# AtariST_microATX.net
KiCad netlist of a schematic drawn in EAGLE
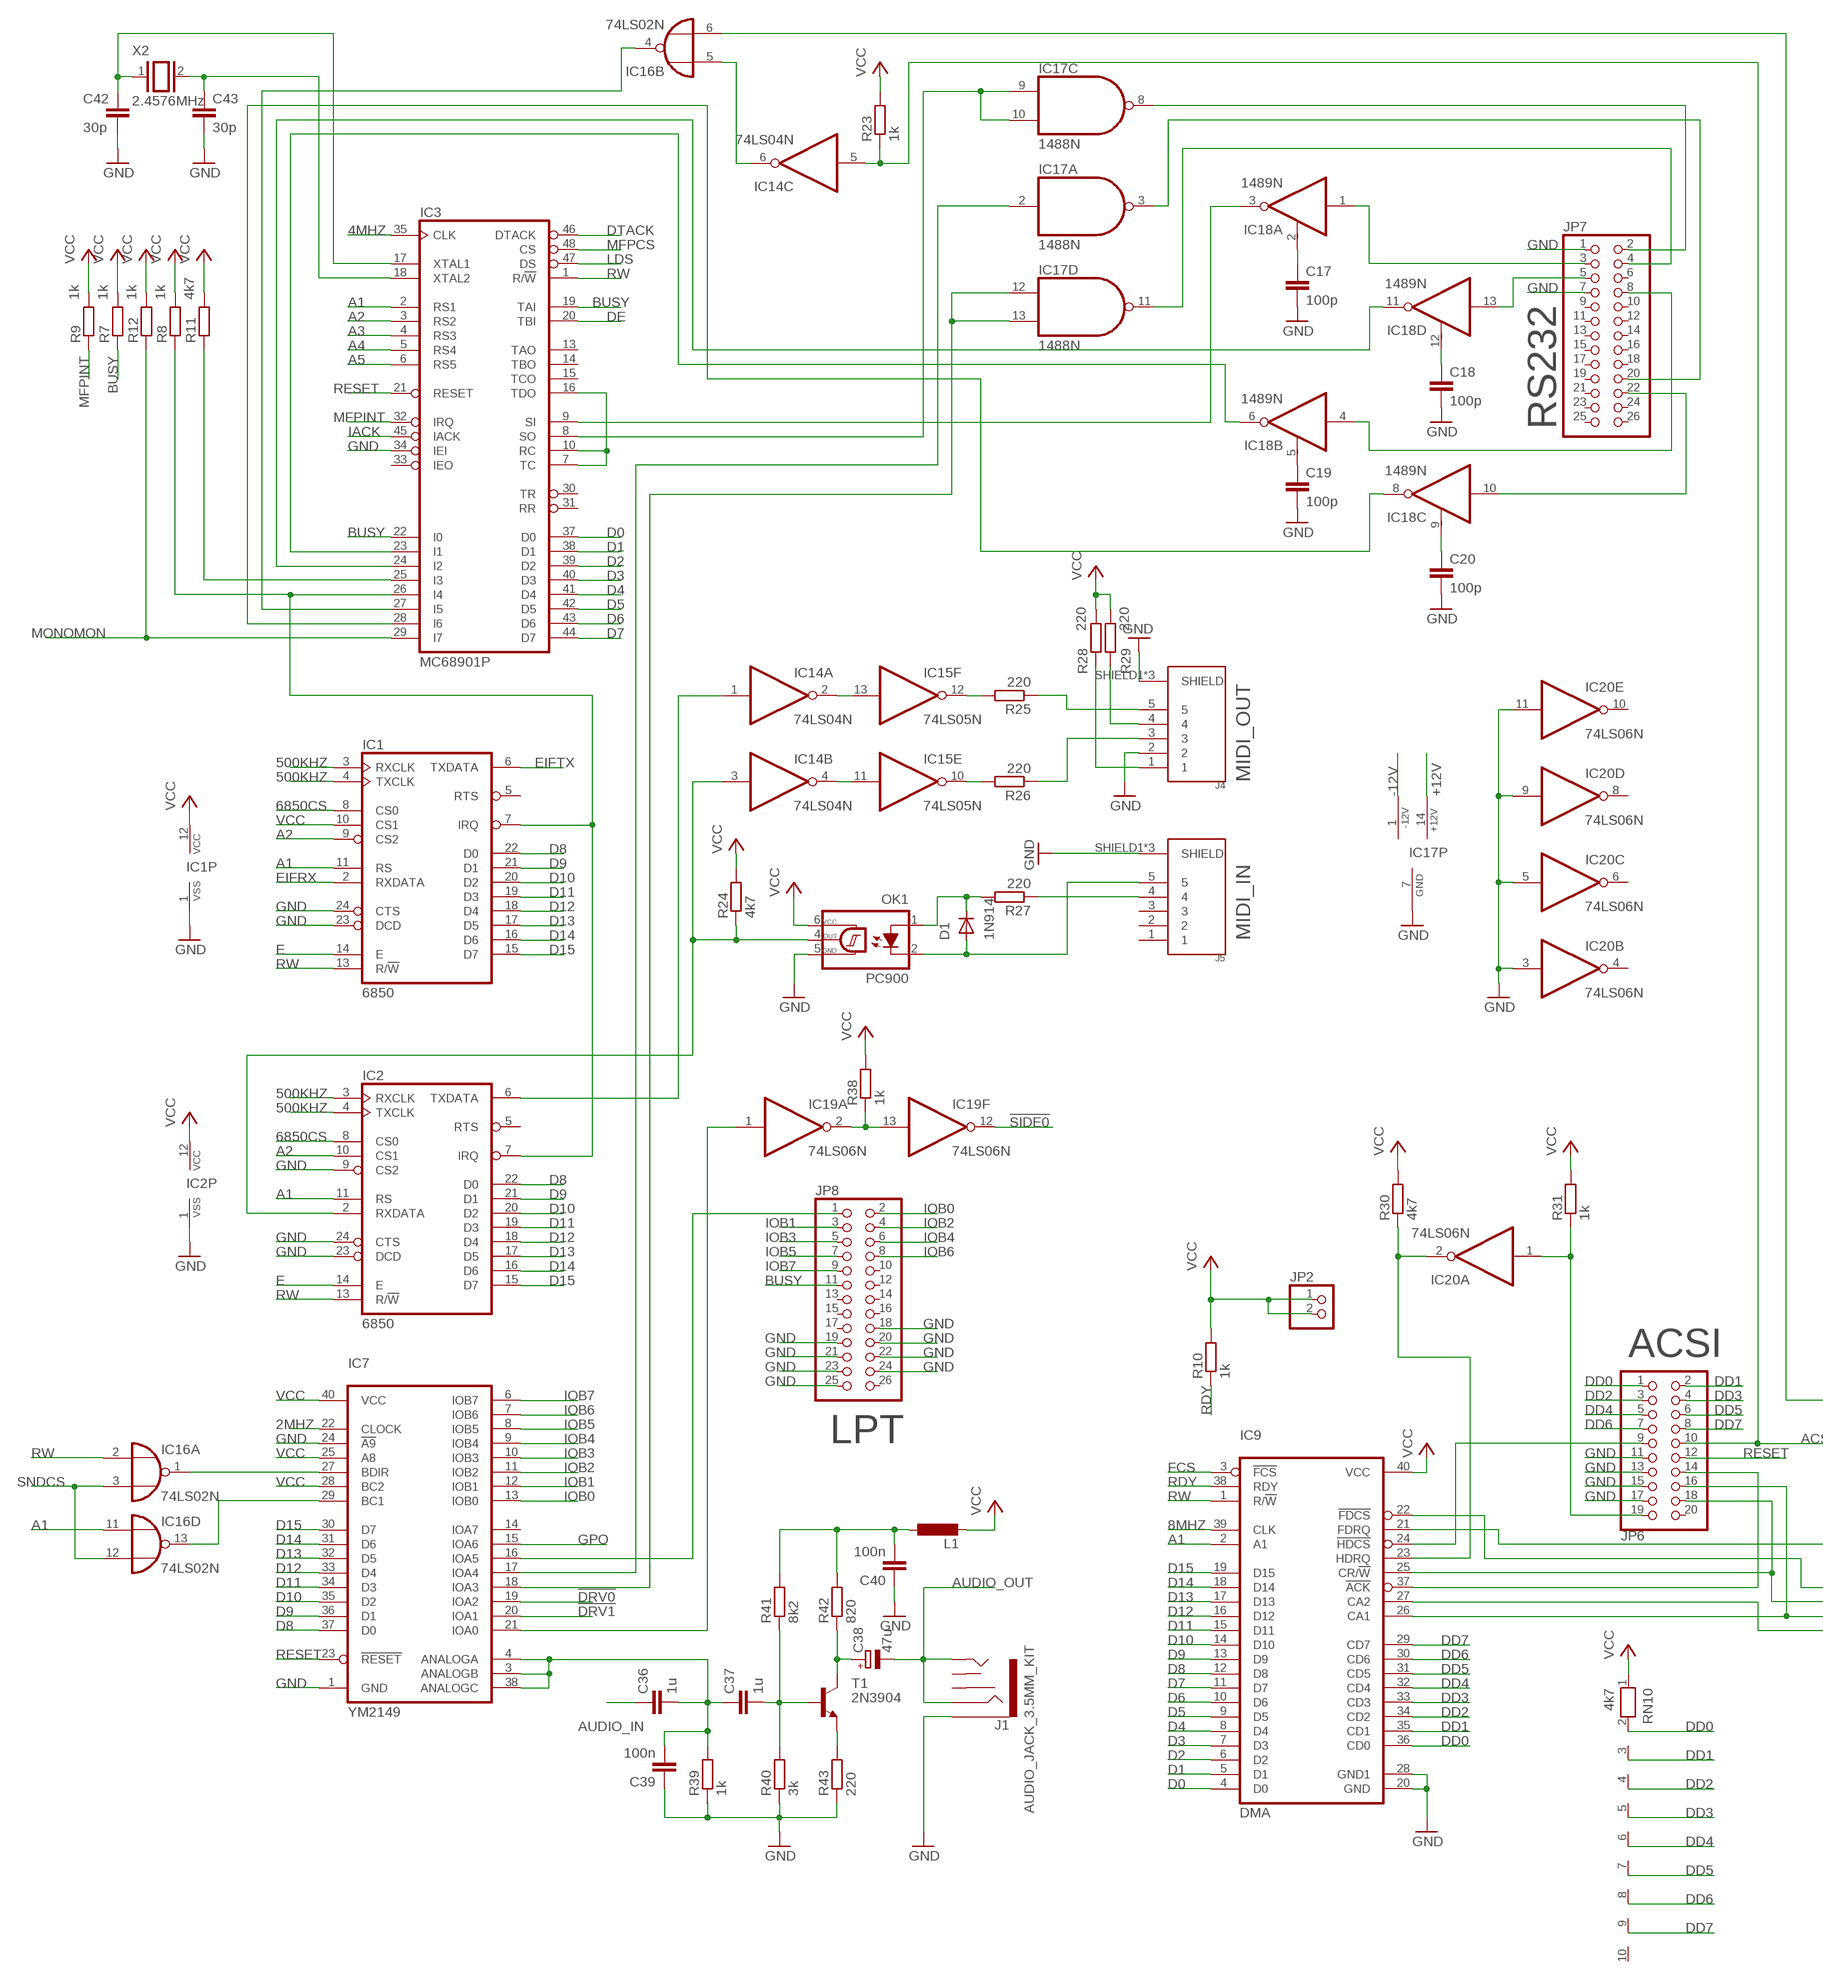
[diagram p0: schematic, sheet 1, part 1 of 2]
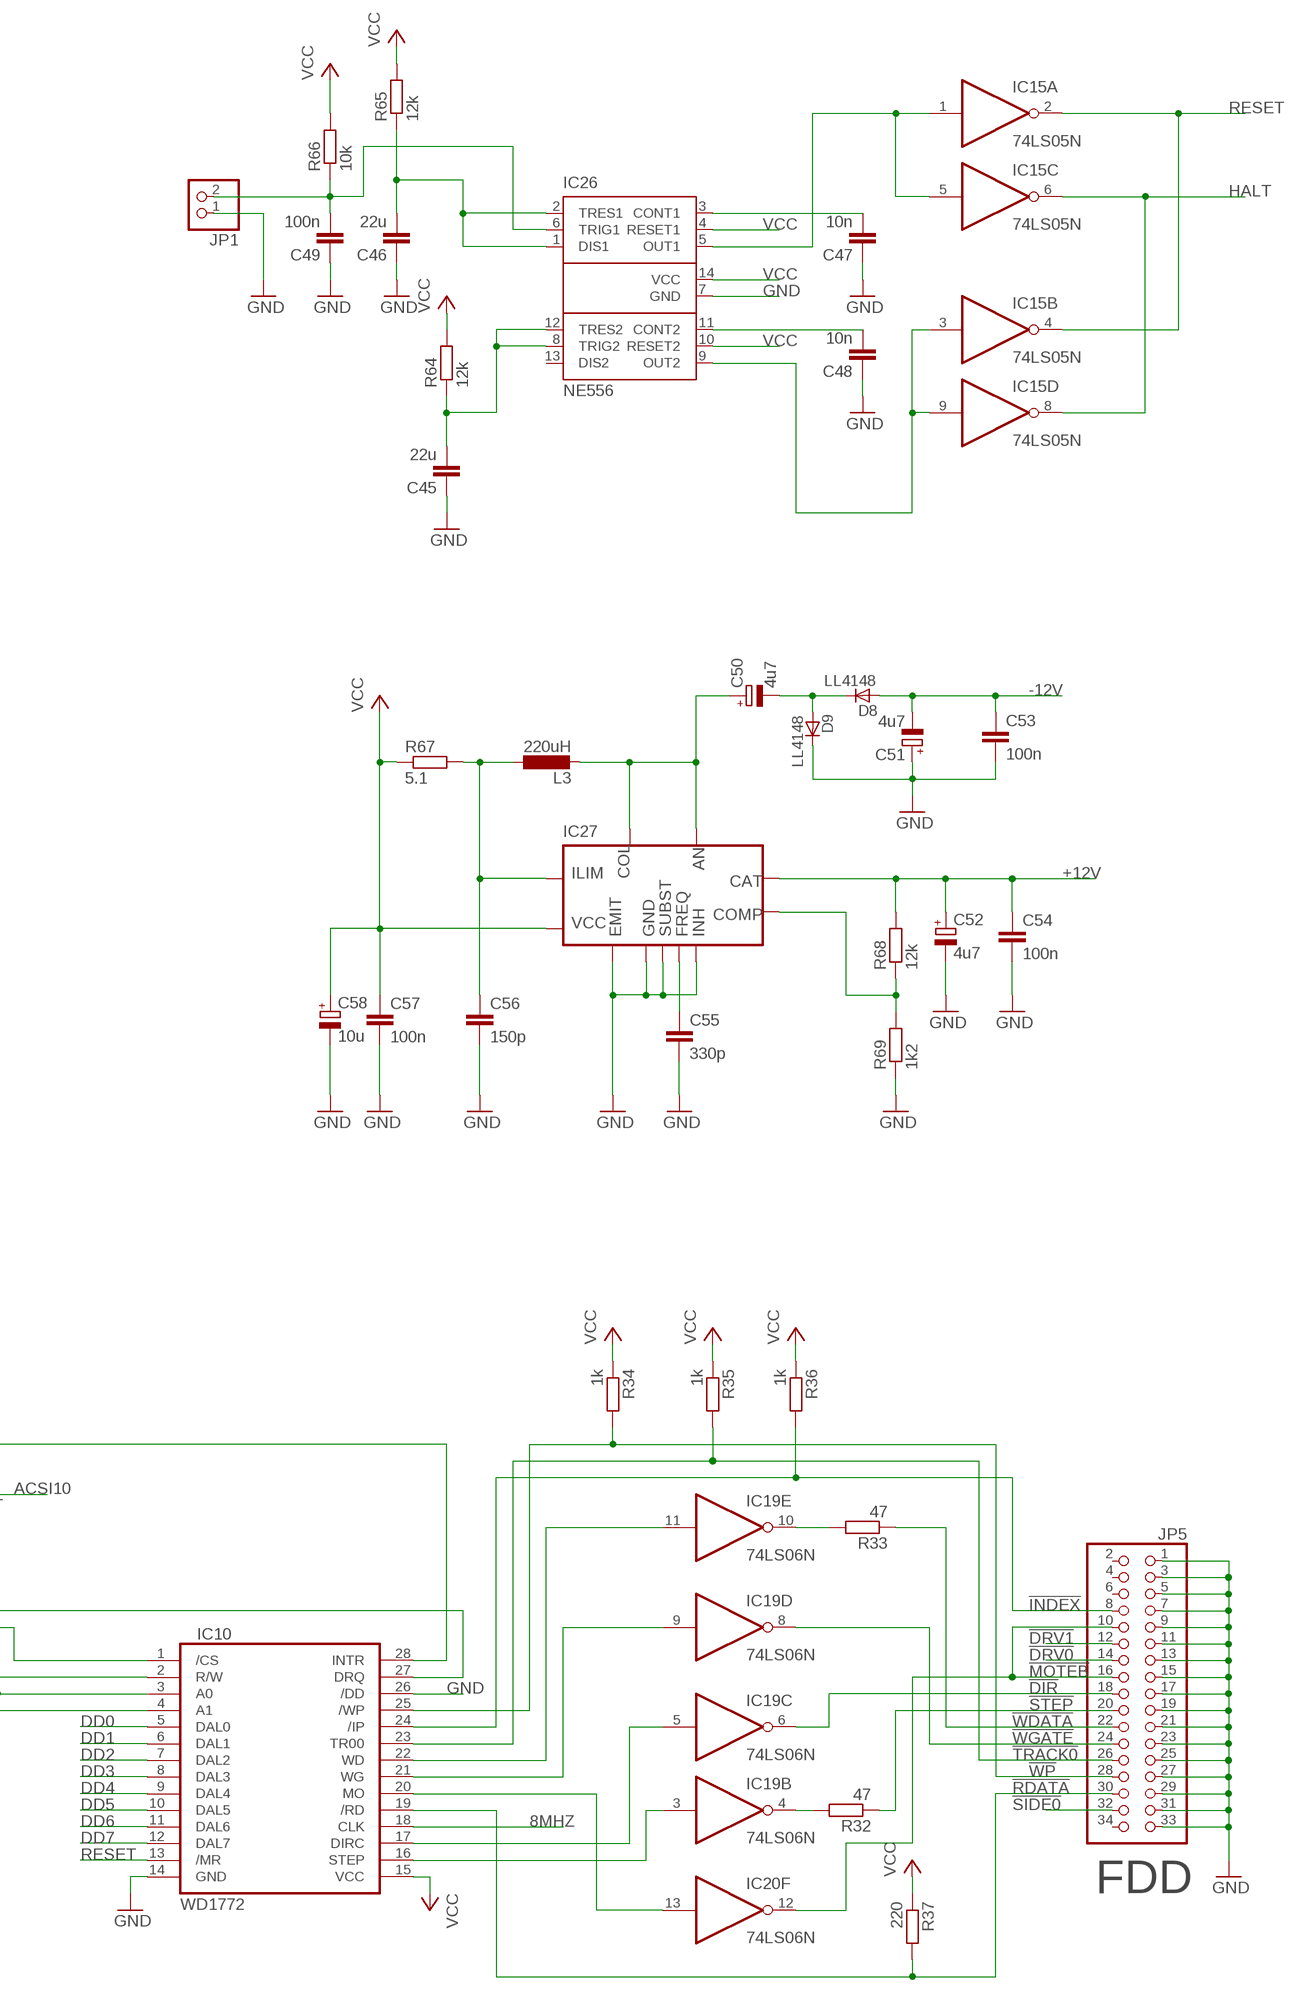
[diagram p1: schematic, sheet 1, part 2 of 2]
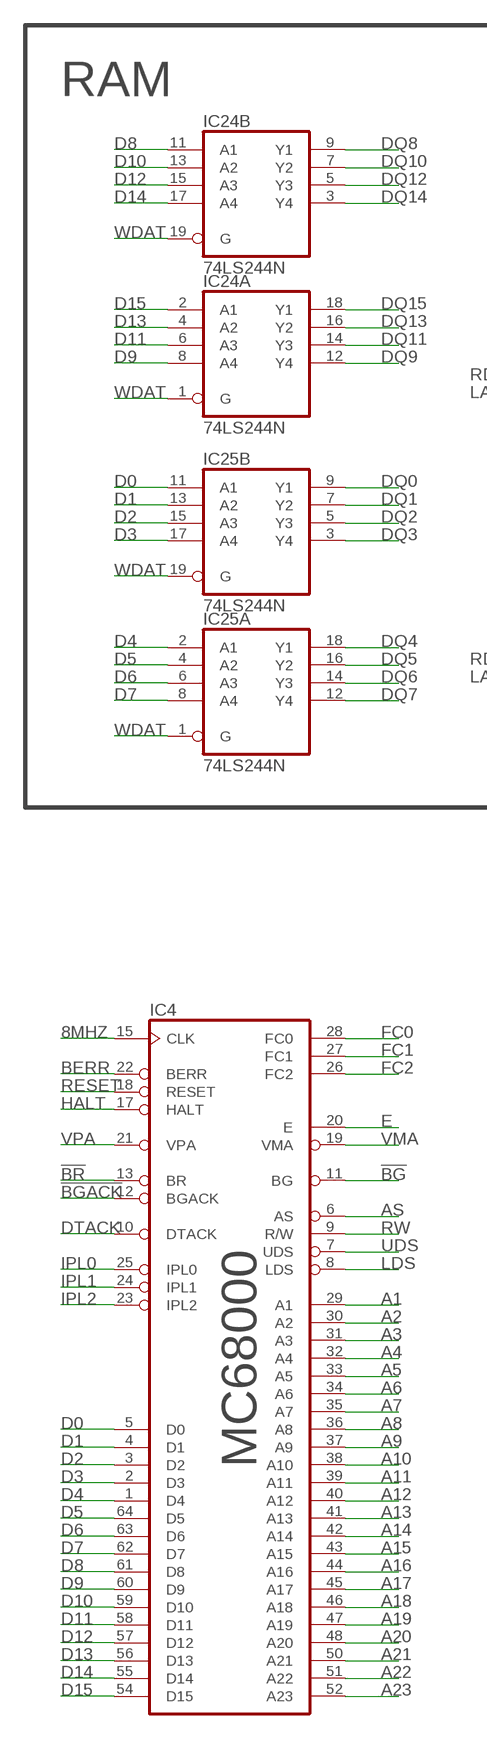
[diagram p2: schematic, sheet 2, part 1 of 2]
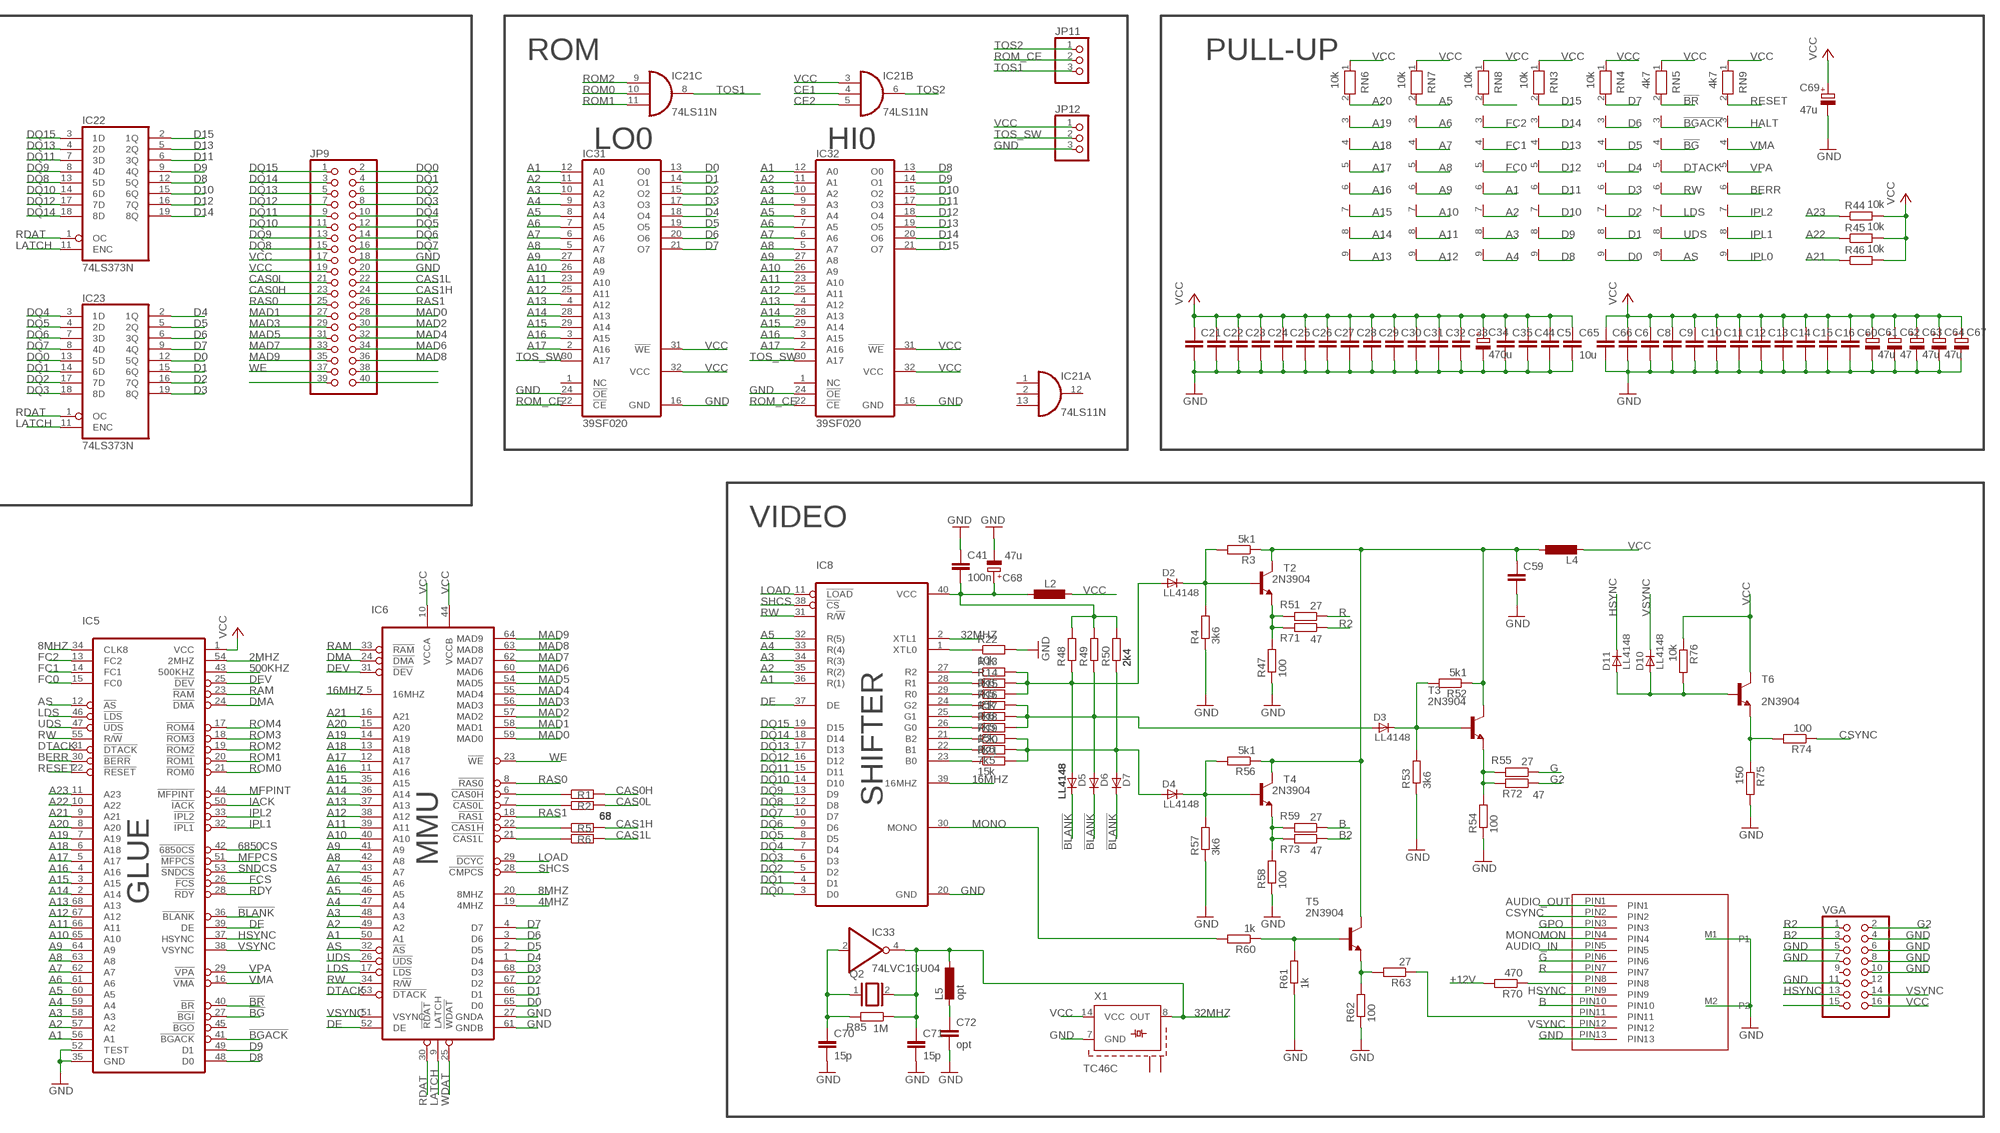
[diagram p3: schematic, sheet 2, part 2 of 2]
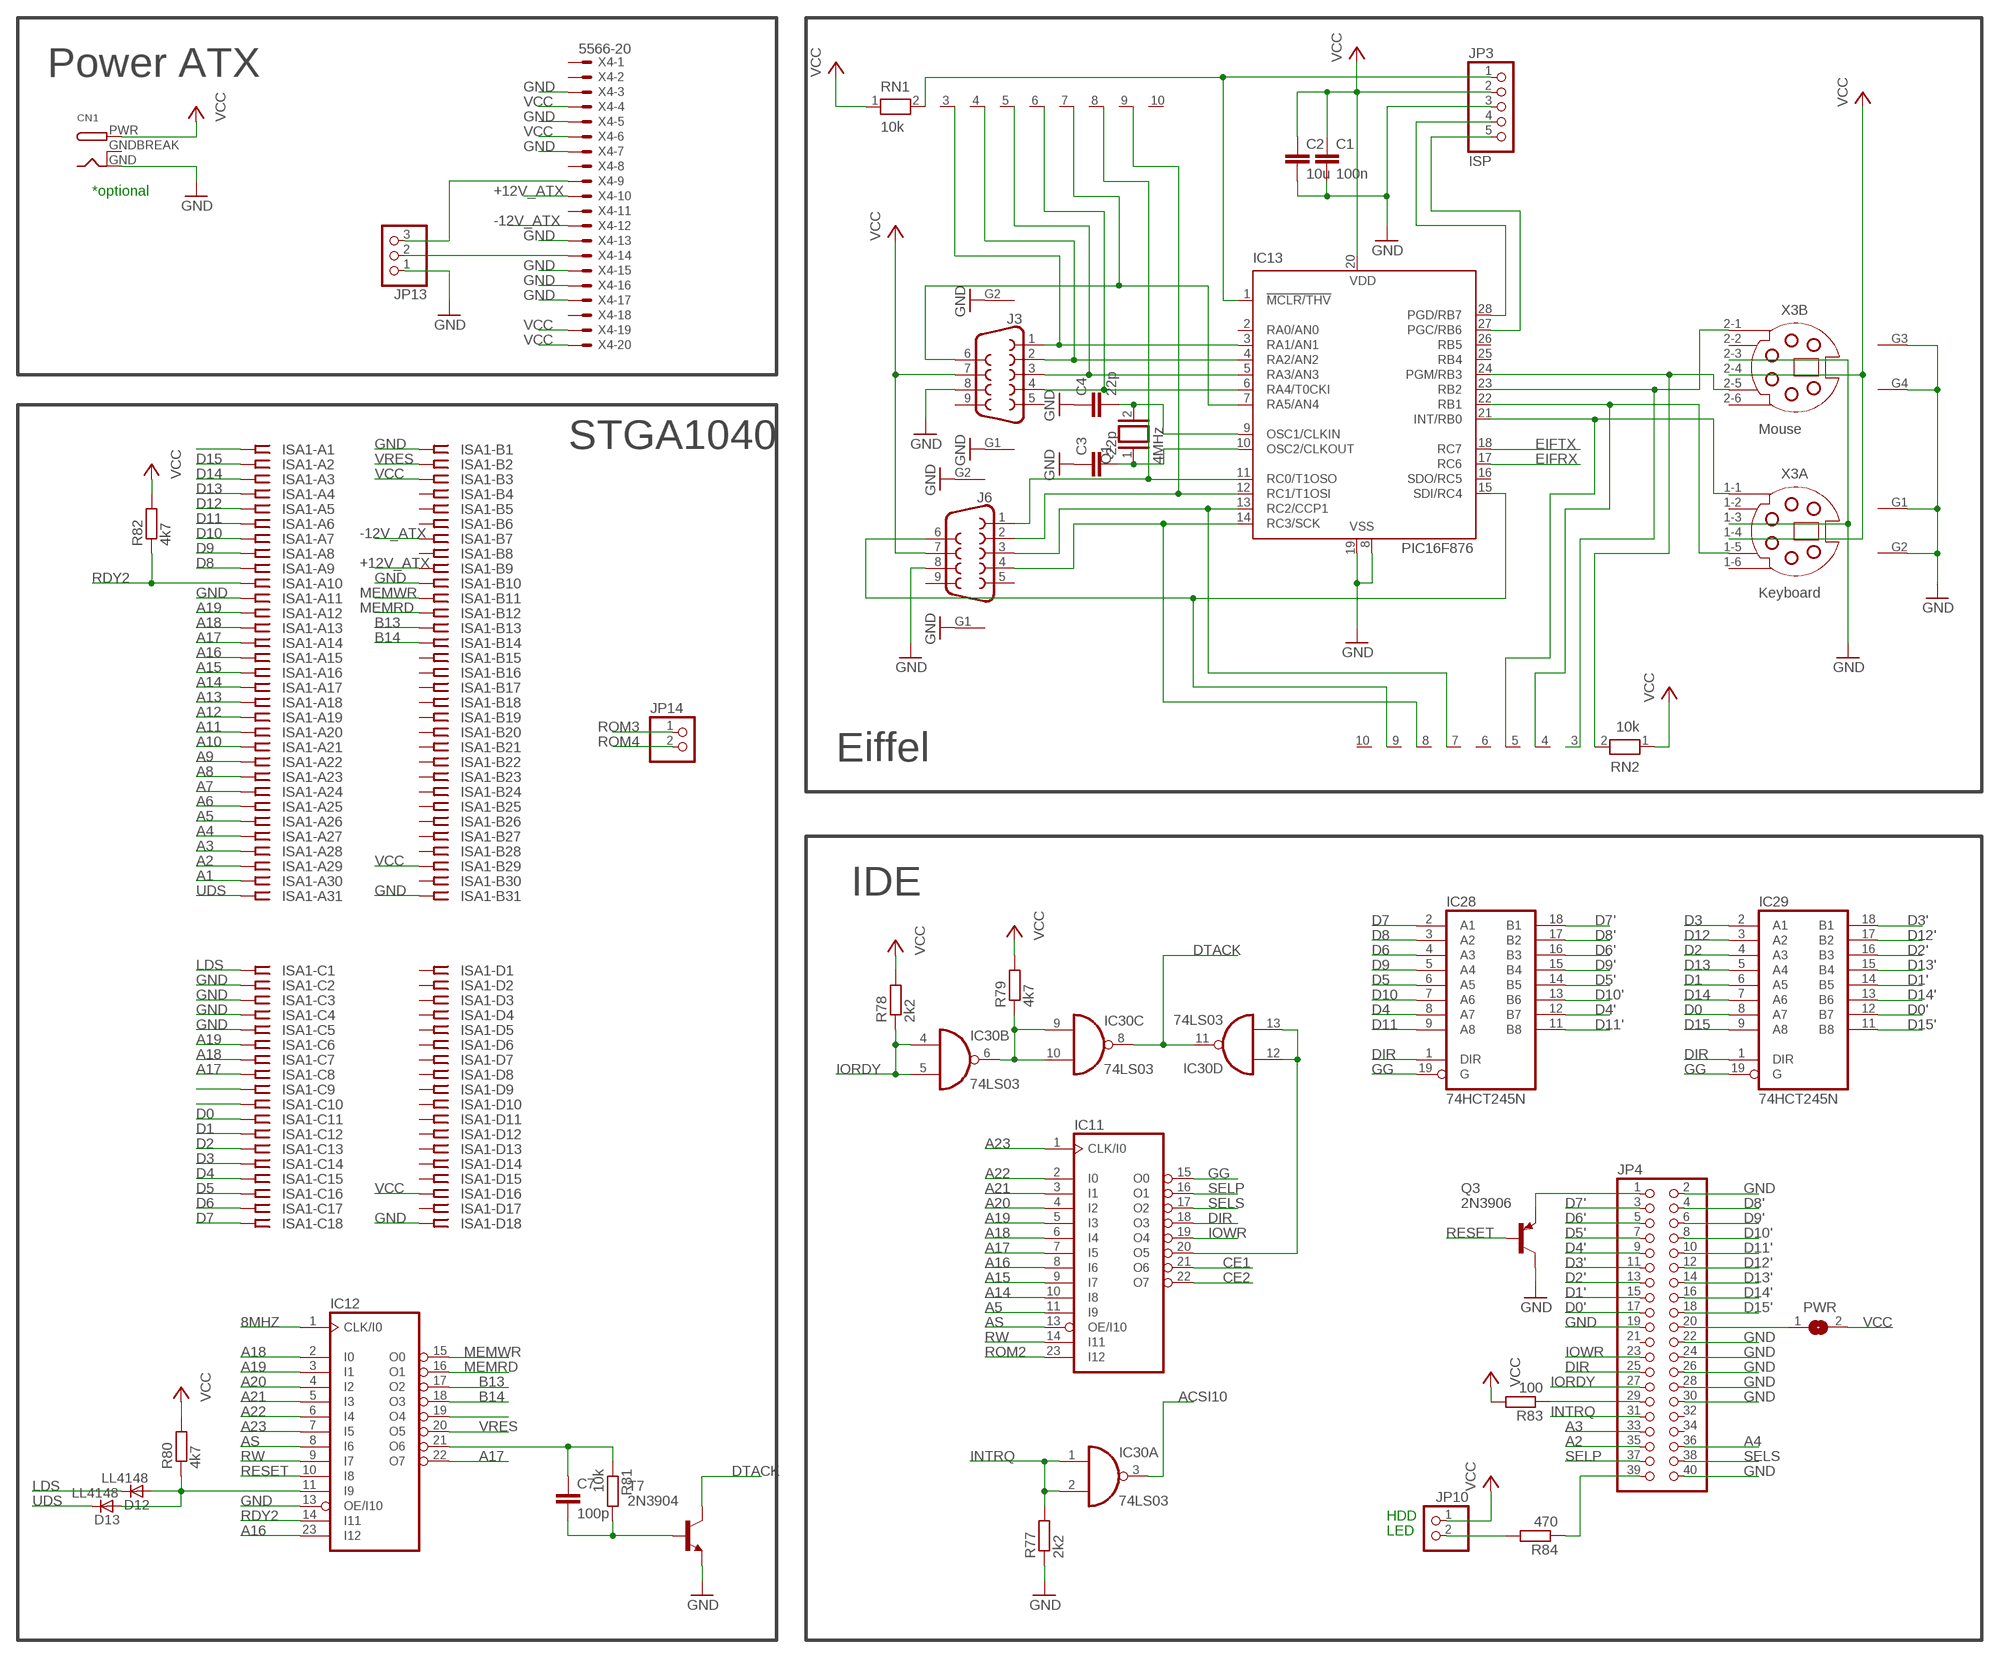
[diagram p4: schematic, sheet 3]

(export (version "E")
  (design (tool "Eeschema 10.0.6"))
  (components
    (comp (ref "C1")
      (value "100n")
      (footprint "eagle-import:C0805")
      (libsource (lib "eagle-import") (part "C-EUC0805"))
    )
    (comp (ref "C2")
      (value "10u")
      (footprint "eagle-import:C1206")
      (libsource (lib "eagle-import") (part "C-EUC1206"))
    )
    (comp (ref "C3")
      (value "22p")
      (footprint "eagle-import:C0805")
      (libsource (lib "eagle-import") (part "C-EUC0805"))
    )
    (comp (ref "C4")
      (value "22p")
      (footprint "eagle-import:C0805")
      (libsource (lib "eagle-import") (part "C-EUC0805"))
    )
    (comp (ref "C7")
      (value "100p")
      (footprint "eagle-import:C0805")
      (libsource (lib "eagle-import") (part "C-EUC0805"))
    )
    (comp (ref "CN1")
      (value "DCBARRELPTH")
      (footprint "eagle-import:DCJACK_2MM_PTH")
      (libsource (lib "eagle-import") (part "DCBARRELPTH"))
    )
    (comp (ref "D12")
      (value "LL4148")
      (footprint "eagle-import:SOD80_DO213AA_MINIMELF")
      (libsource (lib "eagle-import") (part "LL4148"))
    )
    (comp (ref "D13")
      (value "LL4148")
      (footprint "eagle-import:SOD80_DO213AA_MINIMELF")
      (libsource (lib "eagle-import") (part "LL4148"))
    )
    (comp (ref "IC11")
      (value "20V8")
      (footprint "eagle-import:DIL24-3")
      (fields (field (name "MF") "FARNELL") (field (name "MPN") "GAL20V8B-25QP"))
      (libsource (lib "eagle-import") (part "20V8"))
    )
    (comp (ref "IC12")
      (value "20V8")
      (footprint "eagle-import:DIL24-3")
      (fields (field (name "MF") "FARNELL") (field (name "MPN") "GAL20V8B-25QP"))
      (libsource (lib "eagle-import") (part "20V8"))
    )
    (comp (ref "IC13")
      (value "PIC16F876")
      (footprint "eagle-import:DIL28-3")
      (fields (field (name "MF") "MICROCHIP") (field (name "MPN") "PIC16F872-I/SP"))
      (libsource (lib "eagle-import") (part "PIC16872PF"))
    )
    (comp (ref "IC28")
      (value "74HCT245N")
      (footprint "eagle-import:DIL20")
      (libsource (lib "eagle-import") (part "74245NHCT"))
    )
    (comp (ref "IC29")
      (value "74HCT245N")
      (footprint "eagle-import:DIL20")
      (libsource (lib "eagle-import") (part "74245NHCT"))
    )
    (comp (ref "IC30")
      (value "74LS03")
      (footprint "eagle-import:SO14")
      (libsource (lib "eagle-import") (part "7403DALS"))
    )
    (comp (ref "ISA1")
      (value "ISA-SLOT")
      (footprint "eagle-import:ISA-16")
      (libsource (lib "eagle-import") (part "ISA-SLOT"))
    )
    (comp (ref "J3")
      (value "DB9MALE")
      (footprint "eagle-import:DB9_MALE")
      (libsource (lib "eagle-import") (part "DB9MALE"))
    )
    (comp (ref "J6")
      (value "DB9MALE")
      (footprint "eagle-import:DB9_MALE")
      (libsource (lib "eagle-import") (part "DB9MALE"))
    )
    (comp (ref "JP3")
      (value "ISP")
      (footprint "eagle-import:1X05")
      (libsource (lib "eagle-import") (part "PINHD-1X5"))
    )
    (comp (ref "JP4")
      (value "PINHD-2X20")
      (footprint "eagle-import:2X20")
      (libsource (lib "eagle-import") (part "PINHD-2X20"))
    )
    (comp (ref "JP10")
      (value "PINHD-1X2")
      (footprint "eagle-import:1X02")
      (libsource (lib "eagle-import") (part "PINHD-1X2"))
    )
    (comp (ref "JP13")
      (value "PINHD-1X3")
      (footprint "eagle-import:1X03")
      (libsource (lib "eagle-import") (part "PINHD-1X3"))
    )
    (comp (ref "JP14")
      (value "PINHD-1X2")
      (footprint "eagle-import:1X02")
      (libsource (lib "eagle-import") (part "PINHD-1X2"))
    )
    (comp (ref "PWR") (value "SJ") (footprint "eagle-import:SJ") (libsource (lib "eagle-import") (part "SJ")))
    (comp (ref "Q1")
      (value "4MHz")
      (footprint "eagle-import:QS")
      (libsource (lib "eagle-import") (part "XTAL/S"))
    )
    (comp (ref "Q3")
      (value "2N3906")
      (footprint "eagle-import:TO92")
      (libsource (lib "eagle-import") (part "2N3906"))
    )
    (comp (ref "R77")
      (value "2k2")
      (footprint "eagle-import:R0805")
      (libsource (lib "eagle-import") (part "R-EU_R0805"))
    )
    (comp (ref "R78")
      (value "2k2")
      (footprint "eagle-import:R0805")
      (libsource (lib "eagle-import") (part "R-EU_R0805"))
    )
    (comp (ref "R79")
      (value "4k7")
      (footprint "eagle-import:R0805")
      (libsource (lib "eagle-import") (part "R-EU_R0805"))
    )
    (comp (ref "R80")
      (value "4k7")
      (footprint "eagle-import:R0805")
      (libsource (lib "eagle-import") (part "R-EU_R0805"))
    )
    (comp (ref "R81")
      (value "10k")
      (footprint "eagle-import:R0805")
      (libsource (lib "eagle-import") (part "R-EU_R0805"))
    )
    (comp (ref "R82")
      (value "4k7")
      (footprint "eagle-import:R0805")
      (libsource (lib "eagle-import") (part "R-EU_R0805"))
    )
    (comp (ref "R83")
      (value "100")
      (footprint "eagle-import:R0805")
      (libsource (lib "eagle-import") (part "R-EU_R0805"))
    )
    (comp (ref "R84")
      (value "470")
      (footprint "eagle-import:R0805")
      (libsource (lib "eagle-import") (part "R-EU_R0805"))
    )
    (comp (ref "RN1")
      (value "10k")
      (footprint "eagle-import:RN-10")
      (libsource (lib "eagle-import") (part "RN09"))
    )
    (comp (ref "RN2")
      (value "10k")
      (footprint "eagle-import:RN-10")
      (libsource (lib "eagle-import") (part "RN09"))
    )
    (comp (ref "T7")
      (value "2N3904")
      (footprint "eagle-import:TO92")
      (libsource (lib "eagle-import") (part "2N3904"))
    )
    (comp (ref "X3")
      (value "MDSSV-BD06")
      (footprint "eagle-import:SSV-BD06")
      (libsource (lib "eagle-import") (part "MDSSV-BD06"))
    )
    (comp (ref "X4")
      (value "5566-20")
      (footprint "eagle-import:5566-20")
      (libsource (lib "eagle-import") (part "5566-20"))
    )
    (comp (ref "C5")
      (value "C-EU050-025X075")
      (footprint "eagle-import:C050-025X075")
      (libsource (lib "eagle-import") (part "C-EU050-025X075"))
    )
    (comp (ref "C6")
      (value "C-EUC0805")
      (footprint "eagle-import:C0805")
      (libsource (lib "eagle-import") (part "C-EUC0805"))
    )
    (comp (ref "C8")
      (value "C-EUC0805")
      (footprint "eagle-import:C0805")
      (libsource (lib "eagle-import") (part "C-EUC0805"))
    )
    (comp (ref "C9")
      (value "C-EUC0805")
      (footprint "eagle-import:C0805")
      (libsource (lib "eagle-import") (part "C-EUC0805"))
    )
    (comp (ref "C10")
      (value "C-EUC0805")
      (footprint "eagle-import:C0805")
      (libsource (lib "eagle-import") (part "C-EUC0805"))
    )
    (comp (ref "C11")
      (value "C-EUC0805")
      (footprint "eagle-import:C0805")
      (libsource (lib "eagle-import") (part "C-EUC0805"))
    )
    (comp (ref "C12")
      (value "C-EUC0805")
      (footprint "eagle-import:C0805")
      (libsource (lib "eagle-import") (part "C-EUC0805"))
    )
    (comp (ref "C13")
      (value "C-EUC0805")
      (footprint "eagle-import:C0805")
      (libsource (lib "eagle-import") (part "C-EUC0805"))
    )
    (comp (ref "C14")
      (value "C-EUC0805")
      (footprint "eagle-import:C0805")
      (libsource (lib "eagle-import") (part "C-EUC0805"))
    )
    (comp (ref "C15")
      (value "C-EUC0805")
      (footprint "eagle-import:C0805")
      (libsource (lib "eagle-import") (part "C-EUC0805"))
    )
    (comp (ref "C16")
      (value "C-EU050-025X075")
      (footprint "eagle-import:C050-025X075")
      (libsource (lib "eagle-import") (part "C-EU050-025X075"))
    )
    (comp (ref "C21")
      (value "C-EUC0805")
      (footprint "eagle-import:C0805")
      (libsource (lib "eagle-import") (part "C-EUC0805"))
    )
    (comp (ref "C22")
      (value "C-EUC0805")
      (footprint "eagle-import:C0805")
      (libsource (lib "eagle-import") (part "C-EUC0805"))
    )
    (comp (ref "C23")
      (value "C-EUC0805")
      (footprint "eagle-import:C0805")
      (libsource (lib "eagle-import") (part "C-EUC0805"))
    )
    (comp (ref "C24")
      (value "C-EUC0805")
      (footprint "eagle-import:C0805")
      (libsource (lib "eagle-import") (part "C-EUC0805"))
    )
    (comp (ref "C25")
      (value "C-EU050-025X075")
      (footprint "eagle-import:C050-025X075")
      (libsource (lib "eagle-import") (part "C-EU050-025X075"))
    )
    (comp (ref "C26")
      (value "C-EU075-032X103")
      (footprint "eagle-import:C075-032X103")
      (libsource (lib "eagle-import") (part "C-EU075-032X103"))
    )
    (comp (ref "C27")
      (value "C-EUC0805")
      (footprint "eagle-import:C0805")
      (libsource (lib "eagle-import") (part "C-EUC0805"))
    )
    (comp (ref "C28")
      (value "C-EU050-025X075")
      (footprint "eagle-import:C050-025X075")
      (libsource (lib "eagle-import") (part "C-EU050-025X075"))
    )
    (comp (ref "C29")
      (value "C-EU050-025X075")
      (footprint "eagle-import:C050-025X075")
      (libsource (lib "eagle-import") (part "C-EU050-025X075"))
    )
    (comp (ref "C30")
      (value "C-EU050-025X075")
      (footprint "eagle-import:C050-025X075")
      (libsource (lib "eagle-import") (part "C-EU050-025X075"))
    )
    (comp (ref "C31")
      (value "C-EUC0805")
      (footprint "eagle-import:C0805")
      (libsource (lib "eagle-import") (part "C-EUC0805"))
    )
    (comp (ref "C32")
      (value "C-EU050-025X075")
      (footprint "eagle-import:C050-025X075")
      (libsource (lib "eagle-import") (part "C-EU050-025X075"))
    )
    (comp (ref "C33")
      (value "C-EU050-025X075")
      (footprint "eagle-import:C050-025X075")
      (libsource (lib "eagle-import") (part "C-EU050-025X075"))
    )
    (comp (ref "C34")
      (value "470u")
      (footprint "eagle-import:E3,5-8")
      (libsource (lib "eagle-import") (part "CPOL-EUE3.5-8"))
    )
    (comp (ref "C35")
      (value "C-EUC0805")
      (footprint "eagle-import:C0805")
      (libsource (lib "eagle-import") (part "C-EUC0805"))
    )
    (comp (ref "C41")
      (value "100n")
      (footprint "eagle-import:C050-025X075")
      (libsource (lib "eagle-import") (part "C-EU050-025X075"))
    )
    (comp (ref "C44")
      (value "C-EUC0805")
      (footprint "eagle-import:C0805")
      (libsource (lib "eagle-import") (part "C-EUC0805"))
    )
    (comp (ref "C59")
      (value "C-EU050-025X075")
      (footprint "eagle-import:C050-025X075")
      (libsource (lib "eagle-import") (part "C-EU050-025X075"))
    )
    (comp (ref "C60")
      (value "C-EUC0805")
      (footprint "eagle-import:C0805")
      (libsource (lib "eagle-import") (part "C-EUC0805"))
    )
    (comp (ref "C61")
      (value "47u")
      (footprint "eagle-import:E2-5")
      (libsource (lib "eagle-import") (part "CPOL-EUE2-5"))
    )
    (comp (ref "C62")
      (value "47")
      (footprint "eagle-import:E2-5")
      (libsource (lib "eagle-import") (part "CPOL-EUE2-5"))
    )
    (comp (ref "C63")
      (value "47u")
      (footprint "eagle-import:E2-5")
      (libsource (lib "eagle-import") (part "CPOL-EUE2-5"))
    )
    (comp (ref "C64")
      (value "47u")
      (footprint "eagle-import:E2-5")
      (libsource (lib "eagle-import") (part "CPOL-EUE2-5"))
    )
    (comp (ref "C65")
      (value "10u")
      (footprint "eagle-import:C0805")
      (libsource (lib "eagle-import") (part "C-EUC0805"))
    )
    (comp (ref "C66")
      (value "C-EUC0805")
      (footprint "eagle-import:C0805")
      (libsource (lib "eagle-import") (part "C-EUC0805"))
    )
    (comp (ref "C67")
      (value "CPOL-EUC/6032-28R")
      (footprint "eagle-import:C_6032-28R")
      (libsource (lib "eagle-import") (part "CPOL-EUC/6032-28R"))
    )
    (comp (ref "C68")
      (value "47u")
      (footprint "eagle-import:E2,5-5")
      (libsource (lib "eagle-import") (part "CPOL-EUE2.5-5"))
    )
    (comp (ref "C69")
      (value "47u")
      (footprint "eagle-import:E2,5-5")
      (libsource (lib "eagle-import") (part "CPOL-EUE2.5-5"))
    )
    (comp (ref "C70")
      (value "15p")
      (footprint "eagle-import:C0805")
      (libsource (lib "eagle-import") (part "C-EUC0805"))
    )
    (comp (ref "C71")
      (value "15p")
      (footprint "eagle-import:C0805")
      (libsource (lib "eagle-import") (part "C-EUC0805"))
    )
    (comp (ref "C72")
      (value "opt")
      (footprint "eagle-import:C0805")
      (libsource (lib "eagle-import") (part "C-EUC0805"))
    )
    (comp (ref "D2")
      (value "LL4148")
      (footprint "eagle-import:SOD80_DO213AA_MINIMELF")
      (libsource (lib "eagle-import") (part "LL4148"))
    )
    (comp (ref "D3")
      (value "LL4148")
      (footprint "eagle-import:SOD80_DO213AA_MINIMELF")
      (libsource (lib "eagle-import") (part "LL4148"))
    )
    (comp (ref "D4")
      (value "LL4148")
      (footprint "eagle-import:SOD80_DO213AA_MINIMELF")
      (libsource (lib "eagle-import") (part "LL4148"))
    )
    (comp (ref "D5")
      (value "LL4148")
      (footprint "eagle-import:SOD80_DO213AA_MINIMELF")
      (libsource (lib "eagle-import") (part "LL4148"))
    )
    (comp (ref "D6")
      (value "LL4148")
      (footprint "eagle-import:SOD80_DO213AA_MINIMELF")
      (libsource (lib "eagle-import") (part "LL4148"))
    )
    (comp (ref "D7")
      (value "LL4148")
      (footprint "eagle-import:SOD80_DO213AA_MINIMELF")
      (libsource (lib "eagle-import") (part "LL4148"))
    )
    (comp (ref "D10")
      (value "LL4148")
      (footprint "eagle-import:SOD80_DO213AA_MINIMELF")
      (libsource (lib "eagle-import") (part "LL4148"))
    )
    (comp (ref "D11")
      (value "LL4148")
      (footprint "eagle-import:SOD80_DO213AA_MINIMELF")
      (libsource (lib "eagle-import") (part "LL4148"))
    )
    (comp (ref "IC4")
      (value "MC68000")
      (footprint "eagle-import:DIL64")
      (libsource (lib "eagle-import") (part "MC68000P"))
    )
    (comp (ref "IC5")
      (value "GLUE")
      (footprint "eagle-import:PLCC68")
      (libsource (lib "eagle-import") (part "GLUE"))
    )
    (comp (ref "IC6")
      (value "MMU")
      (footprint "eagle-import:PLCC68")
      (libsource (lib "eagle-import") (part "MMU"))
    )
    (comp (ref "IC8")
      (value "SHIFTER")
      (footprint "eagle-import:DIL40")
      (libsource (lib "eagle-import") (part "SHIFTER"))
    )
    (comp (ref "IC21")
      (value "74LS11N")
      (footprint "eagle-import:DIL14")
      (libsource (lib "eagle-import") (part "7411NLS"))
    )
    (comp (ref "IC22")
      (value "74LS373N")
      (footprint "eagle-import:DIL20")
      (libsource (lib "eagle-import") (part "74373NLS"))
    )
    (comp (ref "IC23")
      (value "74LS373N")
      (footprint "eagle-import:DIL20")
      (libsource (lib "eagle-import") (part "74373NLS"))
    )
    (comp (ref "IC24")
      (value "74LS244N")
      (footprint "eagle-import:DIL20")
      (libsource (lib "eagle-import") (part "74244NLS"))
    )
    (comp (ref "IC25")
      (value "74LS244N")
      (footprint "eagle-import:DIL20")
      (libsource (lib "eagle-import") (part "74244NLS"))
    )
    (comp (ref "IC31")
      (value "39SF020")
      (footprint "eagle-import:DIL32")
      (libsource (lib "eagle-import") (part "39SF020"))
    )
    (comp (ref "IC32")
      (value "39SF020")
      (footprint "eagle-import:DIL32")
      (libsource (lib "eagle-import") (part "39SF020"))
    )
    (comp (ref "IC33")
      (value "74LVC1GU04")
      (footprint "eagle-import:SOT23-5")
      (libsource (lib "eagle-import") (part "741G04DBVAHCT"))
    )
    (comp (ref "JP9")
      (value "PINHD-2X20")
      (footprint "eagle-import:2X20")
      (libsource (lib "eagle-import") (part "PINHD-2X20"))
    )
    (comp (ref "JP11")
      (value "PINHD-1X3")
      (footprint "eagle-import:1X03")
      (libsource (lib "eagle-import") (part "PINHD-1X3"))
    )
    (comp (ref "JP12")
      (value "PINHD-1X3")
      (footprint "eagle-import:1X03")
      (libsource (lib "eagle-import") (part "PINHD-1X3"))
    )
    (comp (ref "L2")
      (value "L-EU0204/7")
      (footprint "eagle-import:0204_7")
      (libsource (lib "eagle-import") (part "L-EU0204/7"))
    )
    (comp (ref "L4")
      (value "L-EU0204/7")
      (footprint "eagle-import:0204_7")
      (libsource (lib "eagle-import") (part "L-EU0204/7"))
    )
    (comp (ref "L5")
      (value "opt")
      (footprint "eagle-import:0204_7")
      (libsource (lib "eagle-import") (part "L-EU0204/7"))
    )
    (comp (ref "Q2")
      (value "XTAL/S")
      (footprint "eagle-import:QS")
      (libsource (lib "eagle-import") (part "XTAL/S"))
    )
    (comp (ref "R1")
      (value "68")
      (footprint "eagle-import:R0805")
      (libsource (lib "eagle-import") (part "R-EU_R0805"))
    )
    (comp (ref "R2")
      (value "68")
      (footprint "eagle-import:R0805")
      (libsource (lib "eagle-import") (part "R-EU_R0805"))
    )
    (comp (ref "R3")
      (value "5k1")
      (footprint "eagle-import:R0805")
      (libsource (lib "eagle-import") (part "R-EU_R0805"))
    )
    (comp (ref "R4")
      (value "3k6")
      (footprint "eagle-import:R0805")
      (libsource (lib "eagle-import") (part "R-EU_R0805"))
    )
    (comp (ref "R5")
      (value "68")
      (footprint "eagle-import:R0805")
      (libsource (lib "eagle-import") (part "R-EU_R0805"))
    )
    (comp (ref "R6")
      (value "68")
      (footprint "eagle-import:R0805")
      (libsource (lib "eagle-import") (part "R-EU_R0805"))
    )
    (comp (ref "R13")
      (value "3k6")
      (footprint "eagle-import:0204_5")
      (libsource (lib "eagle-import") (part "R-EU_0204/5"))
    )
    (comp (ref "R14")
      (value "7k5")
      (footprint "eagle-import:0204_5")
      (libsource (lib "eagle-import") (part "R-EU_0204/5"))
    )
    (comp (ref "R15")
      (value "15k")
      (footprint "eagle-import:0204_5")
      (libsource (lib "eagle-import") (part "R-EU_0204/5"))
    )
    (comp (ref "R16")
      (value "3k6")
      (footprint "eagle-import:0204_5")
      (libsource (lib "eagle-import") (part "R-EU_0204/5"))
    )
    (comp (ref "R17")
      (value "7k5")
      (footprint "eagle-import:0204_5")
      (libsource (lib "eagle-import") (part "R-EU_0204/5"))
    )
    (comp (ref "R18")
      (value "15k")
      (footprint "eagle-import:0204_5")
      (libsource (lib "eagle-import") (part "R-EU_0204/5"))
    )
    (comp (ref "R19")
      (value "3k6")
      (footprint "eagle-import:0204_5")
      (libsource (lib "eagle-import") (part "R-EU_0204/5"))
    )
    (comp (ref "R20")
      (value "7k5")
      (footprint "eagle-import:0204_5")
      (libsource (lib "eagle-import") (part "R-EU_0204/5"))
    )
    (comp (ref "R21")
      (value "15k")
      (footprint "eagle-import:0204_5")
      (libsource (lib "eagle-import") (part "R-EU_0204/5"))
    )
    (comp (ref "R22")
      (value "10k")
      (footprint "eagle-import:R0805")
      (libsource (lib "eagle-import") (part "R-EU_R0805"))
    )
    (comp (ref "R44")
      (value "10k")
      (footprint "eagle-import:R0805")
      (libsource (lib "eagle-import") (part "R-EU_R0805"))
    )
    (comp (ref "R45")
      (value "10k")
      (footprint "eagle-import:R0805")
      (libsource (lib "eagle-import") (part "R-EU_R0805"))
    )
    (comp (ref "R46")
      (value "10k")
      (footprint "eagle-import:R0805")
      (libsource (lib "eagle-import") (part "R-EU_R0805"))
    )
    (comp (ref "R47")
      (value "100")
      (footprint "eagle-import:R0805")
      (libsource (lib "eagle-import") (part "R-EU_R0805"))
    )
    (comp (ref "R48")
      (value "2k4")
      (footprint "eagle-import:R0805")
      (libsource (lib "eagle-import") (part "R-EU_R0805"))
    )
    (comp (ref "R49")
      (value "2k4")
      (footprint "eagle-import:R0805")
      (libsource (lib "eagle-import") (part "R-EU_R0805"))
    )
    (comp (ref "R50")
      (value "2k4")
      (footprint "eagle-import:R0805")
      (libsource (lib "eagle-import") (part "R-EU_R0805"))
    )
    (comp (ref "R51")
      (value "27")
      (footprint "eagle-import:R0805")
      (libsource (lib "eagle-import") (part "R-EU_R0805"))
    )
    (comp (ref "R52")
      (value "5k1")
      (footprint "eagle-import:R0805")
      (libsource (lib "eagle-import") (part "R-EU_R0805"))
    )
    (comp (ref "R53")
      (value "3k6")
      (footprint "eagle-import:R0805")
      (libsource (lib "eagle-import") (part "R-EU_R0805"))
    )
    (comp (ref "R54")
      (value "100")
      (footprint "eagle-import:R0805")
      (libsource (lib "eagle-import") (part "R-EU_R0805"))
    )
    (comp (ref "R55")
      (value "27")
      (footprint "eagle-import:R0805")
      (libsource (lib "eagle-import") (part "R-EU_R0805"))
    )
    (comp (ref "R56")
      (value "5k1")
      (footprint "eagle-import:R0805")
      (libsource (lib "eagle-import") (part "R-EU_R0805"))
    )
    (comp (ref "R57")
      (value "3k6")
      (footprint "eagle-import:R0805")
      (libsource (lib "eagle-import") (part "R-EU_R0805"))
    )
    (comp (ref "R58")
      (value "100")
      (footprint "eagle-import:R0805")
      (libsource (lib "eagle-import") (part "R-EU_R0805"))
    )
    (comp (ref "R59")
      (value "27")
      (footprint "eagle-import:R0805")
      (libsource (lib "eagle-import") (part "R-EU_R0805"))
    )
    (comp (ref "R60")
      (value "1k")
      (footprint "eagle-import:R0805")
      (libsource (lib "eagle-import") (part "R-EU_R0805"))
    )
    (comp (ref "R61")
      (value "1k")
      (footprint "eagle-import:R0805")
      (libsource (lib "eagle-import") (part "R-EU_R0805"))
    )
    (comp (ref "R62")
      (value "100")
      (footprint "eagle-import:R0805")
      (libsource (lib "eagle-import") (part "R-EU_R0805"))
    )
    (comp (ref "R63")
      (value "27")
      (footprint "eagle-import:R0805")
      (libsource (lib "eagle-import") (part "R-EU_R0805"))
    )
    (comp (ref "R70")
      (value "470")
      (footprint "eagle-import:R0805")
      (libsource (lib "eagle-import") (part "R-EU_R0805"))
    )
    (comp (ref "R71")
      (value "47")
      (footprint "eagle-import:R0805")
      (libsource (lib "eagle-import") (part "R-EU_R0805"))
    )
    (comp (ref "R72")
      (value "47")
      (footprint "eagle-import:R0805")
      (libsource (lib "eagle-import") (part "R-EU_R0805"))
    )
    (comp (ref "R73")
      (value "47")
      (footprint "eagle-import:R0805")
      (libsource (lib "eagle-import") (part "R-EU_R0805"))
    )
    (comp (ref "R74")
      (value "100")
      (footprint "eagle-import:R0805")
      (libsource (lib "eagle-import") (part "R-EU_R0805"))
    )
    (comp (ref "R75")
      (value "150")
      (footprint "eagle-import:R0805")
      (libsource (lib "eagle-import") (part "R-EU_R0805"))
    )
    (comp (ref "R76")
      (value "10k")
      (footprint "eagle-import:R0805")
      (libsource (lib "eagle-import") (part "R-EU_R0805"))
    )
    (comp (ref "R85")
      (value "1M")
      (footprint "eagle-import:R0805")
      (libsource (lib "eagle-import") (part "R-EU_R0805"))
    )
    (comp (ref "RN3")
      (value "10k")
      (footprint "eagle-import:RN-9")
      (libsource (lib "eagle-import") (part "RN08"))
    )
    (comp (ref "RN4")
      (value "10k")
      (footprint "eagle-import:RN-9")
      (libsource (lib "eagle-import") (part "RN08"))
    )
    (comp (ref "RN5")
      (value "4k7")
      (footprint "eagle-import:RN-9")
      (libsource (lib "eagle-import") (part "RN08"))
    )
    (comp (ref "RN6")
      (value "10k")
      (footprint "eagle-import:RN-9")
      (libsource (lib "eagle-import") (part "RN08"))
    )
    (comp (ref "RN7")
      (value "10k")
      (footprint "eagle-import:RN-9")
      (libsource (lib "eagle-import") (part "RN08"))
    )
    (comp (ref "RN8")
      (value "10k")
      (footprint "eagle-import:RN-9")
      (libsource (lib "eagle-import") (part "RN08"))
    )
    (comp (ref "RN9")
      (value "4k7")
      (footprint "eagle-import:RN-9")
      (libsource (lib "eagle-import") (part "RN08"))
    )
    (comp (ref "T2")
      (value "2N3904")
      (footprint "eagle-import:TO92")
      (libsource (lib "eagle-import") (part "2N3904"))
    )
    (comp (ref "T3")
      (value "2N3904")
      (footprint "eagle-import:TO92")
      (libsource (lib "eagle-import") (part "2N3904"))
    )
    (comp (ref "T4")
      (value "2N3904")
      (footprint "eagle-import:TO92")
      (libsource (lib "eagle-import") (part "2N3904"))
    )
    (comp (ref "T5")
      (value "2N3904")
      (footprint "eagle-import:TO92")
      (libsource (lib "eagle-import") (part "2N3904"))
    )
    (comp (ref "T6")
      (value "2N3904")
      (footprint "eagle-import:TO92")
      (libsource (lib "eagle-import") (part "2N3904"))
    )
    (comp (ref "U$6")
      (value "Monitor")
      (footprint "eagle-import:DIN-13")
      (libsource (lib "eagle-import") (part "13-DIN13PINDIN"))
    )
    (comp (ref "VGA")
      (value "PINHD-2X8")
      (footprint "eagle-import:2X08")
      (libsource (lib "eagle-import") (part "PINHD-2X8"))
    )
    (comp (ref "X1")
      (value "TC46C")
      (footprint "eagle-import:TC46")
      (libsource (lib "eagle-import") (part "TC46C"))
    )
    (comp (ref "C17")
      (value "100p")
      (footprint "eagle-import:C0805")
      (libsource (lib "eagle-import") (part "C-EUC0805"))
    )
    (comp (ref "C18")
      (value "100p")
      (footprint "eagle-import:C0805")
      (libsource (lib "eagle-import") (part "C-EUC0805"))
    )
    (comp (ref "C19")
      (value "100p")
      (footprint "eagle-import:C0805")
      (libsource (lib "eagle-import") (part "C-EUC0805"))
    )
    (comp (ref "C20")
      (value "100p")
      (footprint "eagle-import:C0805")
      (libsource (lib "eagle-import") (part "C-EUC0805"))
    )
    (comp (ref "C36")
      (value "1u")
      (footprint "eagle-import:C0805")
      (libsource (lib "eagle-import") (part "C-EUC0805"))
    )
    (comp (ref "C37")
      (value "1u")
      (footprint "eagle-import:C0805")
      (libsource (lib "eagle-import") (part "C-EUC0805"))
    )
    (comp (ref "C38")
      (value "47u")
      (footprint "eagle-import:E2-5")
      (libsource (lib "eagle-import") (part "CPOL-EUE2-5"))
    )
    (comp (ref "C39")
      (value "100n")
      (footprint "eagle-import:C0805")
      (libsource (lib "eagle-import") (part "C-EUC0805"))
    )
    (comp (ref "C40")
      (value "100n")
      (footprint "eagle-import:C0805")
      (libsource (lib "eagle-import") (part "C-EUC0805"))
    )
    (comp (ref "C42")
      (value "30p")
      (footprint "eagle-import:C0805")
      (libsource (lib "eagle-import") (part "C-EUC0805"))
    )
    (comp (ref "C43")
      (value "30p")
      (footprint "eagle-import:C0805")
      (libsource (lib "eagle-import") (part "C-EUC0805"))
    )
    (comp (ref "C45")
      (value "22u")
      (footprint "eagle-import:C1206")
      (libsource (lib "eagle-import") (part "C-EUC1206"))
    )
    (comp (ref "C46")
      (value "22u")
      (footprint "eagle-import:C1206")
      (libsource (lib "eagle-import") (part "C-EUC1206"))
    )
    (comp (ref "C47")
      (value "10n")
      (footprint "eagle-import:C0805")
      (libsource (lib "eagle-import") (part "C-EUC0805"))
    )
    (comp (ref "C48")
      (value "10n")
      (footprint "eagle-import:C0805")
      (libsource (lib "eagle-import") (part "C-EUC0805"))
    )
    (comp (ref "C49")
      (value "100n")
      (footprint "eagle-import:C0805")
      (libsource (lib "eagle-import") (part "C-EUC0805"))
    )
    (comp (ref "C50")
      (value "4u7")
      (footprint "eagle-import:E2-5")
      (libsource (lib "eagle-import") (part "CPOL-EUE2-5"))
    )
    (comp (ref "C51")
      (value "4u7")
      (footprint "eagle-import:E2-5")
      (libsource (lib "eagle-import") (part "CPOL-EUE2-5"))
    )
    (comp (ref "C52")
      (value "4u7")
      (footprint "eagle-import:E2-5")
      (libsource (lib "eagle-import") (part "CPOL-EUE2-5"))
    )
    (comp (ref "C53")
      (value "100n")
      (footprint "eagle-import:C0805")
      (libsource (lib "eagle-import") (part "C-EUC0805"))
    )
    (comp (ref "C54")
      (value "100n")
      (footprint "eagle-import:C0805")
      (libsource (lib "eagle-import") (part "C-EUC0805"))
    )
    (comp (ref "C55")
      (value "330p")
      (footprint "eagle-import:C0805")
      (libsource (lib "eagle-import") (part "C-EUC0805"))
    )
    (comp (ref "C56")
      (value "150p")
      (footprint "eagle-import:C0805")
      (libsource (lib "eagle-import") (part "C-EUC0805"))
    )
    (comp (ref "C57")
      (value "100n")
      (footprint "eagle-import:C0805")
      (libsource (lib "eagle-import") (part "C-EUC0805"))
    )
    (comp (ref "C58")
      (value "10u")
      (footprint "eagle-import:E2-5")
      (libsource (lib "eagle-import") (part "CPOL-EUE2-5"))
    )
    (comp (ref "D1")
      (value "1N914")
      (footprint "eagle-import:DO35-10")
      (libsource (lib "eagle-import") (part "BAV17"))
    )
    (comp (ref "D8")
      (value "LL4148")
      (footprint "eagle-import:SOD80_DO213AA_MINIMELF")
      (libsource (lib "eagle-import") (part "LL4148"))
    )
    (comp (ref "D9")
      (value "LL4148")
      (footprint "eagle-import:SOD80_DO213AA_MINIMELF")
      (libsource (lib "eagle-import") (part "LL4148"))
    )
    (comp (ref "IC1")
      (value "6850")
      (footprint "eagle-import:DIL24")
      (fields (field (name "MF") "NTE ELECTRONICS") (field (name "MPN") "NTE6850"))
      (libsource (lib "eagle-import") (part "6850"))
    )
    (comp (ref "IC2")
      (value "6850")
      (footprint "eagle-import:DIL24")
      (fields (field (name "MF") "NTE ELECTRONICS") (field (name "MPN") "NTE6850"))
      (libsource (lib "eagle-import") (part "6850"))
    )
    (comp (ref "IC3")
      (value "MC68901P")
      (footprint "eagle-import:DIL48")
      (libsource (lib "eagle-import") (part "MC68901P"))
    )
    (comp (ref "IC7")
      (value "YM2149")
      (footprint "eagle-import:DIL40")
      (libsource (lib "eagle-import") (part "YM2149"))
    )
    (comp (ref "IC9")
      (value "DMA")
      (footprint "eagle-import:DIL40")
      (libsource (lib "eagle-import") (part "DMA"))
    )
    (comp (ref "IC10")
      (value "WD1772")
      (footprint "eagle-import:DIL28")
      (libsource (lib "eagle-import") (part "WD1772"))
    )
    (comp (ref "IC14")
      (value "74LS04N")
      (footprint "eagle-import:DIL14")
      (libsource (lib "eagle-import") (part "7404NLS"))
    )
    (comp (ref "IC15")
      (value "74LS05N")
      (footprint "eagle-import:DIL14")
      (libsource (lib "eagle-import") (part "7405NLS"))
    )
    (comp (ref "IC16")
      (value "74LS02N")
      (footprint "eagle-import:DIL14")
      (libsource (lib "eagle-import") (part "7402NLS"))
    )
    (comp (ref "IC17")
      (value "1488N")
      (footprint "eagle-import:DIL14")
      (libsource (lib "eagle-import") (part "1488N"))
    )
    (comp (ref "IC18")
      (value "1489N")
      (footprint "eagle-import:DIL14")
      (libsource (lib "eagle-import") (part "1489N"))
    )
    (comp (ref "IC19")
      (value "74LS06N")
      (footprint "eagle-import:DIL14")
      (libsource (lib "eagle-import") (part "7406NLS"))
    )
    (comp (ref "IC20")
      (value "74LS06N")
      (footprint "eagle-import:DIL14")
      (libsource (lib "eagle-import") (part "7406NLS"))
    )
    (comp (ref "IC26")
      (value "NE556")
      (footprint "eagle-import:DIL14")
      (libsource (lib "eagle-import") (part "NE556"))
    )
    (comp (ref "IC27")
      (value "TL497")
      (footprint "eagle-import:DIL14")
      (libsource (lib "eagle-import") (part "TL497"))
    )
    (comp (ref "J1")
      (value "AUDIO_JACK_3.5MM_KIT")
      (footprint "eagle-import:AUDIO-JACK-KIT")
      (libsource (lib "eagle-import") (part "AUDIO_JACK_3.5MM_KIT"))
    )
    (comp (ref "J4")
      (value "MIDI_OUT")
      (footprint "eagle-import:DIN5")
      (libsource (lib "eagle-import") (part "DIN5"))
    )
    (comp (ref "J5")
      (value "MIDI_IN")
      (footprint "eagle-import:DIN5")
      (libsource (lib "eagle-import") (part "DIN5"))
    )
    (comp (ref "JP1")
      (value "PINHD-1X2")
      (footprint "eagle-import:1X02")
      (libsource (lib "eagle-import") (part "PINHD-1X2"))
    )
    (comp (ref "JP2")
      (value "PINHD-1X2")
      (footprint "eagle-import:1X02")
      (libsource (lib "eagle-import") (part "PINHD-1X2"))
    )
    (comp (ref "JP5")
      (value "PINHD-2X17")
      (footprint "eagle-import:2X17")
      (libsource (lib "eagle-import") (part "PINHD-2X17"))
    )
    (comp (ref "JP6")
      (value "PINHD-2X10")
      (footprint "eagle-import:2X10")
      (libsource (lib "eagle-import") (part "PINHD-2X10"))
    )
    (comp (ref "JP7")
      (value "RS232")
      (footprint "eagle-import:2X13")
      (libsource (lib "eagle-import") (part "PINHD-2X13"))
    )
    (comp (ref "JP8")
      (value "LPT")
      (footprint "eagle-import:2X13")
      (libsource (lib "eagle-import") (part "PINHD-2X13"))
    )
    (comp (ref "L1")
      (value "L-EU0204/7")
      (footprint "eagle-import:0204_7")
      (libsource (lib "eagle-import") (part "L-EU0204/7"))
    )
    (comp (ref "L3")
      (value "220uH")
      (footprint "eagle-import:0204_7")
      (libsource (lib "eagle-import") (part "L-EU0204/7"))
    )
    (comp (ref "OK1")
      (value "PC900")
      (footprint "eagle-import:DIL06")
      (fields (field (name "MF") "FAIRCHILD SEMICONDUCTOR") (field (name "MPN") "H11L1-M"))
      (libsource (lib "eagle-import") (part "H11LM1"))
    )
    (comp (ref "R7")
      (value "1k")
      (footprint "eagle-import:R0805")
      (libsource (lib "eagle-import") (part "R-EU_R0805"))
    )
    (comp (ref "R8")
      (value "1k")
      (footprint "eagle-import:R0805")
      (libsource (lib "eagle-import") (part "R-EU_R0805"))
    )
    (comp (ref "R9")
      (value "1k")
      (footprint "eagle-import:R0805")
      (libsource (lib "eagle-import") (part "R-EU_R0805"))
    )
    (comp (ref "R10")
      (value "1k")
      (footprint "eagle-import:R0805")
      (libsource (lib "eagle-import") (part "R-EU_R0805"))
    )
    (comp (ref "R11")
      (value "4k7")
      (footprint "eagle-import:R0805")
      (libsource (lib "eagle-import") (part "R-EU_R0805"))
    )
    (comp (ref "R12")
      (value "1k")
      (footprint "eagle-import:R0805")
      (libsource (lib "eagle-import") (part "R-EU_R0805"))
    )
    (comp (ref "R23")
      (value "1k")
      (footprint "eagle-import:R0805")
      (libsource (lib "eagle-import") (part "R-EU_R0805"))
    )
    (comp (ref "R24")
      (value "4k7")
      (footprint "eagle-import:R0805")
      (libsource (lib "eagle-import") (part "R-EU_R0805"))
    )
    (comp (ref "R25")
      (value "220")
      (footprint "eagle-import:R0805")
      (libsource (lib "eagle-import") (part "R-EU_R0805"))
    )
    (comp (ref "R26")
      (value "220")
      (footprint "eagle-import:R0805")
      (libsource (lib "eagle-import") (part "R-EU_R0805"))
    )
    (comp (ref "R27")
      (value "220")
      (footprint "eagle-import:R0805")
      (libsource (lib "eagle-import") (part "R-EU_R0805"))
    )
    (comp (ref "R28")
      (value "220")
      (footprint "eagle-import:R0805")
      (libsource (lib "eagle-import") (part "R-EU_R0805"))
    )
    (comp (ref "R29")
      (value "220")
      (footprint "eagle-import:R0805")
      (libsource (lib "eagle-import") (part "R-EU_R0805"))
    )
    (comp (ref "R30")
      (value "4k7")
      (footprint "eagle-import:R0805")
      (libsource (lib "eagle-import") (part "R-EU_R0805"))
    )
    (comp (ref "R31")
      (value "1k")
      (footprint "eagle-import:R0805")
      (libsource (lib "eagle-import") (part "R-EU_R0805"))
    )
    (comp (ref "R32")
      (value "47")
      (footprint "eagle-import:0204_5")
      (libsource (lib "eagle-import") (part "R-EU_0204/5"))
    )
    (comp (ref "R33")
      (value "47")
      (footprint "eagle-import:0204_5")
      (libsource (lib "eagle-import") (part "R-EU_0204/5"))
    )
    (comp (ref "R34")
      (value "1k")
      (footprint "eagle-import:R0805")
      (libsource (lib "eagle-import") (part "R-EU_R0805"))
    )
    (comp (ref "R35")
      (value "1k")
      (footprint "eagle-import:R0805")
      (libsource (lib "eagle-import") (part "R-EU_R0805"))
    )
    (comp (ref "R36")
      (value "1k")
      (footprint "eagle-import:R0805")
      (libsource (lib "eagle-import") (part "R-EU_R0805"))
    )
    (comp (ref "R37")
      (value "220")
      (footprint "eagle-import:R0805")
      (libsource (lib "eagle-import") (part "R-EU_R0805"))
    )
    (comp (ref "R38")
      (value "1k")
      (footprint "eagle-import:R0805")
      (libsource (lib "eagle-import") (part "R-EU_R0805"))
    )
    (comp (ref "R39")
      (value "1k")
      (footprint "eagle-import:R0805")
      (libsource (lib "eagle-import") (part "R-EU_R0805"))
    )
    (comp (ref "R40")
      (value "3k")
      (footprint "eagle-import:R0805")
      (libsource (lib "eagle-import") (part "R-EU_R0805"))
    )
    (comp (ref "R41")
      (value "8k2")
      (footprint "eagle-import:R0805")
      (libsource (lib "eagle-import") (part "R-EU_R0805"))
    )
    (comp (ref "R42")
      (value "820")
      (footprint "eagle-import:R0805")
      (libsource (lib "eagle-import") (part "R-EU_R0805"))
    )
    (comp (ref "R43")
      (value "220")
      (footprint "eagle-import:R0805")
      (libsource (lib "eagle-import") (part "R-EU_R0805"))
    )
    (comp (ref "R64")
      (value "12k")
      (footprint "eagle-import:R0805")
      (libsource (lib "eagle-import") (part "R-EU_R0805"))
    )
    (comp (ref "R65")
      (value "12k")
      (footprint "eagle-import:R0805")
      (libsource (lib "eagle-import") (part "R-EU_R0805"))
    )
    (comp (ref "R66")
      (value "10k")
      (footprint "eagle-import:R0805")
      (libsource (lib "eagle-import") (part "R-EU_R0805"))
    )
    (comp (ref "R67")
      (value "5.1")
      (footprint "eagle-import:0204_7")
      (libsource (lib "eagle-import") (part "R-EU_0204/7"))
    )
    (comp (ref "R68")
      (value "12k")
      (footprint "eagle-import:R0805")
      (libsource (lib "eagle-import") (part "R-EU_R0805"))
    )
    (comp (ref "R69")
      (value "1k2")
      (footprint "eagle-import:R0805")
      (libsource (lib "eagle-import") (part "R-EU_R0805"))
    )
    (comp (ref "RN10")
      (value "4k7")
      (footprint "eagle-import:RN-10")
      (libsource (lib "eagle-import") (part "RN09"))
    )
    (comp (ref "T1")
      (value "2N3904")
      (footprint "eagle-import:TO92")
      (libsource (lib "eagle-import") (part "2N3904"))
    )
    (comp (ref "X2")
      (value "2.4576MHz")
      (footprint "eagle-import:QS")
      (libsource (lib "eagle-import") (part "XTAL/S"))
    )
  )
  (nets
    (net (code "1") (name "+12V") (class "Default")
      (node (ref "C52") (pin "+") (pinfunction "+_+") (pintype "passive"))
      (node (ref "C54") (pin "1") (pinfunction "1_1") (pintype "passive"))
      (node (ref "IC17") (pin "14") (pinfunction "+12V_14") (pintype "power_in"))
      (node (ref "IC27") (pin "6") (pinfunction "CAT_6") (pintype "bidirectional"))
      (node (ref "R68") (pin "2") (pinfunction "2_2") (pintype "passive"))
      (node (ref "R70") (pin "2") (pinfunction "2_2") (pintype "passive"))
    )
    (net (code "2") (name "+12V_ATX") (class "Default")
      (node (ref "ISA1") (pin "B9") (pinfunction "P_B9") (pintype "passive"))
      (node (ref "X4") (pin "10") (pinfunction "S_10") (pintype "passive"))
    )
    (net (code "3") (name "-12V") (class "Default")
      (node (ref "C51") (pin "-") (pinfunction "-_-") (pintype "passive"))
      (node (ref "C53") (pin "1") (pinfunction "1_1") (pintype "passive"))
      (node (ref "D8") (pin "A") (pinfunction "A_A") (pintype "passive"))
      (node (ref "IC17") (pin "1") (pinfunction "-12V_1") (pintype "power_in"))
    )
    (net (code "4") (name "-12V_ATX") (class "Default")
      (node (ref "ISA1") (pin "B7") (pinfunction "P_B7") (pintype "passive"))
      (node (ref "X4") (pin "12") (pinfunction "S_12") (pintype "passive"))
    )
    (net (code "5") (name "2") (class "Default")
      (node (ref "J5") (pin "2") (pinfunction "2_2") (pintype "power_in"))
    )
    (net (code "6") (name "2MHZ") (class "Default")
      (node (ref "IC5") (pin "54") (pinfunction "2MHZ_54") (pintype "output"))
      (node (ref "IC7") (pin "22") (pinfunction "CLOCK_22") (pintype "input"))
    )
    (net (code "7") (name "4MHZ") (class "Default")
      (node (ref "IC3") (pin "35") (pinfunction "CLK_35") (pintype "input"))
      (node (ref "IC6") (pin "19") (pinfunction "4MHZ_19") (pintype "output"))
    )
    (net (code "8") (name "8MHZ") (class "Default")
      (node (ref "IC10") (pin "18") (pinfunction "CLK_18") (pintype "bidirectional"))
      (node (ref "IC12") (pin "1") (pinfunction "CLK/I0_1") (pintype "input"))
      (node (ref "IC4") (pin "15") (pinfunction "CLK_15") (pintype "input"))
      (node (ref "IC5") (pin "34") (pinfunction "CLK8_34") (pintype "output"))
      (node (ref "IC6") (pin "20") (pinfunction "8MHZ_20") (pintype "output"))
      (node (ref "IC9") (pin "39") (pinfunction "CLK_39") (pintype "input"))
    )
    (net (code "9") (name "16MHZ") (class "Default")
      (node (ref "IC6") (pin "5") (pinfunction "16MHZ_5") (pintype "output"))
      (node (ref "IC8") (pin "39") (pinfunction "16MHZ_39") (pintype "output"))
    )
    (net (code "10") (name "32MHZ") (class "Default")
      (node (ref "C71") (pin "1") (pinfunction "1_1") (pintype "passive"))
      (node (ref "IC33") (pin "4") (pinfunction "O_4") (pintype "output"))
      (node (ref "IC8") (pin "2") (pinfunction "XTL1_2") (pintype "output"))
      (node (ref "L5") (pin "1") (pinfunction "1_1") (pintype "passive"))
      (node (ref "Q2") (pin "2") (pinfunction "2_2") (pintype "passive"))
      (node (ref "R85") (pin "1") (pinfunction "1_1") (pintype "passive"))
      (node (ref "X1") (pin "8") (pinfunction "OUT_8") (pintype "output"))
    )
    (net (code "11") (name "500KHZ") (class "Default")
      (node (ref "IC1") (pin "3") (pinfunction "RXCLK_3") (pintype "input"))
      (node (ref "IC1") (pin "4") (pinfunction "TXCLK_4") (pintype "input"))
      (node (ref "IC2") (pin "3") (pinfunction "RXCLK_3") (pintype "input"))
      (node (ref "IC2") (pin "4") (pinfunction "TXCLK_4") (pintype "input"))
      (node (ref "IC5") (pin "43") (pinfunction "500KHZ_43") (pintype "output"))
    )
    (net (code "12") (name "6850CS") (class "Default")
      (node (ref "IC1") (pin "8") (pinfunction "CS0_8") (pintype "input"))
      (node (ref "IC2") (pin "8") (pinfunction "CS0_8") (pintype "input"))
      (node (ref "IC5") (pin "42") (pinfunction "~{6850CS}_42") (pintype "output"))
    )
    (net (code "13") (name "A1") (class "Default")
      (node (ref "IC1") (pin "11") (pinfunction "RS_11") (pintype "input"))
      (node (ref "IC16") (pin "11") (pinfunction "I0_11") (pintype "input"))
      (node (ref "IC2") (pin "11") (pinfunction "RS_11") (pintype "input"))
      (node (ref "IC3") (pin "2") (pinfunction "RS1_2") (pintype "input"))
      (node (ref "IC31") (pin "12") (pinfunction "A0_12") (pintype "input"))
      (node (ref "IC32") (pin "12") (pinfunction "A0_12") (pintype "input"))
      (node (ref "IC4") (pin "29") (pinfunction "A1_29") (pintype "output"))
      (node (ref "IC5") (pin "56") (pinfunction "A1_56") (pintype "output"))
      (node (ref "IC6") (pin "50") (pinfunction "A1_50") (pintype "output"))
      (node (ref "IC8") (pin "36") (pinfunction "R(1)_36") (pintype "output"))
      (node (ref "IC9") (pin "2") (pinfunction "A1_2") (pintype "input"))
      (node (ref "ISA1") (pin "A30") (pinfunction "P_A30") (pintype "passive"))
      (node (ref "RN8") (pin "6") (pinfunction "6_6") (pintype "passive"))
    )
    (net (code "14") (name "A2") (class "Default")
      (node (ref "IC1") (pin "9") (pinfunction "CS2_9") (pintype "input"))
      (node (ref "IC2") (pin "10") (pinfunction "CS1_10") (pintype "input"))
      (node (ref "IC3") (pin "3") (pinfunction "RS2_3") (pintype "input"))
      (node (ref "IC31") (pin "11") (pinfunction "A1_11") (pintype "input"))
      (node (ref "IC32") (pin "11") (pinfunction "A1_11") (pintype "input"))
      (node (ref "IC4") (pin "30") (pinfunction "A2_30") (pintype "output"))
      (node (ref "IC5") (pin "57") (pinfunction "A2_57") (pintype "output"))
      (node (ref "IC6") (pin "49") (pinfunction "A2_49") (pintype "output"))
      (node (ref "IC8") (pin "35") (pinfunction "R(2)_35") (pintype "output"))
      (node (ref "ISA1") (pin "A29") (pinfunction "P_A29") (pintype "passive"))
      (node (ref "JP4") (pin "35") (pinfunction "35_35") (pintype "passive"))
      (node (ref "RN8") (pin "7") (pinfunction "7_7") (pintype "passive"))
    )
    (net (code "15") (name "A3") (class "Default")
      (node (ref "IC3") (pin "4") (pinfunction "RS3_4") (pintype "input"))
      (node (ref "IC31") (pin "10") (pinfunction "A2_10") (pintype "input"))
      (node (ref "IC32") (pin "10") (pinfunction "A2_10") (pintype "input"))
      (node (ref "IC4") (pin "31") (pinfunction "A3_31") (pintype "output"))
      (node (ref "IC5") (pin "58") (pinfunction "A3_58") (pintype "output"))
      (node (ref "IC6") (pin "48") (pinfunction "A3_48") (pintype "output"))
      (node (ref "IC8") (pin "34") (pinfunction "R(3)_34") (pintype "output"))
      (node (ref "ISA1") (pin "A28") (pinfunction "P_A28") (pintype "passive"))
      (node (ref "JP4") (pin "33") (pinfunction "33_33") (pintype "passive"))
      (node (ref "RN8") (pin "8") (pinfunction "8_8") (pintype "passive"))
    )
    (net (code "16") (name "A4") (class "Default")
      (node (ref "IC3") (pin "5") (pinfunction "RS4_5") (pintype "input"))
      (node (ref "IC31") (pin "9") (pinfunction "A3_9") (pintype "input"))
      (node (ref "IC32") (pin "9") (pinfunction "A3_9") (pintype "input"))
      (node (ref "IC4") (pin "32") (pinfunction "A4_32") (pintype "output"))
      (node (ref "IC5") (pin "59") (pinfunction "A4_59") (pintype "output"))
      (node (ref "IC6") (pin "47") (pinfunction "A4_47") (pintype "output"))
      (node (ref "IC8") (pin "33") (pinfunction "R(4)_33") (pintype "output"))
      (node (ref "ISA1") (pin "A27") (pinfunction "P_A27") (pintype "passive"))
      (node (ref "JP4") (pin "36") (pinfunction "36_36") (pintype "passive"))
      (node (ref "RN8") (pin "9") (pinfunction "9_9") (pintype "passive"))
    )
    (net (code "17") (name "A5") (class "Default")
      (node (ref "IC11") (pin "11") (pinfunction "I9_11") (pintype "input"))
      (node (ref "IC3") (pin "6") (pinfunction "RS5_6") (pintype "input"))
      (node (ref "IC31") (pin "8") (pinfunction "A4_8") (pintype "input"))
      (node (ref "IC32") (pin "8") (pinfunction "A4_8") (pintype "input"))
      (node (ref "IC4") (pin "33") (pinfunction "A5_33") (pintype "output"))
      (node (ref "IC5") (pin "60") (pinfunction "A5_60") (pintype "output"))
      (node (ref "IC6") (pin "46") (pinfunction "A5_46") (pintype "output"))
      (node (ref "IC8") (pin "32") (pinfunction "R(5)_32") (pintype "output"))
      (node (ref "ISA1") (pin "A26") (pinfunction "P_A26") (pintype "passive"))
      (node (ref "RN7") (pin "2") (pinfunction "2_2") (pintype "passive"))
    )
    (net (code "18") (name "A6") (class "Default")
      (node (ref "IC31") (pin "7") (pinfunction "A5_7") (pintype "input"))
      (node (ref "IC32") (pin "7") (pinfunction "A5_7") (pintype "input"))
      (node (ref "IC4") (pin "34") (pinfunction "A6_34") (pintype "output"))
      (node (ref "IC5") (pin "61") (pinfunction "A6_61") (pintype "output"))
      (node (ref "IC6") (pin "45") (pinfunction "A6_45") (pintype "output"))
      (node (ref "ISA1") (pin "A25") (pinfunction "P_A25") (pintype "passive"))
      (node (ref "RN7") (pin "3") (pinfunction "3_3") (pintype "passive"))
    )
    (net (code "19") (name "A7") (class "Default")
      (node (ref "IC31") (pin "6") (pinfunction "A6_6") (pintype "input"))
      (node (ref "IC32") (pin "6") (pinfunction "A6_6") (pintype "input"))
      (node (ref "IC4") (pin "35") (pinfunction "A7_35") (pintype "output"))
      (node (ref "IC5") (pin "62") (pinfunction "A7_62") (pintype "output"))
      (node (ref "IC6") (pin "43") (pinfunction "A7_43") (pintype "output"))
      (node (ref "ISA1") (pin "A24") (pinfunction "P_A24") (pintype "passive"))
      (node (ref "RN7") (pin "4") (pinfunction "4_4") (pintype "passive"))
    )
    (net (code "20") (name "A8") (class "Default")
      (node (ref "IC31") (pin "5") (pinfunction "A7_5") (pintype "input"))
      (node (ref "IC32") (pin "5") (pinfunction "A7_5") (pintype "input"))
      (node (ref "IC4") (pin "36") (pinfunction "A8_36") (pintype "output"))
      (node (ref "IC5") (pin "63") (pinfunction "A8_63") (pintype "output"))
      (node (ref "IC6") (pin "42") (pinfunction "A8_42") (pintype "output"))
      (node (ref "ISA1") (pin "A23") (pinfunction "P_A23") (pintype "passive"))
      (node (ref "RN7") (pin "5") (pinfunction "5_5") (pintype "passive"))
    )
    (net (code "21") (name "A9") (class "Default")
      (node (ref "IC31") (pin "27") (pinfunction "A8_27") (pintype "input"))
      (node (ref "IC32") (pin "27") (pinfunction "A8_27") (pintype "input"))
      (node (ref "IC4") (pin "37") (pinfunction "A9_37") (pintype "output"))
      (node (ref "IC5") (pin "64") (pinfunction "A9_64") (pintype "output"))
      (node (ref "IC6") (pin "41") (pinfunction "A9_41") (pintype "output"))
      (node (ref "ISA1") (pin "A22") (pinfunction "P_A22") (pintype "passive"))
      (node (ref "RN7") (pin "6") (pinfunction "6_6") (pintype "passive"))
    )
    (net (code "22") (name "A10") (class "Default")
      (node (ref "IC31") (pin "26") (pinfunction "A9_26") (pintype "input"))
      (node (ref "IC32") (pin "26") (pinfunction "A9_26") (pintype "input"))
      (node (ref "IC4") (pin "38") (pinfunction "A10_38") (pintype "output"))
      (node (ref "IC5") (pin "65") (pinfunction "A10_65") (pintype "output"))
      (node (ref "IC6") (pin "40") (pinfunction "A10_40") (pintype "output"))
      (node (ref "ISA1") (pin "A21") (pinfunction "P_A21") (pintype "passive"))
      (node (ref "RN7") (pin "7") (pinfunction "7_7") (pintype "passive"))
    )
    (net (code "23") (name "A11") (class "Default")
      (node (ref "IC31") (pin "23") (pinfunction "A10_23") (pintype "input"))
      (node (ref "IC32") (pin "23") (pinfunction "A10_23") (pintype "input"))
      (node (ref "IC4") (pin "39") (pinfunction "A11_39") (pintype "output"))
      (node (ref "IC5") (pin "66") (pinfunction "A11_66") (pintype "output"))
      (node (ref "IC6") (pin "39") (pinfunction "A11_39") (pintype "output"))
      (node (ref "ISA1") (pin "A20") (pinfunction "P_A20") (pintype "passive"))
      (node (ref "RN7") (pin "8") (pinfunction "8_8") (pintype "passive"))
    )
    (net (code "24") (name "A12") (class "Default")
      (node (ref "IC31") (pin "25") (pinfunction "A11_25") (pintype "input"))
      (node (ref "IC32") (pin "25") (pinfunction "A11_25") (pintype "input"))
      (node (ref "IC4") (pin "40") (pinfunction "A12_40") (pintype "output"))
      (node (ref "IC5") (pin "67") (pinfunction "A12_67") (pintype "output"))
      (node (ref "IC6") (pin "38") (pinfunction "A12_38") (pintype "output"))
      (node (ref "ISA1") (pin "A19") (pinfunction "P_A19") (pintype "passive"))
      (node (ref "RN7") (pin "9") (pinfunction "9_9") (pintype "passive"))
    )
    (net (code "25") (name "A13") (class "Default")
      (node (ref "IC31") (pin "4") (pinfunction "A12_4") (pintype "input"))
      (node (ref "IC32") (pin "4") (pinfunction "A12_4") (pintype "input"))
      (node (ref "IC4") (pin "41") (pinfunction "A13_41") (pintype "output"))
      (node (ref "IC5") (pin "68") (pinfunction "A13_68") (pintype "output"))
      (node (ref "IC6") (pin "37") (pinfunction "A13_37") (pintype "output"))
      (node (ref "ISA1") (pin "A18") (pinfunction "P_A18") (pintype "passive"))
      (node (ref "RN6") (pin "9") (pinfunction "9_9") (pintype "passive"))
    )
    (net (code "26") (name "A14") (class "Default")
      (node (ref "IC11") (pin "10") (pinfunction "I8_10") (pintype "input"))
      (node (ref "IC31") (pin "28") (pinfunction "A13_28") (pintype "input"))
      (node (ref "IC32") (pin "28") (pinfunction "A13_28") (pintype "input"))
      (node (ref "IC4") (pin "42") (pinfunction "A14_42") (pintype "output"))
      (node (ref "IC5") (pin "2") (pinfunction "A14_2") (pintype "output"))
      (node (ref "IC6") (pin "36") (pinfunction "A14_36") (pintype "output"))
      (node (ref "ISA1") (pin "A17") (pinfunction "P_A17") (pintype "passive"))
      (node (ref "RN6") (pin "8") (pinfunction "8_8") (pintype "passive"))
    )
    (net (code "27") (name "A15") (class "Default")
      (node (ref "IC11") (pin "9") (pinfunction "I7_9") (pintype "input"))
      (node (ref "IC31") (pin "29") (pinfunction "A14_29") (pintype "input"))
      (node (ref "IC32") (pin "29") (pinfunction "A14_29") (pintype "input"))
      (node (ref "IC4") (pin "43") (pinfunction "A15_43") (pintype "output"))
      (node (ref "IC5") (pin "3") (pinfunction "A15_3") (pintype "output"))
      (node (ref "IC6") (pin "35") (pinfunction "A15_35") (pintype "output"))
      (node (ref "ISA1") (pin "A16") (pinfunction "P_A16") (pintype "passive"))
      (node (ref "RN6") (pin "7") (pinfunction "7_7") (pintype "passive"))
    )
    (net (code "28") (name "A16") (class "Default")
      (node (ref "IC11") (pin "8") (pinfunction "I6_8") (pintype "input"))
      (node (ref "IC12") (pin "23") (pinfunction "I12_23") (pintype "input"))
      (node (ref "IC31") (pin "3") (pinfunction "A15_3") (pintype "input"))
      (node (ref "IC32") (pin "3") (pinfunction "A15_3") (pintype "input"))
      (node (ref "IC4") (pin "44") (pinfunction "A16_44") (pintype "output"))
      (node (ref "IC5") (pin "4") (pinfunction "A16_4") (pintype "output"))
      (node (ref "IC6") (pin "11") (pinfunction "A16_11") (pintype "output"))
      (node (ref "ISA1") (pin "A15") (pinfunction "P_A15") (pintype "passive"))
      (node (ref "RN6") (pin "6") (pinfunction "6_6") (pintype "passive"))
    )
    (net (code "29") (name "A17") (class "Default")
      (node (ref "IC11") (pin "7") (pinfunction "I5_7") (pintype "input"))
      (node (ref "IC12") (pin "22") (pinfunction "O7_22") (pintype "bidirectional"))
      (node (ref "IC31") (pin "2") (pinfunction "A16_2") (pintype "input"))
      (node (ref "IC32") (pin "2") (pinfunction "A16_2") (pintype "input"))
      (node (ref "IC4") (pin "45") (pinfunction "A17_45") (pintype "output"))
      (node (ref "IC5") (pin "5") (pinfunction "A17_5") (pintype "output"))
      (node (ref "IC6") (pin "12") (pinfunction "A17_12") (pintype "output"))
      (node (ref "ISA1") (pin "A14") (pinfunction "P_A14") (pintype "passive"))
      (node (ref "ISA1") (pin "C8") (pinfunction "P_C8") (pintype "passive"))
      (node (ref "RN6") (pin "5") (pinfunction "5_5") (pintype "passive"))
    )
    (net (code "30") (name "A18") (class "Default")
      (node (ref "IC11") (pin "6") (pinfunction "I4_6") (pintype "input"))
      (node (ref "IC12") (pin "2") (pinfunction "I0_2") (pintype "input"))
      (node (ref "IC4") (pin "46") (pinfunction "A18_46") (pintype "output"))
      (node (ref "IC5") (pin "6") (pinfunction "A18_6") (pintype "output"))
      (node (ref "IC6") (pin "13") (pinfunction "A18_13") (pintype "output"))
      (node (ref "ISA1") (pin "A13") (pinfunction "P_A13") (pintype "passive"))
      (node (ref "ISA1") (pin "C7") (pinfunction "P_C7") (pintype "passive"))
      (node (ref "RN6") (pin "4") (pinfunction "4_4") (pintype "passive"))
    )
    (net (code "31") (name "A19") (class "Default")
      (node (ref "IC11") (pin "5") (pinfunction "I3_5") (pintype "input"))
      (node (ref "IC12") (pin "3") (pinfunction "I1_3") (pintype "input"))
      (node (ref "IC4") (pin "47") (pinfunction "A19_47") (pintype "output"))
      (node (ref "IC5") (pin "7") (pinfunction "A19_7") (pintype "output"))
      (node (ref "IC6") (pin "14") (pinfunction "A19_14") (pintype "output"))
      (node (ref "ISA1") (pin "A12") (pinfunction "P_A12") (pintype "passive"))
      (node (ref "ISA1") (pin "C6") (pinfunction "P_C6") (pintype "passive"))
      (node (ref "RN6") (pin "3") (pinfunction "3_3") (pintype "passive"))
    )
    (net (code "32") (name "A20") (class "Default")
      (node (ref "IC11") (pin "4") (pinfunction "I2_4") (pintype "input"))
      (node (ref "IC12") (pin "4") (pinfunction "I2_4") (pintype "input"))
      (node (ref "IC4") (pin "48") (pinfunction "A20_48") (pintype "output"))
      (node (ref "IC5") (pin "8") (pinfunction "A20_8") (pintype "output"))
      (node (ref "IC6") (pin "15") (pinfunction "A20_15") (pintype "output"))
      (node (ref "RN6") (pin "2") (pinfunction "2_2") (pintype "passive"))
    )
    (net (code "33") (name "A21") (class "Default")
      (node (ref "IC11") (pin "3") (pinfunction "I1_3") (pintype "input"))
      (node (ref "IC12") (pin "5") (pinfunction "I3_5") (pintype "input"))
      (node (ref "IC4") (pin "50") (pinfunction "A21_50") (pintype "output"))
      (node (ref "IC5") (pin "9") (pinfunction "A21_9") (pintype "output"))
      (node (ref "IC6") (pin "16") (pinfunction "A21_16") (pintype "output"))
      (node (ref "R46") (pin "1") (pinfunction "1_1") (pintype "passive"))
    )
    (net (code "34") (name "A22") (class "Default")
      (node (ref "IC11") (pin "2") (pinfunction "I0_2") (pintype "input"))
      (node (ref "IC12") (pin "6") (pinfunction "I4_6") (pintype "input"))
      (node (ref "IC4") (pin "51") (pinfunction "A22_51") (pintype "output"))
      (node (ref "IC5") (pin "10") (pinfunction "A22_10") (pintype "output"))
      (node (ref "R45") (pin "1") (pinfunction "1_1") (pintype "passive"))
    )
    (net (code "35") (name "A23") (class "Default")
      (node (ref "IC11") (pin "1") (pinfunction "CLK/I0_1") (pintype "input"))
      (node (ref "IC12") (pin "7") (pinfunction "I5_7") (pintype "input"))
      (node (ref "IC4") (pin "52") (pinfunction "A23_52") (pintype "output"))
      (node (ref "IC5") (pin "11") (pinfunction "A23_11") (pintype "output"))
      (node (ref "R44") (pin "1") (pinfunction "1_1") (pintype "passive"))
    )
    (net (code "36") (name "ACSI10") (class "Default")
      (node (ref "IC14") (pin "5") (pinfunction "I_5") (pintype "input"))
      (node (ref "IC30") (pin "3") (pinfunction "O_3") (pintype "open_collector"))
      (node (ref "JP6") (pin "10") (pinfunction "10_10") (pintype "passive"))
      (node (ref "R23") (pin "1") (pinfunction "1_1") (pintype "passive"))
    )
    (net (code "37") (name "AS") (class "Default")
      (node (ref "IC11") (pin "13") (pinfunction "OE/I10_13") (pintype "input"))
      (node (ref "IC12") (pin "8") (pinfunction "I6_8") (pintype "input"))
      (node (ref "IC4") (pin "6") (pinfunction "AS_6") (pintype "output"))
      (node (ref "IC5") (pin "12") (pinfunction "~{AS}_12") (pintype "output"))
      (node (ref "IC6") (pin "32") (pinfunction "~{AS}_32") (pintype "output"))
      (node (ref "RN5") (pin "9") (pinfunction "9_9") (pintype "passive"))
    )
    (net (code "38") (name "AUDIO_IN") (class "Default")
      (node (ref "C36") (pin "1") (pinfunction "1_1") (pintype "passive"))
      (node (ref "U$6") (pin "PIN5") (pinfunction "PIN5_PIN5") (pintype "bidirectional"))
    )
    (net (code "39") (name "AUDIO_OUT") (class "Default")
      (node (ref "C38") (pin "-") (pinfunction "-_-") (pintype "passive"))
      (node (ref "J1") (pin "RING") (pinfunction "RING_RING") (pintype "bidirectional"))
      (node (ref "J1") (pin "TIP") (pinfunction "TIP_TIP") (pintype "bidirectional"))
      (node (ref "U$6") (pin "PIN1") (pinfunction "PIN1_PIN1") (pintype "bidirectional"))
    )
    (net (code "40") (name "B") (class "Default")
      (node (ref "R59") (pin "1") (pinfunction "1_1") (pintype "passive"))
      (node (ref "U$6") (pin "PIN10") (pinfunction "PIN10_PIN10") (pintype "bidirectional"))
    )
    (net (code "41") (name "B2") (class "Default")
      (node (ref "R73") (pin "1") (pinfunction "1_1") (pintype "passive"))
      (node (ref "VGA") (pin "3") (pinfunction "3_3") (pintype "passive"))
    )
    (net (code "42") (name "B13") (class "Default")
      (node (ref "IC12") (pin "17") (pinfunction "O2_17") (pintype "bidirectional"))
      (node (ref "ISA1") (pin "B13") (pinfunction "P_B13") (pintype "passive"))
    )
    (net (code "43") (name "B14") (class "Default")
      (node (ref "IC12") (pin "18") (pinfunction "O3_18") (pintype "bidirectional"))
      (node (ref "ISA1") (pin "B14") (pinfunction "P_B14") (pintype "passive"))
    )
    (net (code "44") (name "BERR") (class "Default")
      (node (ref "IC4") (pin "22") (pinfunction "BERR_22") (pintype "input"))
      (node (ref "IC5") (pin "30") (pinfunction "~{BERR}_30") (pintype "input"))
      (node (ref "RN9") (pin "6") (pinfunction "6_6") (pintype "passive"))
    )
    (net (code "45") (name "BUSY") (class "Default")
      (node (ref "IC3") (pin "19") (pinfunction "TAI_19") (pintype "input"))
      (node (ref "IC3") (pin "22") (pinfunction "I0_22") (pintype "bidirectional"))
      (node (ref "JP8") (pin "11") (pinfunction "11_11") (pintype "passive"))
      (node (ref "R7") (pin "1") (pinfunction "1_1") (pintype "passive"))
    )
    (net (code "46") (name "CAS0H") (class "Default")
      (node (ref "JP9") (pin "23") (pinfunction "23_23") (pintype "passive"))
      (node (ref "R1") (pin "2") (pinfunction "2_2") (pintype "passive"))
    )
    (net (code "47") (name "CAS0L") (class "Default")
      (node (ref "JP9") (pin "21") (pinfunction "21_21") (pintype "passive"))
      (node (ref "R2") (pin "2") (pinfunction "2_2") (pintype "passive"))
    )
    (net (code "48") (name "CAS1H") (class "Default")
      (node (ref "JP9") (pin "24") (pinfunction "24_24") (pintype "passive"))
      (node (ref "R5") (pin "2") (pinfunction "2_2") (pintype "passive"))
    )
    (net (code "49") (name "CAS1L") (class "Default")
      (node (ref "JP9") (pin "22") (pinfunction "22_22") (pintype "passive"))
      (node (ref "R6") (pin "2") (pinfunction "2_2") (pintype "passive"))
    )
    (net (code "50") (name "CE1") (class "Default")
      (node (ref "IC11") (pin "21") (pinfunction "O6_21") (pintype "bidirectional"))
      (node (ref "IC21") (pin "4") (pinfunction "I1_4") (pintype "input"))
    )
    (net (code "51") (name "CE2") (class "Default")
      (node (ref "IC11") (pin "22") (pinfunction "O7_22") (pintype "bidirectional"))
      (node (ref "IC21") (pin "5") (pinfunction "I2_5") (pintype "input"))
    )
    (net (code "52") (name "CSYNC") (class "Default")
      (node (ref "R74") (pin "1") (pinfunction "1_1") (pintype "passive"))
      (node (ref "U$6") (pin "PIN2") (pinfunction "PIN2_PIN2") (pintype "bidirectional"))
    )
    (net (code "53") (name "D0") (class "Default")
      (node (ref "IC23") (pin "12") (pinfunction "5Q_12") (pintype "tri_state"))
      (node (ref "IC25") (pin "11") (pinfunction "A1_11") (pintype "input"))
      (node (ref "IC29") (pin "8") (pinfunction "A7_8") (pintype "bidirectional"))
      (node (ref "IC3") (pin "37") (pinfunction "D0_37") (pintype "bidirectional"))
      (node (ref "IC31") (pin "13") (pinfunction "O0_13") (pintype "tri_state"))
      (node (ref "IC4") (pin "5") (pinfunction "D0_5") (pintype "bidirectional"))
      (node (ref "IC6") (pin "65") (pinfunction "D0_65") (pintype "bidirectional"))
      (node (ref "IC9") (pin "4") (pinfunction "D0_4") (pintype "bidirectional"))
      (node (ref "ISA1") (pin "C11") (pinfunction "P_C11") (pintype "passive"))
      (node (ref "RN4") (pin "9") (pinfunction "9_9") (pintype "passive"))
    )
    (net (code "54") (name "D0'") (class "Default")
      (node (ref "IC29") (pin "12") (pinfunction "B7_12") (pintype "bidirectional"))
      (node (ref "JP4") (pin "17") (pinfunction "17_17") (pintype "passive"))
    )
    (net (code "55") (name "D1") (class "Default")
      (node (ref "IC23") (pin "15") (pinfunction "6Q_15") (pintype "tri_state"))
      (node (ref "IC25") (pin "13") (pinfunction "A2_13") (pintype "input"))
      (node (ref "IC29") (pin "6") (pinfunction "A5_6") (pintype "bidirectional"))
      (node (ref "IC3") (pin "38") (pinfunction "D1_38") (pintype "bidirectional"))
      (node (ref "IC31") (pin "14") (pinfunction "O1_14") (pintype "tri_state"))
      (node (ref "IC4") (pin "4") (pinfunction "D1_4") (pintype "bidirectional"))
      (node (ref "IC6") (pin "66") (pinfunction "D1_66") (pintype "bidirectional"))
      (node (ref "IC9") (pin "5") (pinfunction "D1_5") (pintype "bidirectional"))
      (node (ref "ISA1") (pin "C12") (pinfunction "P_C12") (pintype "passive"))
      (node (ref "RN4") (pin "8") (pinfunction "8_8") (pintype "passive"))
    )
    (net (code "56") (name "D1'") (class "Default")
      (node (ref "IC29") (pin "14") (pinfunction "B5_14") (pintype "bidirectional"))
      (node (ref "JP4") (pin "15") (pinfunction "15_15") (pintype "passive"))
    )
    (net (code "57") (name "D2") (class "Default")
      (node (ref "IC23") (pin "16") (pinfunction "7Q_16") (pintype "tri_state"))
      (node (ref "IC25") (pin "15") (pinfunction "A3_15") (pintype "input"))
      (node (ref "IC29") (pin "4") (pinfunction "A3_4") (pintype "bidirectional"))
      (node (ref "IC3") (pin "39") (pinfunction "D2_39") (pintype "bidirectional"))
      (node (ref "IC31") (pin "15") (pinfunction "O2_15") (pintype "tri_state"))
      (node (ref "IC4") (pin "3") (pinfunction "D2_3") (pintype "bidirectional"))
      (node (ref "IC6") (pin "67") (pinfunction "D2_67") (pintype "bidirectional"))
      (node (ref "IC9") (pin "6") (pinfunction "D2_6") (pintype "bidirectional"))
      (node (ref "ISA1") (pin "C13") (pinfunction "P_C13") (pintype "passive"))
      (node (ref "RN4") (pin "7") (pinfunction "7_7") (pintype "passive"))
    )
    (net (code "58") (name "D2'") (class "Default")
      (node (ref "IC29") (pin "16") (pinfunction "B3_16") (pintype "bidirectional"))
      (node (ref "JP4") (pin "13") (pinfunction "13_13") (pintype "passive"))
    )
    (net (code "59") (name "D3") (class "Default")
      (node (ref "IC23") (pin "19") (pinfunction "8Q_19") (pintype "tri_state"))
      (node (ref "IC25") (pin "17") (pinfunction "A4_17") (pintype "input"))
      (node (ref "IC29") (pin "2") (pinfunction "A1_2") (pintype "bidirectional"))
      (node (ref "IC3") (pin "40") (pinfunction "D3_40") (pintype "bidirectional"))
      (node (ref "IC31") (pin "17") (pinfunction "O3_17") (pintype "tri_state"))
      (node (ref "IC4") (pin "2") (pinfunction "D3_2") (pintype "bidirectional"))
      (node (ref "IC6") (pin "68") (pinfunction "D3_68") (pintype "bidirectional"))
      (node (ref "IC9") (pin "7") (pinfunction "D3_7") (pintype "bidirectional"))
      (node (ref "ISA1") (pin "C14") (pinfunction "P_C14") (pintype "passive"))
      (node (ref "RN4") (pin "6") (pinfunction "6_6") (pintype "passive"))
    )
    (net (code "60") (name "D3'") (class "Default")
      (node (ref "IC29") (pin "18") (pinfunction "B1_18") (pintype "bidirectional"))
      (node (ref "JP4") (pin "11") (pinfunction "11_11") (pintype "passive"))
    )
    (net (code "61") (name "D4") (class "Default")
      (node (ref "IC23") (pin "2") (pinfunction "1Q_2") (pintype "tri_state"))
      (node (ref "IC25") (pin "2") (pinfunction "A1_2") (pintype "input"))
      (node (ref "IC28") (pin "8") (pinfunction "A7_8") (pintype "bidirectional"))
      (node (ref "IC3") (pin "41") (pinfunction "D4_41") (pintype "bidirectional"))
      (node (ref "IC31") (pin "18") (pinfunction "O4_18") (pintype "tri_state"))
      (node (ref "IC4") (pin "1") (pinfunction "D4_1") (pintype "bidirectional"))
      (node (ref "IC6") (pin "1") (pinfunction "D4_1") (pintype "bidirectional"))
      (node (ref "IC9") (pin "8") (pinfunction "D4_8") (pintype "bidirectional"))
      (node (ref "ISA1") (pin "C15") (pinfunction "P_C15") (pintype "passive"))
      (node (ref "RN4") (pin "5") (pinfunction "5_5") (pintype "passive"))
    )
    (net (code "62") (name "D4'") (class "Default")
      (node (ref "IC28") (pin "12") (pinfunction "B7_12") (pintype "bidirectional"))
      (node (ref "JP4") (pin "9") (pinfunction "9_9") (pintype "passive"))
    )
    (net (code "63") (name "D5") (class "Default")
      (node (ref "IC23") (pin "5") (pinfunction "2Q_5") (pintype "tri_state"))
      (node (ref "IC25") (pin "4") (pinfunction "A2_4") (pintype "input"))
      (node (ref "IC28") (pin "6") (pinfunction "A5_6") (pintype "bidirectional"))
      (node (ref "IC3") (pin "42") (pinfunction "D5_42") (pintype "bidirectional"))
      (node (ref "IC31") (pin "19") (pinfunction "O5_19") (pintype "tri_state"))
      (node (ref "IC4") (pin "64") (pinfunction "D5_64") (pintype "bidirectional"))
      (node (ref "IC6") (pin "2") (pinfunction "D5_2") (pintype "bidirectional"))
      (node (ref "IC9") (pin "9") (pinfunction "D5_9") (pintype "bidirectional"))
      (node (ref "ISA1") (pin "C16") (pinfunction "P_C16") (pintype "passive"))
      (node (ref "RN4") (pin "4") (pinfunction "4_4") (pintype "passive"))
    )
    (net (code "64") (name "D5'") (class "Default")
      (node (ref "IC28") (pin "14") (pinfunction "B5_14") (pintype "bidirectional"))
      (node (ref "JP4") (pin "7") (pinfunction "7_7") (pintype "passive"))
    )
    (net (code "65") (name "D6") (class "Default")
      (node (ref "IC23") (pin "6") (pinfunction "3Q_6") (pintype "tri_state"))
      (node (ref "IC25") (pin "6") (pinfunction "A3_6") (pintype "input"))
      (node (ref "IC28") (pin "4") (pinfunction "A3_4") (pintype "bidirectional"))
      (node (ref "IC3") (pin "43") (pinfunction "D6_43") (pintype "bidirectional"))
      (node (ref "IC31") (pin "20") (pinfunction "O6_20") (pintype "tri_state"))
      (node (ref "IC4") (pin "63") (pinfunction "D6_63") (pintype "bidirectional"))
      (node (ref "IC6") (pin "3") (pinfunction "D6_3") (pintype "bidirectional"))
      (node (ref "IC9") (pin "10") (pinfunction "D6_10") (pintype "bidirectional"))
      (node (ref "ISA1") (pin "C17") (pinfunction "P_C17") (pintype "passive"))
      (node (ref "RN4") (pin "3") (pinfunction "3_3") (pintype "passive"))
    )
    (net (code "66") (name "D6'") (class "Default")
      (node (ref "IC28") (pin "16") (pinfunction "B3_16") (pintype "bidirectional"))
      (node (ref "JP4") (pin "5") (pinfunction "5_5") (pintype "passive"))
    )
    (net (code "67") (name "D7") (class "Default")
      (node (ref "IC23") (pin "9") (pinfunction "4Q_9") (pintype "tri_state"))
      (node (ref "IC25") (pin "8") (pinfunction "A4_8") (pintype "input"))
      (node (ref "IC28") (pin "2") (pinfunction "A1_2") (pintype "bidirectional"))
      (node (ref "IC3") (pin "44") (pinfunction "D7_44") (pintype "bidirectional"))
      (node (ref "IC31") (pin "21") (pinfunction "O7_21") (pintype "tri_state"))
      (node (ref "IC4") (pin "62") (pinfunction "D7_62") (pintype "bidirectional"))
      (node (ref "IC6") (pin "4") (pinfunction "D7_4") (pintype "bidirectional"))
      (node (ref "IC9") (pin "11") (pinfunction "D7_11") (pintype "bidirectional"))
      (node (ref "ISA1") (pin "C18") (pinfunction "P_C18") (pintype "passive"))
      (node (ref "RN4") (pin "2") (pinfunction "2_2") (pintype "passive"))
    )
    (net (code "68") (name "D7'") (class "Default")
      (node (ref "IC28") (pin "18") (pinfunction "B1_18") (pintype "bidirectional"))
      (node (ref "JP4") (pin "3") (pinfunction "3_3") (pintype "passive"))
    )
    (net (code "69") (name "D8") (class "Default")
      (node (ref "IC1") (pin "22") (pinfunction "D0_22") (pintype "bidirectional"))
      (node (ref "IC2") (pin "22") (pinfunction "D0_22") (pintype "bidirectional"))
      (node (ref "IC22") (pin "12") (pinfunction "5Q_12") (pintype "tri_state"))
      (node (ref "IC24") (pin "11") (pinfunction "A1_11") (pintype "input"))
      (node (ref "IC28") (pin "3") (pinfunction "A2_3") (pintype "bidirectional"))
      (node (ref "IC32") (pin "13") (pinfunction "O0_13") (pintype "tri_state"))
      (node (ref "IC4") (pin "61") (pinfunction "D8_61") (pintype "bidirectional"))
      (node (ref "IC5") (pin "48") (pinfunction "D0_48") (pintype "bidirectional"))
      (node (ref "IC7") (pin "37") (pinfunction "D0_37") (pintype "bidirectional"))
      (node (ref "IC9") (pin "12") (pinfunction "D8_12") (pintype "bidirectional"))
      (node (ref "ISA1") (pin "A9") (pinfunction "P_A9") (pintype "passive"))
      (node (ref "RN3") (pin "9") (pinfunction "9_9") (pintype "passive"))
    )
    (net (code "70") (name "D8'") (class "Default")
      (node (ref "IC28") (pin "17") (pinfunction "B2_17") (pintype "bidirectional"))
      (node (ref "JP4") (pin "4") (pinfunction "4_4") (pintype "passive"))
    )
    (net (code "71") (name "D9") (class "Default")
      (node (ref "IC1") (pin "21") (pinfunction "D1_21") (pintype "bidirectional"))
      (node (ref "IC2") (pin "21") (pinfunction "D1_21") (pintype "bidirectional"))
      (node (ref "IC22") (pin "9") (pinfunction "4Q_9") (pintype "tri_state"))
      (node (ref "IC24") (pin "8") (pinfunction "A4_8") (pintype "input"))
      (node (ref "IC28") (pin "5") (pinfunction "A4_5") (pintype "bidirectional"))
      (node (ref "IC32") (pin "14") (pinfunction "O1_14") (pintype "tri_state"))
      (node (ref "IC4") (pin "60") (pinfunction "D9_60") (pintype "bidirectional"))
      (node (ref "IC5") (pin "49") (pinfunction "D1_49") (pintype "bidirectional"))
      (node (ref "IC7") (pin "36") (pinfunction "D1_36") (pintype "bidirectional"))
      (node (ref "IC9") (pin "13") (pinfunction "D9_13") (pintype "bidirectional"))
      (node (ref "ISA1") (pin "A8") (pinfunction "P_A8") (pintype "passive"))
      (node (ref "RN3") (pin "8") (pinfunction "8_8") (pintype "passive"))
    )
    (net (code "72") (name "D9'") (class "Default")
      (node (ref "IC28") (pin "15") (pinfunction "B4_15") (pintype "bidirectional"))
      (node (ref "JP4") (pin "6") (pinfunction "6_6") (pintype "passive"))
    )
    (net (code "73") (name "D10") (class "Default")
      (node (ref "IC1") (pin "20") (pinfunction "D2_20") (pintype "bidirectional"))
      (node (ref "IC2") (pin "20") (pinfunction "D2_20") (pintype "bidirectional"))
      (node (ref "IC22") (pin "15") (pinfunction "6Q_15") (pintype "tri_state"))
      (node (ref "IC24") (pin "13") (pinfunction "A2_13") (pintype "input"))
      (node (ref "IC28") (pin "7") (pinfunction "A6_7") (pintype "bidirectional"))
      (node (ref "IC32") (pin "15") (pinfunction "O2_15") (pintype "tri_state"))
      (node (ref "IC4") (pin "59") (pinfunction "D10_59") (pintype "bidirectional"))
      (node (ref "IC7") (pin "35") (pinfunction "D2_35") (pintype "bidirectional"))
      (node (ref "IC9") (pin "14") (pinfunction "D10_14") (pintype "bidirectional"))
      (node (ref "ISA1") (pin "A7") (pinfunction "P_A7") (pintype "passive"))
      (node (ref "RN3") (pin "7") (pinfunction "7_7") (pintype "passive"))
    )
    (net (code "74") (name "D10'") (class "Default")
      (node (ref "IC28") (pin "13") (pinfunction "B6_13") (pintype "bidirectional"))
      (node (ref "JP4") (pin "8") (pinfunction "8_8") (pintype "passive"))
    )
    (net (code "75") (name "D11") (class "Default")
      (node (ref "IC1") (pin "19") (pinfunction "D3_19") (pintype "bidirectional"))
      (node (ref "IC2") (pin "19") (pinfunction "D3_19") (pintype "bidirectional"))
      (node (ref "IC22") (pin "6") (pinfunction "3Q_6") (pintype "tri_state"))
      (node (ref "IC24") (pin "6") (pinfunction "A3_6") (pintype "input"))
      (node (ref "IC28") (pin "9") (pinfunction "A8_9") (pintype "bidirectional"))
      (node (ref "IC32") (pin "17") (pinfunction "O3_17") (pintype "tri_state"))
      (node (ref "IC4") (pin "58") (pinfunction "D11_58") (pintype "bidirectional"))
      (node (ref "IC7") (pin "34") (pinfunction "D3_34") (pintype "bidirectional"))
      (node (ref "IC9") (pin "15") (pinfunction "D11_15") (pintype "bidirectional"))
      (node (ref "ISA1") (pin "A6") (pinfunction "P_A6") (pintype "passive"))
      (node (ref "RN3") (pin "6") (pinfunction "6_6") (pintype "passive"))
    )
    (net (code "76") (name "D11'") (class "Default")
      (node (ref "IC28") (pin "11") (pinfunction "B8_11") (pintype "bidirectional"))
      (node (ref "JP4") (pin "10") (pinfunction "10_10") (pintype "passive"))
    )
    (net (code "77") (name "D12") (class "Default")
      (node (ref "IC1") (pin "18") (pinfunction "D4_18") (pintype "bidirectional"))
      (node (ref "IC2") (pin "18") (pinfunction "D4_18") (pintype "bidirectional"))
      (node (ref "IC22") (pin "16") (pinfunction "7Q_16") (pintype "tri_state"))
      (node (ref "IC24") (pin "15") (pinfunction "A3_15") (pintype "input"))
      (node (ref "IC29") (pin "3") (pinfunction "A2_3") (pintype "bidirectional"))
      (node (ref "IC32") (pin "18") (pinfunction "O4_18") (pintype "tri_state"))
      (node (ref "IC4") (pin "57") (pinfunction "D12_57") (pintype "bidirectional"))
      (node (ref "IC7") (pin "33") (pinfunction "D4_33") (pintype "bidirectional"))
      (node (ref "IC9") (pin "16") (pinfunction "D12_16") (pintype "bidirectional"))
      (node (ref "ISA1") (pin "A5") (pinfunction "P_A5") (pintype "passive"))
      (node (ref "RN3") (pin "5") (pinfunction "5_5") (pintype "passive"))
    )
    (net (code "78") (name "D12'") (class "Default")
      (node (ref "IC29") (pin "17") (pinfunction "B2_17") (pintype "bidirectional"))
      (node (ref "JP4") (pin "12") (pinfunction "12_12") (pintype "passive"))
    )
    (net (code "79") (name "D13") (class "Default")
      (node (ref "IC1") (pin "17") (pinfunction "D5_17") (pintype "bidirectional"))
      (node (ref "IC2") (pin "17") (pinfunction "D5_17") (pintype "bidirectional"))
      (node (ref "IC22") (pin "5") (pinfunction "2Q_5") (pintype "tri_state"))
      (node (ref "IC24") (pin "4") (pinfunction "A2_4") (pintype "input"))
      (node (ref "IC29") (pin "5") (pinfunction "A4_5") (pintype "bidirectional"))
      (node (ref "IC32") (pin "19") (pinfunction "O5_19") (pintype "tri_state"))
      (node (ref "IC4") (pin "56") (pinfunction "D13_56") (pintype "bidirectional"))
      (node (ref "IC7") (pin "32") (pinfunction "D5_32") (pintype "bidirectional"))
      (node (ref "IC9") (pin "17") (pinfunction "D13_17") (pintype "bidirectional"))
      (node (ref "ISA1") (pin "A4") (pinfunction "P_A4") (pintype "passive"))
      (node (ref "RN3") (pin "4") (pinfunction "4_4") (pintype "passive"))
    )
    (net (code "80") (name "D13'") (class "Default")
      (node (ref "IC29") (pin "15") (pinfunction "B4_15") (pintype "bidirectional"))
      (node (ref "JP4") (pin "14") (pinfunction "14_14") (pintype "passive"))
    )
    (net (code "81") (name "D14") (class "Default")
      (node (ref "IC1") (pin "16") (pinfunction "D6_16") (pintype "bidirectional"))
      (node (ref "IC2") (pin "16") (pinfunction "D6_16") (pintype "bidirectional"))
      (node (ref "IC22") (pin "19") (pinfunction "8Q_19") (pintype "tri_state"))
      (node (ref "IC24") (pin "17") (pinfunction "A4_17") (pintype "input"))
      (node (ref "IC29") (pin "7") (pinfunction "A6_7") (pintype "bidirectional"))
      (node (ref "IC32") (pin "20") (pinfunction "O6_20") (pintype "tri_state"))
      (node (ref "IC4") (pin "55") (pinfunction "D14_55") (pintype "bidirectional"))
      (node (ref "IC7") (pin "31") (pinfunction "D6_31") (pintype "bidirectional"))
      (node (ref "IC9") (pin "18") (pinfunction "D14_18") (pintype "bidirectional"))
      (node (ref "ISA1") (pin "A3") (pinfunction "P_A3") (pintype "passive"))
      (node (ref "RN3") (pin "3") (pinfunction "3_3") (pintype "passive"))
    )
    (net (code "82") (name "D14'") (class "Default")
      (node (ref "IC29") (pin "13") (pinfunction "B6_13") (pintype "bidirectional"))
      (node (ref "JP4") (pin "16") (pinfunction "16_16") (pintype "passive"))
    )
    (net (code "83") (name "D15") (class "Default")
      (node (ref "IC1") (pin "15") (pinfunction "D7_15") (pintype "bidirectional"))
      (node (ref "IC2") (pin "15") (pinfunction "D7_15") (pintype "bidirectional"))
      (node (ref "IC22") (pin "2") (pinfunction "1Q_2") (pintype "tri_state"))
      (node (ref "IC24") (pin "2") (pinfunction "A1_2") (pintype "input"))
      (node (ref "IC29") (pin "9") (pinfunction "A8_9") (pintype "bidirectional"))
      (node (ref "IC32") (pin "21") (pinfunction "O7_21") (pintype "tri_state"))
      (node (ref "IC4") (pin "54") (pinfunction "D15_54") (pintype "bidirectional"))
      (node (ref "IC7") (pin "30") (pinfunction "D7_30") (pintype "bidirectional"))
      (node (ref "IC9") (pin "19") (pinfunction "D15_19") (pintype "bidirectional"))
      (node (ref "ISA1") (pin "A2") (pinfunction "P_A2") (pintype "passive"))
      (node (ref "RN3") (pin "2") (pinfunction "2_2") (pintype "passive"))
    )
    (net (code "84") (name "D15'") (class "Default")
      (node (ref "IC29") (pin "11") (pinfunction "B8_11") (pintype "bidirectional"))
      (node (ref "JP4") (pin "18") (pinfunction "18_18") (pintype "passive"))
    )
    (net (code "85") (name "DD0") (class "Default")
      (node (ref "IC10") (pin "5") (pinfunction "DAL0_5") (pintype "bidirectional"))
      (node (ref "IC9") (pin "36") (pinfunction "CD0_36") (pintype "bidirectional"))
      (node (ref "JP6") (pin "1") (pinfunction "1_1") (pintype "passive"))
      (node (ref "RN10") (pin "2") (pinfunction "2_2") (pintype "passive"))
    )
    (net (code "86") (name "DD1") (class "Default")
      (node (ref "IC10") (pin "6") (pinfunction "DAL1_6") (pintype "bidirectional"))
      (node (ref "IC9") (pin "35") (pinfunction "CD1_35") (pintype "bidirectional"))
      (node (ref "JP6") (pin "2") (pinfunction "2_2") (pintype "passive"))
      (node (ref "RN10") (pin "3") (pinfunction "3_3") (pintype "passive"))
    )
    (net (code "87") (name "DD2") (class "Default")
      (node (ref "IC10") (pin "7") (pinfunction "DAL2_7") (pintype "bidirectional"))
      (node (ref "IC9") (pin "34") (pinfunction "CD2_34") (pintype "bidirectional"))
      (node (ref "JP6") (pin "3") (pinfunction "3_3") (pintype "passive"))
      (node (ref "RN10") (pin "4") (pinfunction "4_4") (pintype "passive"))
    )
    (net (code "88") (name "DD3") (class "Default")
      (node (ref "IC10") (pin "8") (pinfunction "DAL3_8") (pintype "bidirectional"))
      (node (ref "IC9") (pin "33") (pinfunction "CD3_33") (pintype "bidirectional"))
      (node (ref "JP6") (pin "4") (pinfunction "4_4") (pintype "passive"))
      (node (ref "RN10") (pin "5") (pinfunction "5_5") (pintype "passive"))
    )
    (net (code "89") (name "DD4") (class "Default")
      (node (ref "IC10") (pin "9") (pinfunction "DAL4_9") (pintype "bidirectional"))
      (node (ref "IC9") (pin "32") (pinfunction "CD4_32") (pintype "bidirectional"))
      (node (ref "JP6") (pin "5") (pinfunction "5_5") (pintype "passive"))
      (node (ref "RN10") (pin "6") (pinfunction "6_6") (pintype "passive"))
    )
    (net (code "90") (name "DD5") (class "Default")
      (node (ref "IC10") (pin "10") (pinfunction "DAL5_10") (pintype "bidirectional"))
      (node (ref "IC9") (pin "31") (pinfunction "CD5_31") (pintype "bidirectional"))
      (node (ref "JP6") (pin "6") (pinfunction "6_6") (pintype "passive"))
      (node (ref "RN10") (pin "7") (pinfunction "7_7") (pintype "passive"))
    )
    (net (code "91") (name "DD6") (class "Default")
      (node (ref "IC10") (pin "11") (pinfunction "DAL6_11") (pintype "bidirectional"))
      (node (ref "IC9") (pin "30") (pinfunction "CD6_30") (pintype "bidirectional"))
      (node (ref "JP6") (pin "7") (pinfunction "7_7") (pintype "passive"))
      (node (ref "RN10") (pin "8") (pinfunction "8_8") (pintype "passive"))
    )
    (net (code "92") (name "DD7") (class "Default")
      (node (ref "IC10") (pin "12") (pinfunction "DAL7_12") (pintype "bidirectional"))
      (node (ref "IC9") (pin "29") (pinfunction "CD7_29") (pintype "bidirectional"))
      (node (ref "JP6") (pin "8") (pinfunction "8_8") (pintype "passive"))
      (node (ref "RN10") (pin "9") (pinfunction "9_9") (pintype "passive"))
    )
    (net (code "93") (name "DE") (class "Default")
      (node (ref "IC3") (pin "20") (pinfunction "TBI_20") (pintype "input"))
      (node (ref "IC5") (pin "39") (pinfunction "DE_39") (pintype "bidirectional"))
      (node (ref "IC6") (pin "52") (pinfunction "DE_52") (pintype "output"))
      (node (ref "IC8") (pin "37") (pinfunction "DE_37") (pintype "output"))
    )
    (net (code "94") (name "DEV") (class "Default")
      (node (ref "IC5") (pin "25") (pinfunction "~{DEV}_25") (pintype "bidirectional"))
      (node (ref "IC6") (pin "31") (pinfunction "~{DEV}_31") (pintype "input"))
    )
    (net (code "95") (name "DIR") (class "Default")
      (node (ref "IC11") (pin "18") (pinfunction "O3_18") (pintype "bidirectional"))
      (node (ref "IC28") (pin "1") (pinfunction "DIR_1") (pintype "input"))
      (node (ref "IC29") (pin "1") (pinfunction "DIR_1") (pintype "input"))
      (node (ref "JP4") (pin "25") (pinfunction "25_25") (pintype "passive"))
    )
    (net (code "96") (name "DMA") (class "Default")
      (node (ref "IC5") (pin "24") (pinfunction "~{DMA}_24") (pintype "bidirectional"))
      (node (ref "IC6") (pin "24") (pinfunction "~{DMA}_24") (pintype "input"))
    )
    (net (code "97") (name "DQ0") (class "Default")
      (node (ref "IC23") (pin "13") (pinfunction "5D_13") (pintype "input"))
      (node (ref "IC25") (pin "9") (pinfunction "Y1_9") (pintype "tri_state"))
      (node (ref "IC8") (pin "3") (pinfunction "D0_3") (pintype "bidirectional"))
      (node (ref "JP9") (pin "2") (pinfunction "2_2") (pintype "passive"))
    )
    (net (code "98") (name "DQ1") (class "Default")
      (node (ref "IC23") (pin "14") (pinfunction "6D_14") (pintype "input"))
      (node (ref "IC25") (pin "7") (pinfunction "Y2_7") (pintype "tri_state"))
      (node (ref "IC8") (pin "4") (pinfunction "D1_4") (pintype "bidirectional"))
      (node (ref "JP9") (pin "4") (pinfunction "4_4") (pintype "passive"))
    )
    (net (code "99") (name "DQ2") (class "Default")
      (node (ref "IC23") (pin "17") (pinfunction "7D_17") (pintype "input"))
      (node (ref "IC25") (pin "5") (pinfunction "Y3_5") (pintype "tri_state"))
      (node (ref "IC8") (pin "5") (pinfunction "D2_5") (pintype "bidirectional"))
      (node (ref "JP9") (pin "6") (pinfunction "6_6") (pintype "passive"))
    )
    (net (code "100") (name "DQ3") (class "Default")
      (node (ref "IC23") (pin "18") (pinfunction "8D_18") (pintype "input"))
      (node (ref "IC25") (pin "3") (pinfunction "Y4_3") (pintype "tri_state"))
      (node (ref "IC8") (pin "6") (pinfunction "D3_6") (pintype "bidirectional"))
      (node (ref "JP9") (pin "8") (pinfunction "8_8") (pintype "passive"))
    )
    (net (code "101") (name "DQ4") (class "Default")
      (node (ref "IC23") (pin "3") (pinfunction "1D_3") (pintype "input"))
      (node (ref "IC25") (pin "18") (pinfunction "Y1_18") (pintype "tri_state"))
      (node (ref "IC8") (pin "7") (pinfunction "D4_7") (pintype "bidirectional"))
      (node (ref "JP9") (pin "10") (pinfunction "10_10") (pintype "passive"))
    )
    (net (code "102") (name "DQ5") (class "Default")
      (node (ref "IC23") (pin "4") (pinfunction "2D_4") (pintype "input"))
      (node (ref "IC25") (pin "16") (pinfunction "Y2_16") (pintype "tri_state"))
      (node (ref "IC8") (pin "8") (pinfunction "D5_8") (pintype "bidirectional"))
      (node (ref "JP9") (pin "12") (pinfunction "12_12") (pintype "passive"))
    )
    (net (code "103") (name "DQ6") (class "Default")
      (node (ref "IC23") (pin "7") (pinfunction "3D_7") (pintype "input"))
      (node (ref "IC25") (pin "14") (pinfunction "Y3_14") (pintype "tri_state"))
      (node (ref "IC8") (pin "9") (pinfunction "D6_9") (pintype "bidirectional"))
      (node (ref "JP9") (pin "14") (pinfunction "14_14") (pintype "passive"))
    )
    (net (code "104") (name "DQ7") (class "Default")
      (node (ref "IC23") (pin "8") (pinfunction "4D_8") (pintype "input"))
      (node (ref "IC25") (pin "12") (pinfunction "Y4_12") (pintype "tri_state"))
      (node (ref "IC8") (pin "10") (pinfunction "D7_10") (pintype "bidirectional"))
      (node (ref "JP9") (pin "16") (pinfunction "16_16") (pintype "passive"))
    )
    (net (code "105") (name "DQ8") (class "Default")
      (node (ref "IC22") (pin "13") (pinfunction "5D_13") (pintype "input"))
      (node (ref "IC24") (pin "9") (pinfunction "Y1_9") (pintype "tri_state"))
      (node (ref "IC8") (pin "12") (pinfunction "D8_12") (pintype "bidirectional"))
      (node (ref "JP9") (pin "15") (pinfunction "15_15") (pintype "passive"))
    )
    (net (code "106") (name "DQ9") (class "Default")
      (node (ref "IC22") (pin "8") (pinfunction "4D_8") (pintype "input"))
      (node (ref "IC24") (pin "12") (pinfunction "Y4_12") (pintype "tri_state"))
      (node (ref "IC8") (pin "13") (pinfunction "D9_13") (pintype "bidirectional"))
      (node (ref "JP9") (pin "13") (pinfunction "13_13") (pintype "passive"))
    )
    (net (code "107") (name "DQ10") (class "Default")
      (node (ref "IC22") (pin "14") (pinfunction "6D_14") (pintype "input"))
      (node (ref "IC24") (pin "7") (pinfunction "Y2_7") (pintype "tri_state"))
      (node (ref "IC8") (pin "14") (pinfunction "D10_14") (pintype "bidirectional"))
      (node (ref "JP9") (pin "11") (pinfunction "11_11") (pintype "passive"))
    )
    (net (code "108") (name "DQ11") (class "Default")
      (node (ref "IC22") (pin "7") (pinfunction "3D_7") (pintype "input"))
      (node (ref "IC24") (pin "14") (pinfunction "Y3_14") (pintype "tri_state"))
      (node (ref "IC8") (pin "15") (pinfunction "D11_15") (pintype "bidirectional"))
      (node (ref "JP9") (pin "9") (pinfunction "9_9") (pintype "passive"))
    )
    (net (code "109") (name "DQ12") (class "Default")
      (node (ref "IC22") (pin "17") (pinfunction "7D_17") (pintype "input"))
      (node (ref "IC24") (pin "5") (pinfunction "Y3_5") (pintype "tri_state"))
      (node (ref "IC8") (pin "16") (pinfunction "D12_16") (pintype "bidirectional"))
      (node (ref "JP9") (pin "7") (pinfunction "7_7") (pintype "passive"))
    )
    (net (code "110") (name "DQ13") (class "Default")
      (node (ref "IC22") (pin "4") (pinfunction "2D_4") (pintype "input"))
      (node (ref "IC24") (pin "16") (pinfunction "Y2_16") (pintype "tri_state"))
      (node (ref "IC8") (pin "17") (pinfunction "D13_17") (pintype "bidirectional"))
      (node (ref "JP9") (pin "5") (pinfunction "5_5") (pintype "passive"))
    )
    (net (code "111") (name "DQ14") (class "Default")
      (node (ref "IC22") (pin "18") (pinfunction "8D_18") (pintype "input"))
      (node (ref "IC24") (pin "3") (pinfunction "Y4_3") (pintype "tri_state"))
      (node (ref "IC8") (pin "18") (pinfunction "D14_18") (pintype "bidirectional"))
      (node (ref "JP9") (pin "3") (pinfunction "3_3") (pintype "passive"))
    )
    (net (code "112") (name "DQ15") (class "Default")
      (node (ref "IC22") (pin "3") (pinfunction "1D_3") (pintype "input"))
      (node (ref "IC24") (pin "18") (pinfunction "Y1_18") (pintype "tri_state"))
      (node (ref "IC8") (pin "19") (pinfunction "D15_19") (pintype "bidirectional"))
      (node (ref "JP9") (pin "1") (pinfunction "1_1") (pintype "passive"))
    )
    (net (code "113") (name "DTACK") (class "Default")
      (node (ref "IC3") (pin "46") (pinfunction "DTACK_46") (pintype "output"))
      (node (ref "IC30") (pin "11") (pinfunction "O_11") (pintype "open_collector"))
      (node (ref "IC30") (pin "8") (pinfunction "O_8") (pintype "open_collector"))
      (node (ref "IC4") (pin "10") (pinfunction "DTACK_10") (pintype "input"))
      (node (ref "IC5") (pin "31") (pinfunction "~{DTACK}_31") (pintype "input"))
      (node (ref "IC6") (pin "53") (pinfunction "~{DTACK}_53") (pintype "input"))
      (node (ref "RN5") (pin "5") (pinfunction "5_5") (pintype "passive"))
      (node (ref "T7") (pin "1") (pinfunction "C_1") (pintype "passive"))
    )
    (net (code "114") (name "E") (class "Default")
      (node (ref "IC1") (pin "14") (pinfunction "E_14") (pintype "input"))
      (node (ref "IC2") (pin "14") (pinfunction "E_14") (pintype "input"))
      (node (ref "IC4") (pin "20") (pinfunction "E_20") (pintype "output"))
    )
    (net (code "115") (name "EIFRX") (class "Default")
      (node (ref "IC1") (pin "2") (pinfunction "RXDATA_2") (pintype "input"))
      (node (ref "IC13") (pin "17") (pinfunction "RC6_17") (pintype "bidirectional"))
    )
    (net (code "116") (name "EIFTX") (class "Default")
      (node (ref "IC1") (pin "6") (pinfunction "TXDATA_6") (pintype "output"))
      (node (ref "IC13") (pin "18") (pinfunction "RC7_18") (pintype "bidirectional"))
    )
    (net (code "117") (name "FC0") (class "Default")
      (node (ref "IC4") (pin "28") (pinfunction "FC0_28") (pintype "output"))
      (node (ref "IC5") (pin "15") (pinfunction "FC0_15") (pintype "output"))
      (node (ref "RN8") (pin "5") (pinfunction "5_5") (pintype "passive"))
    )
    (net (code "118") (name "FC1") (class "Default")
      (node (ref "IC4") (pin "27") (pinfunction "FC1_27") (pintype "output"))
      (node (ref "IC5") (pin "14") (pinfunction "FC1_14") (pintype "output"))
      (node (ref "RN8") (pin "4") (pinfunction "4_4") (pintype "passive"))
    )
    (net (code "119") (name "FC2") (class "Default")
      (node (ref "IC4") (pin "26") (pinfunction "FC2_26") (pintype "output"))
      (node (ref "IC5") (pin "13") (pinfunction "FC2_13") (pintype "output"))
      (node (ref "RN8") (pin "3") (pinfunction "3_3") (pintype "passive"))
    )
    (net (code "120") (name "FCS") (class "Default")
      (node (ref "IC5") (pin "26") (pinfunction "~{FCS}_26") (pintype "output"))
      (node (ref "IC9") (pin "3") (pinfunction "~{FCS}_3") (pintype "output"))
    )
    (net (code "121") (name "G") (class "Default")
      (node (ref "R55") (pin "1") (pinfunction "1_1") (pintype "passive"))
      (node (ref "U$6") (pin "PIN6") (pinfunction "PIN6_PIN6") (pintype "bidirectional"))
    )
    (net (code "122") (name "G2") (class "Default")
      (node (ref "R72") (pin "1") (pinfunction "1_1") (pintype "passive"))
      (node (ref "VGA") (pin "2") (pinfunction "2_2") (pintype "passive"))
    )
    (net (code "123") (name "GG") (class "Default")
      (node (ref "IC11") (pin "15") (pinfunction "O0_15") (pintype "bidirectional"))
      (node (ref "IC28") (pin "19") (pinfunction "G_19") (pintype "input"))
      (node (ref "IC29") (pin "19") (pinfunction "G_19") (pintype "input"))
    )
    (net (code "124") (name "GND") (class "Default")
      (node (ref "C1") (pin "2") (pinfunction "2_2") (pintype "passive"))
      (node (ref "C10") (pin "2") (pinfunction "2_2") (pintype "passive"))
      (node (ref "C11") (pin "2") (pinfunction "2_2") (pintype "passive"))
      (node (ref "C12") (pin "2") (pinfunction "2_2") (pintype "passive"))
      (node (ref "C13") (pin "2") (pinfunction "2_2") (pintype "passive"))
      (node (ref "C14") (pin "2") (pinfunction "2_2") (pintype "passive"))
      (node (ref "C15") (pin "2") (pinfunction "2_2") (pintype "passive"))
      (node (ref "C16") (pin "2") (pinfunction "2_2") (pintype "passive"))
      (node (ref "C17") (pin "2") (pinfunction "2_2") (pintype "passive"))
      (node (ref "C18") (pin "2") (pinfunction "2_2") (pintype "passive"))
      (node (ref "C19") (pin "2") (pinfunction "2_2") (pintype "passive"))
      (node (ref "C2") (pin "2") (pinfunction "2_2") (pintype "passive"))
      (node (ref "C20") (pin "2") (pinfunction "2_2") (pintype "passive"))
      (node (ref "C21") (pin "2") (pinfunction "2_2") (pintype "passive"))
      (node (ref "C22") (pin "2") (pinfunction "2_2") (pintype "passive"))
      (node (ref "C23") (pin "2") (pinfunction "2_2") (pintype "passive"))
      (node (ref "C24") (pin "2") (pinfunction "2_2") (pintype "passive"))
      (node (ref "C25") (pin "2") (pinfunction "2_2") (pintype "passive"))
      (node (ref "C26") (pin "2") (pinfunction "2_2") (pintype "passive"))
      (node (ref "C27") (pin "2") (pinfunction "2_2") (pintype "passive"))
      (node (ref "C28") (pin "2") (pinfunction "2_2") (pintype "passive"))
      (node (ref "C29") (pin "2") (pinfunction "2_2") (pintype "passive"))
      (node (ref "C3") (pin "1") (pinfunction "1_1") (pintype "passive"))
      (node (ref "C30") (pin "2") (pinfunction "2_2") (pintype "passive"))
      (node (ref "C31") (pin "2") (pinfunction "2_2") (pintype "passive"))
      (node (ref "C32") (pin "2") (pinfunction "2_2") (pintype "passive"))
      (node (ref "C33") (pin "2") (pinfunction "2_2") (pintype "passive"))
      (node (ref "C34") (pin "-") (pinfunction "-_-") (pintype "passive"))
      (node (ref "C35") (pin "2") (pinfunction "2_2") (pintype "passive"))
      (node (ref "C39") (pin "1") (pinfunction "1_1") (pintype "passive"))
      (node (ref "C4") (pin "1") (pinfunction "1_1") (pintype "passive"))
      (node (ref "C40") (pin "1") (pinfunction "1_1") (pintype "passive"))
      (node (ref "C41") (pin "1") (pinfunction "1_1") (pintype "passive"))
      (node (ref "C42") (pin "2") (pinfunction "2_2") (pintype "passive"))
      (node (ref "C43") (pin "2") (pinfunction "2_2") (pintype "passive"))
      (node (ref "C44") (pin "2") (pinfunction "2_2") (pintype "passive"))
      (node (ref "C45") (pin "1") (pinfunction "1_1") (pintype "passive"))
      (node (ref "C46") (pin "1") (pinfunction "1_1") (pintype "passive"))
      (node (ref "C47") (pin "1") (pinfunction "1_1") (pintype "passive"))
      (node (ref "C48") (pin "1") (pinfunction "1_1") (pintype "passive"))
      (node (ref "C49") (pin "1") (pinfunction "1_1") (pintype "passive"))
      (node (ref "C5") (pin "2") (pinfunction "2_2") (pintype "passive"))
      (node (ref "C51") (pin "+") (pinfunction "+_+") (pintype "passive"))
      (node (ref "C52") (pin "-") (pinfunction "-_-") (pintype "passive"))
      (node (ref "C53") (pin "2") (pinfunction "2_2") (pintype "passive"))
      (node (ref "C54") (pin "2") (pinfunction "2_2") (pintype "passive"))
      (node (ref "C55") (pin "2") (pinfunction "2_2") (pintype "passive"))
      (node (ref "C56") (pin "2") (pinfunction "2_2") (pintype "passive"))
      (node (ref "C57") (pin "2") (pinfunction "2_2") (pintype "passive"))
      (node (ref "C58") (pin "-") (pinfunction "-_-") (pintype "passive"))
      (node (ref "C59") (pin "2") (pinfunction "2_2") (pintype "passive"))
      (node (ref "C6") (pin "2") (pinfunction "2_2") (pintype "passive"))
      (node (ref "C60") (pin "2") (pinfunction "2_2") (pintype "passive"))
      (node (ref "C61") (pin "-") (pinfunction "-_-") (pintype "passive"))
      (node (ref "C62") (pin "-") (pinfunction "-_-") (pintype "passive"))
      (node (ref "C63") (pin "-") (pinfunction "-_-") (pintype "passive"))
      (node (ref "C64") (pin "-") (pinfunction "-_-") (pintype "passive"))
      (node (ref "C65") (pin "2") (pinfunction "2_2") (pintype "passive"))
      (node (ref "C66") (pin "2") (pinfunction "2_2") (pintype "passive"))
      (node (ref "C67") (pin "-") (pinfunction "-_-") (pintype "passive"))
      (node (ref "C68") (pin "-") (pinfunction "-_-") (pintype "passive"))
      (node (ref "C69") (pin "-") (pinfunction "-_-") (pintype "passive"))
      (node (ref "C70") (pin "2") (pinfunction "2_2") (pintype "passive"))
      (node (ref "C71") (pin "2") (pinfunction "2_2") (pintype "passive"))
      (node (ref "C72") (pin "2") (pinfunction "2_2") (pintype "passive"))
      (node (ref "C8") (pin "2") (pinfunction "2_2") (pintype "passive"))
      (node (ref "C9") (pin "2") (pinfunction "2_2") (pintype "passive"))
      (node (ref "CN1") (pin "GND") (pinfunction "GND_GND") (pintype "power_in"))
      (node (ref "D9") (pin "C") (pinfunction "C_C") (pintype "passive"))
      (node (ref "IC1") (pin "1") (pinfunction "VSS_1") (pintype "power_in"))
      (node (ref "IC1") (pin "23") (pinfunction "DCD_23") (pintype "input"))
      (node (ref "IC1") (pin "24") (pinfunction "CTS_24") (pintype "input"))
      (node (ref "IC10") (pin "14") (pinfunction "GND_14") (pintype "power_in"))
      (node (ref "IC10") (pin "26") (pinfunction "/DD_26") (pintype "bidirectional"))
      (node (ref "IC12") (pin "13") (pinfunction "OE/I10_13") (pintype "input"))
      (node (ref "IC13") (pin "19") (pinfunction "VSS_19") (pintype "power_in"))
      (node (ref "IC13") (pin "8") (pinfunction "VSS_8") (pintype "power_in"))
      (node (ref "IC17") (pin "7") (pinfunction "GND_7") (pintype "power_in"))
      (node (ref "IC2") (pin "1") (pinfunction "VSS_1") (pintype "power_in"))
      (node (ref "IC2") (pin "23") (pinfunction "DCD_23") (pintype "input"))
      (node (ref "IC2") (pin "24") (pinfunction "CTS_24") (pintype "input"))
      (node (ref "IC2") (pin "9") (pinfunction "CS2_9") (pintype "input"))
      (node (ref "IC20") (pin "11") (pinfunction "I_11") (pintype "input"))
      (node (ref "IC20") (pin "3") (pinfunction "I_3") (pintype "input"))
      (node (ref "IC20") (pin "5") (pinfunction "I_5") (pintype "input"))
      (node (ref "IC20") (pin "9") (pinfunction "I_9") (pintype "input"))
      (node (ref "IC26") (pin "7") (pinfunction "GND_7") (pintype "power_in"))
      (node (ref "IC27") (pin "2") (pinfunction "INH_2") (pintype "bidirectional"))
      (node (ref "IC27") (pin "4") (pinfunction "SUBST_4") (pintype "input"))
      (node (ref "IC27") (pin "5") (pinfunction "GND_5") (pintype "input"))
      (node (ref "IC27") (pin "8") (pinfunction "EMIT_8") (pintype "output"))
      (node (ref "IC3") (pin "34") (pinfunction "IEI_34") (pintype "input"))
      (node (ref "IC31") (pin "16") (pinfunction "GND_16") (pintype "power_in"))
      (node (ref "IC31") (pin "24") (pinfunction "~{OE}_24") (pintype "input"))
      (node (ref "IC32") (pin "16") (pinfunction "GND_16") (pintype "power_in"))
      (node (ref "IC32") (pin "24") (pinfunction "~{OE}_24") (pintype "input"))
      (node (ref "IC5") (pin "35") (pinfunction "GND_35") (pintype "power_in"))
      (node (ref "IC5") (pin "52") (pinfunction "TEST_52") (pintype "power_in"))
      (node (ref "IC6") (pin "27") (pinfunction "GNDA_27") (pintype "power_in"))
      (node (ref "IC6") (pin "61") (pinfunction "GNDB_61") (pintype "power_in"))
      (node (ref "IC7") (pin "1") (pinfunction "GND_1") (pintype "power_in"))
      (node (ref "IC7") (pin "24") (pinfunction "~{A9}_24") (pintype "input"))
      (node (ref "IC8") (pin "20") (pinfunction "GND_20") (pintype "power_in"))
      (node (ref "IC9") (pin "20") (pinfunction "GND_20") (pintype "power_in"))
      (node (ref "IC9") (pin "28") (pinfunction "GND1_28") (pintype "power_in"))
      (node (ref "ISA1") (pin "A11") (pinfunction "P_A11") (pintype "passive"))
      (node (ref "ISA1") (pin "B1") (pinfunction "P_B1") (pintype "passive"))
      (node (ref "ISA1") (pin "B10") (pinfunction "P_B10") (pintype "passive"))
      (node (ref "ISA1") (pin "B31") (pinfunction "P_B31") (pintype "passive"))
      (node (ref "ISA1") (pin "C2") (pinfunction "P_C2") (pintype "passive"))
      (node (ref "ISA1") (pin "C3") (pinfunction "P_C3") (pintype "passive"))
      (node (ref "ISA1") (pin "C4") (pinfunction "P_C4") (pintype "passive"))
      (node (ref "ISA1") (pin "C5") (pinfunction "P_C5") (pintype "passive"))
      (node (ref "ISA1") (pin "D18") (pinfunction "P_D18") (pintype "passive"))
      (node (ref "J1") (pin "SLEEVE") (pinfunction "SLEEVE_SLEEVE") (pintype "bidirectional"))
      (node (ref "J3") (pin "8") (pinfunction "8_8") (pintype "passive"))
      (node (ref "J3") (pin "G1") (pinfunction "10_G1") (pintype "passive"))
      (node (ref "J3") (pin "G2") (pinfunction "11_G2") (pintype "passive"))
      (node (ref "J4") (pin "2") (pinfunction "2_2") (pintype "power_in"))
      (node (ref "J4") (pin "SHIELD1") (pinfunction "SHIELD_SHIELD1") (pintype "power_in"))
      (node (ref "J4") (pin "SHIELD2") (pinfunction "SHIELD_SHIELD2") (pintype "power_in"))
      (node (ref "J4") (pin "SHIELD3") (pinfunction "SHIELD_SHIELD3") (pintype "power_in"))
      (node (ref "J5") (pin "SHIELD1") (pinfunction "SHIELD_SHIELD1") (pintype "power_in"))
      (node (ref "J5") (pin "SHIELD2") (pinfunction "SHIELD_SHIELD2") (pintype "power_in"))
      (node (ref "J5") (pin "SHIELD3") (pinfunction "SHIELD_SHIELD3") (pintype "power_in"))
      (node (ref "J6") (pin "8") (pinfunction "8_8") (pintype "passive"))
      (node (ref "J6") (pin "G1") (pinfunction "10_G1") (pintype "passive"))
      (node (ref "J6") (pin "G2") (pinfunction "11_G2") (pintype "passive"))
      (node (ref "JP1") (pin "1") (pinfunction "1_1") (pintype "passive"))
      (node (ref "JP12") (pin "3") (pinfunction "3_3") (pintype "passive"))
      (node (ref "JP13") (pin "1") (pinfunction "1_1") (pintype "passive"))
      (node (ref "JP3") (pin "3") (pinfunction "3_3") (pintype "passive"))
      (node (ref "JP4") (pin "19") (pinfunction "19_19") (pintype "passive"))
      (node (ref "JP4") (pin "2") (pinfunction "2_2") (pintype "passive"))
      (node (ref "JP4") (pin "22") (pinfunction "22_22") (pintype "passive"))
      (node (ref "JP4") (pin "24") (pinfunction "24_24") (pintype "passive"))
      (node (ref "JP4") (pin "26") (pinfunction "26_26") (pintype "passive"))
      (node (ref "JP4") (pin "28") (pinfunction "28_28") (pintype "passive"))
      (node (ref "JP4") (pin "30") (pinfunction "30_30") (pintype "passive"))
      (node (ref "JP4") (pin "40") (pinfunction "40_40") (pintype "passive"))
      (node (ref "JP5") (pin "1") (pinfunction "1_1") (pintype "passive"))
      (node (ref "JP5") (pin "11") (pinfunction "11_11") (pintype "passive"))
      (node (ref "JP5") (pin "13") (pinfunction "13_13") (pintype "passive"))
      (node (ref "JP5") (pin "15") (pinfunction "15_15") (pintype "passive"))
      (node (ref "JP5") (pin "17") (pinfunction "17_17") (pintype "passive"))
      (node (ref "JP5") (pin "19") (pinfunction "19_19") (pintype "passive"))
      (node (ref "JP5") (pin "21") (pinfunction "21_21") (pintype "passive"))
      (node (ref "JP5") (pin "23") (pinfunction "23_23") (pintype "passive"))
      (node (ref "JP5") (pin "25") (pinfunction "25_25") (pintype "passive"))
      (node (ref "JP5") (pin "27") (pinfunction "27_27") (pintype "passive"))
      (node (ref "JP5") (pin "29") (pinfunction "29_29") (pintype "passive"))
      (node (ref "JP5") (pin "3") (pinfunction "3_3") (pintype "passive"))
      (node (ref "JP5") (pin "31") (pinfunction "31_31") (pintype "passive"))
      (node (ref "JP5") (pin "33") (pinfunction "33_33") (pintype "passive"))
      (node (ref "JP5") (pin "5") (pinfunction "5_5") (pintype "passive"))
      (node (ref "JP5") (pin "7") (pinfunction "7_7") (pintype "passive"))
      (node (ref "JP5") (pin "9") (pinfunction "9_9") (pintype "passive"))
      (node (ref "JP6") (pin "11") (pinfunction "11_11") (pintype "passive"))
      (node (ref "JP6") (pin "13") (pinfunction "13_13") (pintype "passive"))
      (node (ref "JP6") (pin "15") (pinfunction "15_15") (pintype "passive"))
      (node (ref "JP6") (pin "17") (pinfunction "17_17") (pintype "passive"))
      (node (ref "JP7") (pin "1") (pinfunction "1_1") (pintype "passive"))
      (node (ref "JP7") (pin "7") (pinfunction "7_7") (pintype "passive"))
      (node (ref "JP8") (pin "18") (pinfunction "18_18") (pintype "passive"))
      (node (ref "JP8") (pin "19") (pinfunction "19_19") (pintype "passive"))
      (node (ref "JP8") (pin "20") (pinfunction "20_20") (pintype "passive"))
      (node (ref "JP8") (pin "21") (pinfunction "21_21") (pintype "passive"))
      (node (ref "JP8") (pin "22") (pinfunction "22_22") (pintype "passive"))
      (node (ref "JP8") (pin "23") (pinfunction "23_23") (pintype "passive"))
      (node (ref "JP8") (pin "24") (pinfunction "24_24") (pintype "passive"))
      (node (ref "JP8") (pin "25") (pinfunction "25_25") (pintype "passive"))
      (node (ref "JP9") (pin "18") (pinfunction "18_18") (pintype "passive"))
      (node (ref "JP9") (pin "20") (pinfunction "20_20") (pintype "passive"))
      (node (ref "OK1") (pin "5") (pinfunction "GND_5") (pintype "power_in"))
      (node (ref "Q3") (pin "1") (pinfunction "C_1") (pintype "passive"))
      (node (ref "R22") (pin "2") (pinfunction "2_2") (pintype "passive"))
      (node (ref "R39") (pin "1") (pinfunction "1_1") (pintype "passive"))
      (node (ref "R4") (pin "1") (pinfunction "1_1") (pintype "passive"))
      (node (ref "R40") (pin "1") (pinfunction "1_1") (pintype "passive"))
      (node (ref "R43") (pin "1") (pinfunction "1_1") (pintype "passive"))
      (node (ref "R47") (pin "1") (pinfunction "1_1") (pintype "passive"))
      (node (ref "R53") (pin "1") (pinfunction "1_1") (pintype "passive"))
      (node (ref "R54") (pin "1") (pinfunction "1_1") (pintype "passive"))
      (node (ref "R57") (pin "1") (pinfunction "1_1") (pintype "passive"))
      (node (ref "R58") (pin "1") (pinfunction "1_1") (pintype "passive"))
      (node (ref "R61") (pin "1") (pinfunction "1_1") (pintype "passive"))
      (node (ref "R62") (pin "1") (pinfunction "1_1") (pintype "passive"))
      (node (ref "R69") (pin "1") (pinfunction "1_1") (pintype "passive"))
      (node (ref "R75") (pin "2") (pinfunction "2_2") (pintype "passive"))
      (node (ref "R77") (pin "1") (pinfunction "1_1") (pintype "passive"))
      (node (ref "T7") (pin "3") (pinfunction "E_3") (pintype "passive"))
      (node (ref "U$6") (pin "M1") (pinfunction "P1_M1") (pintype "bidirectional"))
      (node (ref "U$6") (pin "M2") (pinfunction "P2_M2") (pintype "bidirectional"))
      (node (ref "U$6") (pin "PIN13") (pinfunction "PIN13_PIN13") (pintype "bidirectional"))
      (node (ref "VGA") (pin "10") (pinfunction "10_10") (pintype "passive"))
      (node (ref "VGA") (pin "11") (pinfunction "11_11") (pintype "passive"))
      (node (ref "VGA") (pin "4") (pinfunction "4_4") (pintype "passive"))
      (node (ref "VGA") (pin "5") (pinfunction "5_5") (pintype "passive"))
      (node (ref "VGA") (pin "6") (pinfunction "6_6") (pintype "passive"))
      (node (ref "VGA") (pin "7") (pinfunction "7_7") (pintype "passive"))
      (node (ref "VGA") (pin "8") (pinfunction "8_8") (pintype "passive"))
      (node (ref "X1") (pin "7") (pinfunction "GND_7") (pintype "power_in"))
      (node (ref "X3") (pin "1-3") (pinfunction "3_1-3") (pintype "passive"))
      (node (ref "X3") (pin "2-3") (pinfunction "3_2-3") (pintype "passive"))
      (node (ref "X3") (pin "G1") (pinfunction "P$1_G1") (pintype "bidirectional"))
      (node (ref "X3") (pin "G2") (pinfunction "P$2_G2") (pintype "bidirectional"))
      (node (ref "X3") (pin "G3") (pinfunction "P$1_G3") (pintype "bidirectional"))
      (node (ref "X3") (pin "G4") (pinfunction "P$2_G4") (pintype "bidirectional"))
      (node (ref "X4") (pin "13") (pinfunction "S_13") (pintype "passive"))
      (node (ref "X4") (pin "15") (pinfunction "S_15") (pintype "passive"))
      (node (ref "X4") (pin "16") (pinfunction "S_16") (pintype "passive"))
      (node (ref "X4") (pin "17") (pinfunction "S_17") (pintype "passive"))
      (node (ref "X4") (pin "3") (pinfunction "S_3") (pintype "passive"))
      (node (ref "X4") (pin "5") (pinfunction "S_5") (pintype "passive"))
      (node (ref "X4") (pin "7") (pinfunction "S_7") (pintype "passive"))
    )
    (net (code "125") (name "GNDBREAK") (class "Default")
      (node (ref "CN1") (pin "GNDBREAK") (pinfunction "GNDBREAK_GNDBREAK") (pintype "power_in"))
    )
    (net (code "126") (name "GPO") (class "Default")
      (node (ref "IC7") (pin "15") (pinfunction "IOA6_15") (pintype "output"))
      (node (ref "U$6") (pin "PIN3") (pinfunction "PIN3_PIN3") (pintype "bidirectional"))
    )
    (net (code "127") (name "HALT") (class "Default")
      (node (ref "IC15") (pin "6") (pinfunction "O_6") (pintype "open_collector"))
      (node (ref "IC15") (pin "8") (pinfunction "O_8") (pintype "open_collector"))
      (node (ref "IC4") (pin "17") (pinfunction "HALT_17") (pintype "bidirectional"))
      (node (ref "RN9") (pin "3") (pinfunction "3_3") (pintype "passive"))
    )
    (net (code "128") (name "HSYNC") (class "Default")
      (node (ref "D11") (pin "C") (pinfunction "C_C") (pintype "passive"))
      (node (ref "IC5") (pin "37") (pinfunction "HSYNC_37") (pintype "output"))
      (node (ref "U$6") (pin "PIN9") (pinfunction "PIN9_PIN9") (pintype "bidirectional"))
      (node (ref "VGA") (pin "13") (pinfunction "13_13") (pintype "passive"))
    )
    (net (code "129") (name "IACK") (class "Default")
      (node (ref "IC3") (pin "45") (pinfunction "IACK_45") (pintype "input"))
      (node (ref "IC5") (pin "50") (pinfunction "~{IACK}_50") (pintype "output"))
    )
    (net (code "130") (name "INTRQ") (class "Default")
      (node (ref "IC30") (pin "1") (pinfunction "I0_1") (pintype "input"))
      (node (ref "IC30") (pin "2") (pinfunction "I1_2") (pintype "input"))
      (node (ref "JP4") (pin "31") (pinfunction "31_31") (pintype "passive"))
      (node (ref "R77") (pin "2") (pinfunction "2_2") (pintype "passive"))
    )
    (net (code "131") (name "IOB0") (class "Default")
      (node (ref "IC7") (pin "13") (pinfunction "IOB0_13") (pintype "output"))
      (node (ref "JP8") (pin "2") (pinfunction "2_2") (pintype "passive"))
    )
    (net (code "132") (name "IOB1") (class "Default")
      (node (ref "IC7") (pin "12") (pinfunction "IOB1_12") (pintype "output"))
      (node (ref "JP8") (pin "3") (pinfunction "3_3") (pintype "passive"))
    )
    (net (code "133") (name "IOB2") (class "Default")
      (node (ref "IC7") (pin "11") (pinfunction "IOB2_11") (pintype "output"))
      (node (ref "JP8") (pin "4") (pinfunction "4_4") (pintype "passive"))
    )
    (net (code "134") (name "IOB3") (class "Default")
      (node (ref "IC7") (pin "10") (pinfunction "IOB3_10") (pintype "output"))
      (node (ref "JP8") (pin "5") (pinfunction "5_5") (pintype "passive"))
    )
    (net (code "135") (name "IOB4") (class "Default")
      (node (ref "IC7") (pin "9") (pinfunction "IOB4_9") (pintype "output"))
      (node (ref "JP8") (pin "6") (pinfunction "6_6") (pintype "passive"))
    )
    (net (code "136") (name "IOB5") (class "Default")
      (node (ref "IC7") (pin "8") (pinfunction "IOB5_8") (pintype "output"))
      (node (ref "JP8") (pin "7") (pinfunction "7_7") (pintype "passive"))
    )
    (net (code "137") (name "IOB6") (class "Default")
      (node (ref "IC7") (pin "7") (pinfunction "IOB6_7") (pintype "output"))
      (node (ref "JP8") (pin "8") (pinfunction "8_8") (pintype "passive"))
    )
    (net (code "138") (name "IOB7") (class "Default")
      (node (ref "IC7") (pin "6") (pinfunction "IOB7_6") (pintype "output"))
      (node (ref "JP8") (pin "9") (pinfunction "9_9") (pintype "passive"))
    )
    (net (code "139") (name "IORDY") (class "Default")
      (node (ref "IC30") (pin "4") (pinfunction "I0_4") (pintype "input"))
      (node (ref "IC30") (pin "5") (pinfunction "I1_5") (pintype "input"))
      (node (ref "JP4") (pin "27") (pinfunction "27_27") (pintype "passive"))
      (node (ref "R78") (pin "1") (pinfunction "1_1") (pintype "passive"))
    )
    (net (code "140") (name "IOWR") (class "Default")
      (node (ref "IC11") (pin "19") (pinfunction "O4_19") (pintype "bidirectional"))
      (node (ref "JP4") (pin "23") (pinfunction "23_23") (pintype "passive"))
    )
    (net (code "141") (name "IPL0") (class "Default")
      (node (ref "IC4") (pin "25") (pinfunction "IPL0_25") (pintype "input"))
      (node (ref "RN9") (pin "9") (pinfunction "9_9") (pintype "passive"))
    )
    (net (code "142") (name "IPL1") (class "Default")
      (node (ref "IC4") (pin "24") (pinfunction "IPL1_24") (pintype "input"))
      (node (ref "IC5") (pin "32") (pinfunction "~{IPL1}_32") (pintype "output"))
      (node (ref "RN9") (pin "8") (pinfunction "8_8") (pintype "passive"))
    )
    (net (code "143") (name "IPL2") (class "Default")
      (node (ref "IC4") (pin "23") (pinfunction "IPL2_23") (pintype "input"))
      (node (ref "IC5") (pin "33") (pinfunction "~{IPL2}_33") (pintype "output"))
      (node (ref "RN9") (pin "7") (pinfunction "7_7") (pintype "passive"))
    )
    (net (code "144") (name "LATCH") (class "Default")
      (node (ref "IC22") (pin "11") (pinfunction "ENC_11") (pintype "input"))
      (node (ref "IC23") (pin "11") (pinfunction "ENC_11") (pintype "input"))
      (node (ref "IC6") (pin "9") (pinfunction "LATCH_9") (pintype "output"))
    )
    (net (code "145") (name "LDS") (class "Default")
      (node (ref "D12") (pin "C") (pinfunction "C_C") (pintype "passive"))
      (node (ref "IC3") (pin "47") (pinfunction "DS_47") (pintype "input"))
      (node (ref "IC4") (pin "8") (pinfunction "LDS_8") (pintype "output"))
      (node (ref "IC5") (pin "46") (pinfunction "~{LDS}_46") (pintype "output"))
      (node (ref "IC6") (pin "17") (pinfunction "~{LDS}_17") (pintype "output"))
      (node (ref "ISA1") (pin "C1") (pinfunction "P_C1") (pintype "passive"))
      (node (ref "RN5") (pin "7") (pinfunction "7_7") (pintype "passive"))
    )
    (net (code "146") (name "LOAD") (class "Default")
      (node (ref "IC6") (pin "29") (pinfunction "~{DCYC}_29") (pintype "output"))
      (node (ref "IC8") (pin "11") (pinfunction "~{LOAD}_11") (pintype "input"))
    )
    (net (code "147") (name "MAD0") (class "Default")
      (node (ref "IC6") (pin "59") (pinfunction "MAD0_59") (pintype "output"))
      (node (ref "JP9") (pin "28") (pinfunction "28_28") (pintype "passive"))
    )
    (net (code "148") (name "MAD1") (class "Default")
      (node (ref "IC6") (pin "58") (pinfunction "MAD1_58") (pintype "output"))
      (node (ref "JP9") (pin "27") (pinfunction "27_27") (pintype "passive"))
    )
    (net (code "149") (name "MAD2") (class "Default")
      (node (ref "IC6") (pin "57") (pinfunction "MAD2_57") (pintype "output"))
      (node (ref "JP9") (pin "30") (pinfunction "30_30") (pintype "passive"))
    )
    (net (code "150") (name "MAD3") (class "Default")
      (node (ref "IC6") (pin "56") (pinfunction "MAD3_56") (pintype "output"))
      (node (ref "JP9") (pin "29") (pinfunction "29_29") (pintype "passive"))
    )
    (net (code "151") (name "MAD4") (class "Default")
      (node (ref "IC6") (pin "55") (pinfunction "MAD4_55") (pintype "output"))
      (node (ref "JP9") (pin "32") (pinfunction "32_32") (pintype "passive"))
    )
    (net (code "152") (name "MAD5") (class "Default")
      (node (ref "IC6") (pin "54") (pinfunction "MAD5_54") (pintype "output"))
      (node (ref "JP9") (pin "31") (pinfunction "31_31") (pintype "passive"))
    )
    (net (code "153") (name "MAD6") (class "Default")
      (node (ref "IC6") (pin "60") (pinfunction "MAD6_60") (pintype "output"))
      (node (ref "JP9") (pin "34") (pinfunction "34_34") (pintype "passive"))
    )
    (net (code "154") (name "MAD7") (class "Default")
      (node (ref "IC6") (pin "62") (pinfunction "MAD7_62") (pintype "output"))
      (node (ref "JP9") (pin "33") (pinfunction "33_33") (pintype "passive"))
    )
    (net (code "155") (name "MAD8") (class "Default")
      (node (ref "IC6") (pin "63") (pinfunction "MAD8_63") (pintype "output"))
      (node (ref "JP9") (pin "36") (pinfunction "36_36") (pintype "passive"))
    )
    (net (code "156") (name "MAD9") (class "Default")
      (node (ref "IC6") (pin "64") (pinfunction "MAD9_64") (pintype "output"))
      (node (ref "JP9") (pin "35") (pinfunction "35_35") (pintype "passive"))
    )
    (net (code "157") (name "MEMRD") (class "Default")
      (node (ref "IC12") (pin "16") (pinfunction "O1_16") (pintype "bidirectional"))
      (node (ref "ISA1") (pin "B12") (pinfunction "P_B12") (pintype "passive"))
    )
    (net (code "158") (name "MEMWR") (class "Default")
      (node (ref "IC12") (pin "15") (pinfunction "O0_15") (pintype "bidirectional"))
      (node (ref "ISA1") (pin "B11") (pinfunction "P_B11") (pintype "passive"))
    )
    (net (code "159") (name "MFPCS") (class "Default")
      (node (ref "IC3") (pin "48") (pinfunction "CS_48") (pintype "input"))
      (node (ref "IC5") (pin "51") (pinfunction "~{MFPCS}_51") (pintype "output"))
    )
    (net (code "160") (name "MFPINT") (class "Default")
      (node (ref "IC3") (pin "32") (pinfunction "IRQ_32") (pintype "output"))
      (node (ref "IC5") (pin "44") (pinfunction "~{MFPINT}_44") (pintype "input"))
      (node (ref "R9") (pin "1") (pinfunction "1_1") (pintype "passive"))
    )
    (net (code "161") (name "MONO") (class "Default")
      (node (ref "IC8") (pin "30") (pinfunction "MONO_30") (pintype "output"))
      (node (ref "R60") (pin "2") (pinfunction "2_2") (pintype "passive"))
    )
    (net (code "162") (name "MONOMON") (class "Default")
      (node (ref "IC3") (pin "29") (pinfunction "I7_29") (pintype "bidirectional"))
      (node (ref "R12") (pin "1") (pinfunction "1_1") (pintype "passive"))
      (node (ref "U$6") (pin "PIN4") (pinfunction "PIN4_PIN4") (pintype "bidirectional"))
    )
    (net (code "163") (name "Net-(C40-Pad2)") (class "Default")
      (node (ref "C40") (pin "2") (pinfunction "2_2") (pintype "passive"))
      (node (ref "L1") (pin "1") (pinfunction "1_1") (pintype "passive"))
      (node (ref "R41") (pin "2") (pinfunction "2_2") (pintype "passive"))
      (node (ref "R42") (pin "2") (pinfunction "2_2") (pintype "passive"))
    )
    (net (code "164") (name "Net-(C50-Pad-)") (class "Default")
      (node (ref "C50") (pin "-") (pinfunction "-_-") (pintype "passive"))
      (node (ref "D8") (pin "C") (pinfunction "C_C") (pintype "passive"))
      (node (ref "D9") (pin "A") (pinfunction "A_A") (pintype "passive"))
    )
    (net (code "165") (name "Net-(C72-Pad1)") (class "Default")
      (node (ref "C72") (pin "1") (pinfunction "1_1") (pintype "passive"))
      (node (ref "L5") (pin "2") (pinfunction "2_2") (pintype "passive"))
    )
    (net (code "166") (name "Net-(D2-PadA)") (class "Default")
      (node (ref "D2") (pin "A") (pinfunction "A_A") (pintype "passive"))
      (node (ref "D5") (pin "A") (pinfunction "A_A") (pintype "passive"))
      (node (ref "R13") (pin "2") (pinfunction "2_2") (pintype "passive"))
      (node (ref "R14") (pin "2") (pinfunction "2_2") (pintype "passive"))
      (node (ref "R15") (pin "2") (pinfunction "2_2") (pintype "passive"))
      (node (ref "R48") (pin "1") (pinfunction "1_1") (pintype "passive"))
    )
    (net (code "167") (name "Net-(D3-PadA)") (class "Default")
      (node (ref "D3") (pin "A") (pinfunction "A_A") (pintype "passive"))
      (node (ref "D6") (pin "A") (pinfunction "A_A") (pintype "passive"))
      (node (ref "R16") (pin "2") (pinfunction "2_2") (pintype "passive"))
      (node (ref "R17") (pin "2") (pinfunction "2_2") (pintype "passive"))
      (node (ref "R18") (pin "2") (pinfunction "2_2") (pintype "passive"))
      (node (ref "R49") (pin "1") (pinfunction "1_1") (pintype "passive"))
    )
    (net (code "168") (name "Net-(D4-PadA)") (class "Default")
      (node (ref "D4") (pin "A") (pinfunction "A_A") (pintype "passive"))
      (node (ref "D7") (pin "A") (pinfunction "A_A") (pintype "passive"))
      (node (ref "R19") (pin "2") (pinfunction "2_2") (pintype "passive"))
      (node (ref "R20") (pin "2") (pinfunction "2_2") (pintype "passive"))
      (node (ref "R21") (pin "2") (pinfunction "2_2") (pintype "passive"))
      (node (ref "R50") (pin "1") (pinfunction "1_1") (pintype "passive"))
    )
    (net (code "169") (name "Net-(IC1A-IRQ)") (class "Default")
      (node (ref "IC1") (pin "7") (pinfunction "IRQ_7") (pintype "output"))
      (node (ref "IC2") (pin "7") (pinfunction "IRQ_7") (pintype "output"))
      (node (ref "IC3") (pin "26") (pinfunction "I4_26") (pintype "bidirectional"))
      (node (ref "R8") (pin "1") (pinfunction "1_1") (pintype "passive"))
    )
    (net (code "170") (name "Net-(IC3A-I3)") (class "Default")
      (node (ref "IC3") (pin "25") (pinfunction "I3_25") (pintype "bidirectional"))
      (node (ref "R11") (pin "1") (pinfunction "1_1") (pintype "passive"))
    )
    (net (code "171") (name "Net-(IC3A-RC)") (class "Default")
      (node (ref "IC3") (pin "10") (pinfunction "RC_10") (pintype "input"))
      (node (ref "IC3") (pin "16") (pinfunction "TDO_16") (pintype "output"))
      (node (ref "IC3") (pin "7") (pinfunction "TC_7") (pintype "input"))
    )
    (net (code "172") (name "Net-(IC3A-XTAL1)") (class "Default")
      (node (ref "C42") (pin "1") (pinfunction "1_1") (pintype "passive"))
      (node (ref "IC3") (pin "17") (pinfunction "XTAL1_17") (pintype "input"))
      (node (ref "X2") (pin "1") (pinfunction "1_1") (pintype "passive"))
    )
    (net (code "173") (name "Net-(IC3A-XTAL2)") (class "Default")
      (node (ref "C43") (pin "1") (pinfunction "1_1") (pintype "passive"))
      (node (ref "IC3") (pin "18") (pinfunction "XTAL2_18") (pintype "input"))
      (node (ref "X2") (pin "2") (pinfunction "2_2") (pintype "passive"))
    )
    (net (code "174") (name "Net-(IC6-~{CAS0H})") (class "Default")
      (node (ref "IC6") (pin "6") (pinfunction "~{CAS0H}_6") (pintype "output"))
      (node (ref "R1") (pin "1") (pinfunction "1_1") (pintype "passive"))
    )
    (net (code "175") (name "Net-(IC6-~{CAS0L})") (class "Default")
      (node (ref "IC6") (pin "7") (pinfunction "~{CAS0L}_7") (pintype "output"))
      (node (ref "R2") (pin "1") (pinfunction "1_1") (pintype "passive"))
    )
    (net (code "176") (name "Net-(IC6-~{CAS1H})") (class "Default")
      (node (ref "IC6") (pin "22") (pinfunction "~{CAS1H}_22") (pintype "output"))
      (node (ref "R5") (pin "1") (pinfunction "1_1") (pintype "passive"))
    )
    (net (code "177") (name "Net-(IC6-~{CAS1L})") (class "Default")
      (node (ref "IC6") (pin "21") (pinfunction "~{CAS1L}_21") (pintype "output"))
      (node (ref "R6") (pin "1") (pinfunction "1_1") (pintype "passive"))
    )
    (net (code "178") (name "Net-(IC7-ANALOGA)") (class "Default")
      (node (ref "C36") (pin "2") (pinfunction "2_2") (pintype "passive"))
      (node (ref "C37") (pin "1") (pinfunction "1_1") (pintype "passive"))
      (node (ref "C39") (pin "2") (pinfunction "2_2") (pintype "passive"))
      (node (ref "IC7") (pin "3") (pinfunction "ANALOGB_3") (pintype "output"))
      (node (ref "IC7") (pin "38") (pinfunction "ANALOGC_38") (pintype "output"))
      (node (ref "IC7") (pin "4") (pinfunction "ANALOGA_4") (pintype "output"))
      (node (ref "R39") (pin "2") (pinfunction "2_2") (pintype "passive"))
    )
    (net (code "179") (name "Net-(IC7-IOA5)") (class "Default")
      (node (ref "IC7") (pin "16") (pinfunction "IOA5_16") (pintype "output"))
      (node (ref "JP8") (pin "1") (pinfunction "1_1") (pintype "passive"))
    )
    (net (code "180") (name "Net-(IC8-B0)") (class "Default")
      (node (ref "IC8") (pin "23") (pinfunction "B0_23") (pintype "output"))
      (node (ref "R21") (pin "1") (pinfunction "1_1") (pintype "passive"))
    )
    (net (code "181") (name "Net-(IC8-B1)") (class "Default")
      (node (ref "IC8") (pin "22") (pinfunction "B1_22") (pintype "output"))
      (node (ref "R20") (pin "1") (pinfunction "1_1") (pintype "passive"))
    )
    (net (code "182") (name "Net-(IC8-B2)") (class "Default")
      (node (ref "IC8") (pin "21") (pinfunction "B2_21") (pintype "output"))
      (node (ref "R19") (pin "1") (pinfunction "1_1") (pintype "passive"))
    )
    (net (code "183") (name "Net-(IC8-G0)") (class "Default")
      (node (ref "IC8") (pin "26") (pinfunction "G0_26") (pintype "output"))
      (node (ref "R18") (pin "1") (pinfunction "1_1") (pintype "passive"))
    )
    (net (code "184") (name "Net-(IC8-G1)") (class "Default")
      (node (ref "IC8") (pin "25") (pinfunction "G1_25") (pintype "output"))
      (node (ref "R17") (pin "1") (pinfunction "1_1") (pintype "passive"))
    )
    (net (code "185") (name "Net-(IC8-G2)") (class "Default")
      (node (ref "IC8") (pin "24") (pinfunction "G2_24") (pintype "output"))
      (node (ref "R16") (pin "1") (pinfunction "1_1") (pintype "passive"))
    )
    (net (code "186") (name "Net-(IC8-R0)") (class "Default")
      (node (ref "IC8") (pin "29") (pinfunction "R0_29") (pintype "output"))
      (node (ref "R15") (pin "1") (pinfunction "1_1") (pintype "passive"))
    )
    (net (code "187") (name "Net-(IC8-R1)") (class "Default")
      (node (ref "IC8") (pin "28") (pinfunction "R1_28") (pintype "output"))
      (node (ref "R14") (pin "1") (pinfunction "1_1") (pintype "passive"))
    )
    (net (code "188") (name "Net-(IC8-R2)") (class "Default")
      (node (ref "IC8") (pin "27") (pinfunction "R2_27") (pintype "output"))
      (node (ref "R13") (pin "1") (pinfunction "1_1") (pintype "passive"))
    )
    (net (code "189") (name "Net-(IC8-VCC)") (class "Default")
      (node (ref "C41") (pin "2") (pinfunction "2_2") (pintype "passive"))
      (node (ref "C68") (pin "+") (pinfunction "+_+") (pintype "passive"))
      (node (ref "IC8") (pin "40") (pinfunction "VCC_40") (pintype "output"))
      (node (ref "L2") (pin "1") (pinfunction "1_1") (pintype "passive"))
      (node (ref "R48") (pin "2") (pinfunction "2_2") (pintype "passive"))
      (node (ref "R49") (pin "2") (pinfunction "2_2") (pintype "passive"))
      (node (ref "R50") (pin "2") (pinfunction "2_2") (pintype "passive"))
    )
    (net (code "190") (name "Net-(IC8-XTL0)") (class "Default")
      (node (ref "IC8") (pin "1") (pinfunction "XTL0_1") (pintype "output"))
      (node (ref "R22") (pin "1") (pinfunction "1_1") (pintype "passive"))
    )
    (net (code "191") (name "Net-(IC9-~{ACK})") (class "Default")
      (node (ref "IC9") (pin "37") (pinfunction "~{ACK}_37") (pintype "bidirectional"))
      (node (ref "JP6") (pin "14") (pinfunction "14_14") (pintype "passive"))
    )
    (net (code "192") (name "Net-(IC9-~{HDCS})") (class "Default")
      (node (ref "IC9") (pin "24") (pinfunction "~{HDCS}_24") (pintype "bidirectional"))
      (node (ref "JP6") (pin "9") (pinfunction "9_9") (pintype "passive"))
    )
    (net (code "193") (name "Net-(IC10-A0)") (class "Default")
      (node (ref "IC10") (pin "3") (pinfunction "A0_3") (pintype "input"))
      (node (ref "IC9") (pin "26") (pinfunction "CA1_26") (pintype "bidirectional"))
      (node (ref "JP6") (pin "16") (pinfunction "16_16") (pintype "passive"))
    )
    (net (code "194") (name "Net-(IC10-A1)") (class "Default")
      (node (ref "IC10") (pin "4") (pinfunction "A1_4") (pintype "input"))
      (node (ref "IC9") (pin "27") (pinfunction "CA2_27") (pintype "bidirectional"))
    )
    (net (code "195") (name "Net-(IC10-DIRC)") (class "Default")
      (node (ref "IC10") (pin "17") (pinfunction "DIRC_17") (pintype "bidirectional"))
      (node (ref "IC19") (pin "5") (pinfunction "I_5") (pintype "input"))
    )
    (net (code "196") (name "Net-(IC10-DRQ)") (class "Default")
      (node (ref "IC10") (pin "27") (pinfunction "DRQ_27") (pintype "bidirectional"))
      (node (ref "IC9") (pin "21") (pinfunction "FDRQ_21") (pintype "bidirectional"))
    )
    (net (code "197") (name "Net-(IC10-INTR)") (class "Default")
      (node (ref "IC10") (pin "28") (pinfunction "INTR_28") (pintype "bidirectional"))
      (node (ref "IC16") (pin "6") (pinfunction "I1_6") (pintype "input"))
    )
    (net (code "198") (name "Net-(IC10-MO)") (class "Default")
      (node (ref "IC10") (pin "20") (pinfunction "MO_20") (pintype "bidirectional"))
      (node (ref "IC20") (pin "13") (pinfunction "I_13") (pintype "input"))
    )
    (net (code "199") (name "Net-(IC10-R{slash}W)") (class "Default")
      (node (ref "IC10") (pin "2") (pinfunction "R/W_2") (pintype "bidirectional"))
      (node (ref "IC9") (pin "25") (pinfunction "CR/~{W}_25") (pintype "bidirectional"))
      (node (ref "JP6") (pin "18") (pinfunction "18_18") (pintype "passive"))
    )
    (net (code "200") (name "Net-(IC10-STEP)") (class "Default")
      (node (ref "IC10") (pin "16") (pinfunction "STEP_16") (pintype "bidirectional"))
      (node (ref "IC19") (pin "3") (pinfunction "I_3") (pintype "input"))
    )
    (net (code "201") (name "Net-(IC10-WD)") (class "Default")
      (node (ref "IC10") (pin "22") (pinfunction "WD_22") (pintype "bidirectional"))
      (node (ref "IC19") (pin "11") (pinfunction "I_11") (pintype "input"))
    )
    (net (code "202") (name "Net-(IC10-WG)") (class "Default")
      (node (ref "IC10") (pin "21") (pinfunction "WG_21") (pintype "bidirectional"))
      (node (ref "IC19") (pin "9") (pinfunction "I_9") (pintype "input"))
    )
    (net (code "203") (name "Net-(IC10-{slash}CS)") (class "Default")
      (node (ref "IC10") (pin "1") (pinfunction "/CS_1") (pintype "bidirectional"))
      (node (ref "IC9") (pin "22") (pinfunction "~{FDCS}_22") (pintype "bidirectional"))
    )
    (net (code "204") (name "Net-(IC11A-O5)") (class "Default")
      (node (ref "IC11") (pin "20") (pinfunction "O5_20") (pintype "bidirectional"))
      (node (ref "IC30") (pin "12") (pinfunction "I0_12") (pintype "input"))
      (node (ref "IC30") (pin "13") (pinfunction "I1_13") (pintype "input"))
    )
    (net (code "205") (name "Net-(IC12A-I9)") (class "Default")
      (node (ref "D12") (pin "A") (pinfunction "A_A") (pintype "passive"))
      (node (ref "D13") (pin "A") (pinfunction "A_A") (pintype "passive"))
      (node (ref "IC12") (pin "11") (pinfunction "I9_11") (pintype "input"))
      (node (ref "R80") (pin "1") (pinfunction "1_1") (pintype "passive"))
    )
    (net (code "206") (name "Net-(IC12A-O6)") (class "Default")
      (node (ref "C7") (pin "1") (pinfunction "1_1") (pintype "passive"))
      (node (ref "IC12") (pin "21") (pinfunction "O6_21") (pintype "bidirectional"))
      (node (ref "R81") (pin "1") (pinfunction "1_1") (pintype "passive"))
    )
    (net (code "207") (name "Net-(IC13-INT{slash}RB0)") (class "Default")
      (node (ref "IC13") (pin "21") (pinfunction "INT/RB0_21") (pintype "bidirectional"))
      (node (ref "RN2") (pin "5") (pinfunction "5_5") (pintype "passive"))
      (node (ref "X3") (pin "1-1") (pinfunction "1_1-1") (pintype "passive"))
    )
    (net (code "208") (name "Net-(IC13-OSC1{slash}CLKIN)") (class "Default")
      (node (ref "C4") (pin "2") (pinfunction "2_2") (pintype "passive"))
      (node (ref "IC13") (pin "9") (pinfunction "OSC1/CLKIN_9") (pintype "input"))
      (node (ref "Q1") (pin "2") (pinfunction "2_2") (pintype "passive"))
    )
    (net (code "209") (name "Net-(IC13-OSC2{slash}CLKOUT)") (class "Default")
      (node (ref "C3") (pin "2") (pinfunction "2_2") (pintype "passive"))
      (node (ref "IC13") (pin "10") (pinfunction "OSC2/CLKOUT_10") (pintype "output"))
      (node (ref "Q1") (pin "1") (pinfunction "1_1") (pintype "passive"))
    )
    (net (code "210") (name "Net-(IC13-PGC{slash}RB6)") (class "Default")
      (node (ref "IC13") (pin "27") (pinfunction "PGC/RB6_27") (pintype "bidirectional"))
      (node (ref "JP3") (pin "5") (pinfunction "5_5") (pintype "passive"))
    )
    (net (code "211") (name "Net-(IC13-PGD{slash}RB7)") (class "Default")
      (node (ref "IC13") (pin "28") (pinfunction "PGD/RB7_28") (pintype "bidirectional"))
      (node (ref "JP3") (pin "4") (pinfunction "4_4") (pintype "passive"))
    )
    (net (code "212") (name "Net-(IC13-PGM{slash}RB3)") (class "Default")
      (node (ref "IC13") (pin "24") (pinfunction "PGM/RB3_24") (pintype "bidirectional"))
      (node (ref "RN2") (pin "2") (pinfunction "2_2") (pintype "passive"))
      (node (ref "X3") (pin "2-5") (pinfunction "5_2-5") (pintype "passive"))
    )
    (net (code "213") (name "Net-(IC13-RA1{slash}AN1)") (class "Default")
      (node (ref "IC13") (pin "3") (pinfunction "RA1/AN1_3") (pintype "bidirectional"))
      (node (ref "J3") (pin "1") (pinfunction "1_1") (pintype "passive"))
      (node (ref "RN1") (pin "3") (pinfunction "3_3") (pintype "passive"))
    )
    (net (code "214") (name "Net-(IC13-RA2{slash}AN2)") (class "Default")
      (node (ref "IC13") (pin "4") (pinfunction "RA2/AN2_4") (pintype "bidirectional"))
      (node (ref "J3") (pin "2") (pinfunction "2_2") (pintype "passive"))
      (node (ref "RN1") (pin "4") (pinfunction "4_4") (pintype "passive"))
    )
    (net (code "215") (name "Net-(IC13-RA3{slash}AN3)") (class "Default")
      (node (ref "IC13") (pin "5") (pinfunction "RA3/AN3_5") (pintype "bidirectional"))
      (node (ref "J3") (pin "3") (pinfunction "3_3") (pintype "passive"))
      (node (ref "RN1") (pin "5") (pinfunction "5_5") (pintype "passive"))
    )
    (net (code "216") (name "Net-(IC13-RA4{slash}T0CKI)") (class "Default")
      (node (ref "IC13") (pin "6") (pinfunction "RA4/T0CKI_6") (pintype "bidirectional"))
      (node (ref "J3") (pin "4") (pinfunction "4_4") (pintype "passive"))
      (node (ref "RN1") (pin "6") (pinfunction "6_6") (pintype "passive"))
    )
    (net (code "217") (name "Net-(IC13-RA5{slash}AN4)") (class "Default")
      (node (ref "IC13") (pin "7") (pinfunction "RA5/AN4_7") (pintype "bidirectional"))
      (node (ref "J3") (pin "6") (pinfunction "6_6") (pintype "passive"))
      (node (ref "RN1") (pin "7") (pinfunction "7_7") (pintype "passive"))
    )
    (net (code "218") (name "Net-(IC13-RB1)") (class "Default")
      (node (ref "IC13") (pin "22") (pinfunction "RB1_22") (pintype "bidirectional"))
      (node (ref "RN2") (pin "4") (pinfunction "4_4") (pintype "passive"))
      (node (ref "X3") (pin "1-5") (pinfunction "5_1-5") (pintype "passive"))
    )
    (net (code "219") (name "Net-(IC13-RB2)") (class "Default")
      (node (ref "IC13") (pin "23") (pinfunction "RB2_23") (pintype "bidirectional"))
      (node (ref "RN2") (pin "3") (pinfunction "3_3") (pintype "passive"))
      (node (ref "X3") (pin "2-1") (pinfunction "1_2-1") (pintype "passive"))
    )
    (net (code "220") (name "Net-(IC13-RC0{slash}T1OSO)") (class "Default")
      (node (ref "IC13") (pin "11") (pinfunction "RC0/T1OSO_11") (pintype "bidirectional"))
      (node (ref "J6") (pin "1") (pinfunction "1_1") (pintype "passive"))
      (node (ref "RN1") (pin "8") (pinfunction "8_8") (pintype "passive"))
    )
    (net (code "221") (name "Net-(IC13-RC1{slash}T1OSI)") (class "Default")
      (node (ref "IC13") (pin "12") (pinfunction "RC1/T1OSI_12") (pintype "bidirectional"))
      (node (ref "J6") (pin "2") (pinfunction "2_2") (pintype "passive"))
      (node (ref "RN1") (pin "9") (pinfunction "9_9") (pintype "passive"))
    )
    (net (code "222") (name "Net-(IC13-RC2{slash}CCP1)") (class "Default")
      (node (ref "IC13") (pin "13") (pinfunction "RC2/CCP1_13") (pintype "bidirectional"))
      (node (ref "J6") (pin "3") (pinfunction "3_3") (pintype "passive"))
      (node (ref "RN2") (pin "7") (pinfunction "7_7") (pintype "passive"))
    )
    (net (code "223") (name "Net-(IC13-RC3{slash}SCK)") (class "Default")
      (node (ref "IC13") (pin "14") (pinfunction "RC3/SCK_14") (pintype "bidirectional"))
      (node (ref "J6") (pin "4") (pinfunction "4_4") (pintype "passive"))
      (node (ref "RN2") (pin "8") (pinfunction "8_8") (pintype "passive"))
    )
    (net (code "224") (name "Net-(IC13-SDI{slash}RC4)") (class "Default")
      (node (ref "IC13") (pin "15") (pinfunction "SDI/RC4_15") (pintype "bidirectional"))
      (node (ref "J6") (pin "6") (pinfunction "6_6") (pintype "passive"))
      (node (ref "RN2") (pin "9") (pinfunction "9_9") (pintype "passive"))
    )
    (net (code "225") (name "Net-(IC13-~{MCLR{slash}THV})") (class "Default")
      (node (ref "IC13") (pin "1") (pinfunction "~{MCLR/THV}_1") (pintype "input"))
      (node (ref "JP3") (pin "1") (pinfunction "1_1") (pintype "passive"))
      (node (ref "RN1") (pin "2") (pinfunction "2_2") (pintype "passive"))
    )
    (net (code "226") (name "Net-(IC14A-I)") (class "Default")
      (node (ref "IC14") (pin "1") (pinfunction "I_1") (pintype "input"))
      (node (ref "IC2") (pin "6") (pinfunction "TXDATA_6") (pintype "output"))
    )
    (net (code "227") (name "Net-(IC14A-O)") (class "Default")
      (node (ref "IC14") (pin "2") (pinfunction "O_2") (pintype "output"))
      (node (ref "IC15") (pin "13") (pinfunction "I_13") (pintype "input"))
    )
    (net (code "228") (name "Net-(IC14B-I)") (class "Default")
      (node (ref "IC14") (pin "3") (pinfunction "I_3") (pintype "input"))
      (node (ref "IC2") (pin "2") (pinfunction "RXDATA_2") (pintype "input"))
      (node (ref "OK1") (pin "4") (pinfunction "OUT_4") (pintype "output"))
      (node (ref "R24") (pin "1") (pinfunction "1_1") (pintype "passive"))
    )
    (net (code "229") (name "Net-(IC14B-O)") (class "Default")
      (node (ref "IC14") (pin "4") (pinfunction "O_4") (pintype "output"))
      (node (ref "IC15") (pin "11") (pinfunction "I_11") (pintype "input"))
    )
    (net (code "230") (name "Net-(IC14C-O)") (class "Default")
      (node (ref "IC14") (pin "6") (pinfunction "O_6") (pintype "output"))
      (node (ref "IC16") (pin "5") (pinfunction "I0_5") (pintype "input"))
    )
    (net (code "231") (name "Net-(IC15A-I)") (class "Default")
      (node (ref "IC15") (pin "1") (pinfunction "I_1") (pintype "input"))
      (node (ref "IC15") (pin "5") (pinfunction "I_5") (pintype "input"))
      (node (ref "IC26") (pin "5") (pinfunction "OUT1_5") (pintype "output"))
    )
    (net (code "232") (name "Net-(IC15B-I)") (class "Default")
      (node (ref "IC15") (pin "3") (pinfunction "I_3") (pintype "input"))
      (node (ref "IC15") (pin "9") (pinfunction "I_9") (pintype "input"))
      (node (ref "IC26") (pin "9") (pinfunction "OUT2_9") (pintype "output"))
    )
    (net (code "233") (name "Net-(IC15E-O)") (class "Default")
      (node (ref "IC15") (pin "10") (pinfunction "O_10") (pintype "open_collector"))
      (node (ref "R26") (pin "2") (pinfunction "2_2") (pintype "passive"))
    )
    (net (code "234") (name "Net-(IC15F-O)") (class "Default")
      (node (ref "IC15") (pin "12") (pinfunction "O_12") (pintype "open_collector"))
      (node (ref "R25") (pin "2") (pinfunction "2_2") (pintype "passive"))
    )
    (net (code "235") (name "Net-(IC16A-O)") (class "Default")
      (node (ref "IC16") (pin "1") (pinfunction "O_1") (pintype "output"))
      (node (ref "IC7") (pin "27") (pinfunction "BDIR_27") (pintype "input"))
    )
    (net (code "236") (name "Net-(IC16B-O)") (class "Default")
      (node (ref "IC16") (pin "4") (pinfunction "O_4") (pintype "output"))
      (node (ref "IC3") (pin "27") (pinfunction "I5_27") (pintype "bidirectional"))
    )
    (net (code "237") (name "Net-(IC16D-O)") (class "Default")
      (node (ref "IC16") (pin "13") (pinfunction "O_13") (pintype "output"))
      (node (ref "IC7") (pin "29") (pinfunction "BC1_29") (pintype "input"))
    )
    (net (code "238") (name "Net-(IC17A-I)") (class "Default")
      (node (ref "IC17") (pin "2") (pinfunction "I_2") (pintype "input"))
      (node (ref "IC7") (pin "17") (pinfunction "IOA4_17") (pintype "output"))
    )
    (net (code "239") (name "Net-(IC17A-O)") (class "Default")
      (node (ref "IC17") (pin "3") (pinfunction "O_3") (pintype "output"))
      (node (ref "JP7") (pin "20") (pinfunction "20_20") (pintype "passive"))
    )
    (net (code "240") (name "Net-(IC17C-I0)") (class "Default")
      (node (ref "IC17") (pin "10") (pinfunction "I1_10") (pintype "input"))
      (node (ref "IC17") (pin "9") (pinfunction "I0_9") (pintype "input"))
      (node (ref "IC3") (pin "8") (pinfunction "SO_8") (pintype "output"))
    )
    (net (code "241") (name "Net-(IC17C-O)") (class "Default")
      (node (ref "IC17") (pin "8") (pinfunction "O_8") (pintype "output"))
      (node (ref "JP7") (pin "2") (pinfunction "2_2") (pintype "passive"))
    )
    (net (code "242") (name "Net-(IC17D-I0)") (class "Default")
      (node (ref "IC17") (pin "12") (pinfunction "I0_12") (pintype "input"))
      (node (ref "IC17") (pin "13") (pinfunction "I1_13") (pintype "input"))
      (node (ref "IC7") (pin "18") (pinfunction "IOA3_18") (pintype "output"))
    )
    (net (code "243") (name "Net-(IC17D-O)") (class "Default")
      (node (ref "IC17") (pin "11") (pinfunction "O_11") (pintype "output"))
      (node (ref "JP7") (pin "4") (pinfunction "4_4") (pintype "passive"))
    )
    (net (code "244") (name "Net-(IC18A-I)") (class "Default")
      (node (ref "IC18") (pin "1") (pinfunction "I_1") (pintype "input"))
      (node (ref "JP7") (pin "3") (pinfunction "3_3") (pintype "passive"))
    )
    (net (code "245") (name "Net-(IC18A-O)") (class "Default")
      (node (ref "IC18") (pin "3") (pinfunction "O_3") (pintype "output"))
      (node (ref "IC3") (pin "9") (pinfunction "SI_9") (pintype "input"))
    )
    (net (code "246") (name "Net-(IC18A-RC)") (class "Default")
      (node (ref "C17") (pin "1") (pinfunction "1_1") (pintype "passive"))
      (node (ref "IC18") (pin "2") (pinfunction "RC_2") (pintype "input"))
    )
    (net (code "247") (name "Net-(IC18B-I)") (class "Default")
      (node (ref "IC18") (pin "4") (pinfunction "I_4") (pintype "input"))
      (node (ref "JP7") (pin "8") (pinfunction "8_8") (pintype "passive"))
    )
    (net (code "248") (name "Net-(IC18B-O)") (class "Default")
      (node (ref "IC18") (pin "6") (pinfunction "O_6") (pintype "output"))
      (node (ref "IC3") (pin "23") (pinfunction "I1_23") (pintype "bidirectional"))
    )
    (net (code "249") (name "Net-(IC18B-RC)") (class "Default")
      (node (ref "C19") (pin "1") (pinfunction "1_1") (pintype "passive"))
      (node (ref "IC18") (pin "5") (pinfunction "RC_5") (pintype "input"))
    )
    (net (code "250") (name "Net-(IC18C-I)") (class "Default")
      (node (ref "IC18") (pin "10") (pinfunction "I_10") (pintype "input"))
      (node (ref "JP7") (pin "22") (pinfunction "22_22") (pintype "passive"))
    )
    (net (code "251") (name "Net-(IC18C-O)") (class "Default")
      (node (ref "IC18") (pin "8") (pinfunction "O_8") (pintype "output"))
      (node (ref "IC3") (pin "28") (pinfunction "I6_28") (pintype "bidirectional"))
    )
    (net (code "252") (name "Net-(IC18C-RC)") (class "Default")
      (node (ref "C20") (pin "1") (pinfunction "1_1") (pintype "passive"))
      (node (ref "IC18") (pin "9") (pinfunction "RC_9") (pintype "input"))
    )
    (net (code "253") (name "Net-(IC18D-I)") (class "Default")
      (node (ref "IC18") (pin "13") (pinfunction "I_13") (pintype "input"))
      (node (ref "JP7") (pin "5") (pinfunction "5_5") (pintype "passive"))
    )
    (net (code "254") (name "Net-(IC18D-O)") (class "Default")
      (node (ref "IC18") (pin "11") (pinfunction "O_11") (pintype "output"))
      (node (ref "IC3") (pin "24") (pinfunction "I2_24") (pintype "bidirectional"))
    )
    (net (code "255") (name "Net-(IC18D-RC)") (class "Default")
      (node (ref "C18") (pin "1") (pinfunction "1_1") (pintype "passive"))
      (node (ref "IC18") (pin "12") (pinfunction "RC_12") (pintype "input"))
    )
    (net (code "256") (name "Net-(IC19A-I)") (class "Default")
      (node (ref "IC19") (pin "1") (pinfunction "I_1") (pintype "input"))
      (node (ref "IC7") (pin "21") (pinfunction "IOA0_21") (pintype "output"))
    )
    (net (code "257") (name "Net-(IC19A-O)") (class "Default")
      (node (ref "IC19") (pin "13") (pinfunction "I_13") (pintype "input"))
      (node (ref "IC19") (pin "2") (pinfunction "O_2") (pintype "open_collector"))
      (node (ref "R38") (pin "1") (pinfunction "1_1") (pintype "passive"))
    )
    (net (code "258") (name "Net-(IC19B-O)") (class "Default")
      (node (ref "IC19") (pin "4") (pinfunction "O_4") (pintype "open_collector"))
      (node (ref "R32") (pin "2") (pinfunction "2_2") (pintype "passive"))
    )
    (net (code "259") (name "Net-(IC19E-O)") (class "Default")
      (node (ref "IC19") (pin "10") (pinfunction "O_10") (pintype "open_collector"))
      (node (ref "R33") (pin "2") (pinfunction "2_2") (pintype "passive"))
    )
    (net (code "260") (name "Net-(IC20A-I)") (class "Default")
      (node (ref "IC20") (pin "1") (pinfunction "I_1") (pintype "input"))
      (node (ref "JP6") (pin "19") (pinfunction "19_19") (pintype "passive"))
      (node (ref "R31") (pin "1") (pinfunction "1_1") (pintype "passive"))
    )
    (net (code "261") (name "Net-(IC20A-O)") (class "Default")
      (node (ref "IC20") (pin "2") (pinfunction "O_2") (pintype "open_collector"))
      (node (ref "IC9") (pin "23") (pinfunction "HDRQ_23") (pintype "bidirectional"))
      (node (ref "R30") (pin "1") (pinfunction "1_1") (pintype "passive"))
    )
    (net (code "262") (name "Net-(IC26-CONT1)") (class "Default")
      (node (ref "C47") (pin "2") (pinfunction "2_2") (pintype "passive"))
      (node (ref "IC26") (pin "3") (pinfunction "CONT1_3") (pintype "input"))
    )
    (net (code "263") (name "Net-(IC26-CONT2)") (class "Default")
      (node (ref "C48") (pin "2") (pinfunction "2_2") (pintype "passive"))
      (node (ref "IC26") (pin "11") (pinfunction "CONT2_11") (pintype "input"))
    )
    (net (code "264") (name "Net-(IC26-DIS1)") (class "Default")
      (node (ref "C46") (pin "2") (pinfunction "2_2") (pintype "passive"))
      (node (ref "IC26") (pin "1") (pinfunction "DIS1_1") (pintype "input"))
      (node (ref "IC26") (pin "2") (pinfunction "TRES1_2") (pintype "input"))
      (node (ref "R65") (pin "1") (pinfunction "1_1") (pintype "passive"))
    )
    (net (code "265") (name "Net-(IC26-TRES2)") (class "Default")
      (node (ref "C45") (pin "2") (pinfunction "2_2") (pintype "passive"))
      (node (ref "IC26") (pin "12") (pinfunction "TRES2_12") (pintype "input"))
      (node (ref "IC26") (pin "8") (pinfunction "TRIG2_8") (pintype "input"))
      (node (ref "R64") (pin "1") (pinfunction "1_1") (pintype "passive"))
    )
    (net (code "266") (name "Net-(IC26-TRIG1)") (class "Default")
      (node (ref "C49") (pin "2") (pinfunction "2_2") (pintype "passive"))
      (node (ref "IC26") (pin "6") (pinfunction "TRIG1_6") (pintype "input"))
      (node (ref "JP1") (pin "2") (pinfunction "2_2") (pintype "passive"))
      (node (ref "R66") (pin "1") (pinfunction "1_1") (pintype "passive"))
    )
    (net (code "267") (name "Net-(IC27-AN)") (class "Default")
      (node (ref "C50") (pin "+") (pinfunction "+_+") (pintype "passive"))
      (node (ref "IC27") (pin "10") (pinfunction "COL_10") (pintype "output"))
      (node (ref "IC27") (pin "7") (pinfunction "AN_7") (pintype "bidirectional"))
      (node (ref "L3") (pin "2") (pinfunction "2_2") (pintype "passive"))
    )
    (net (code "268") (name "Net-(IC27-COMP)") (class "Default")
      (node (ref "IC27") (pin "1") (pinfunction "COMP_1") (pintype "bidirectional"))
      (node (ref "R68") (pin "1") (pinfunction "1_1") (pintype "passive"))
      (node (ref "R69") (pin "2") (pinfunction "2_2") (pintype "passive"))
    )
    (net (code "269") (name "Net-(IC27-FREQ)") (class "Default")
      (node (ref "C55") (pin "1") (pinfunction "1_1") (pintype "passive"))
      (node (ref "IC27") (pin "3") (pinfunction "FREQ_3") (pintype "bidirectional"))
    )
    (net (code "270") (name "Net-(IC27-ILIM)") (class "Default")
      (node (ref "C56") (pin "1") (pinfunction "1_1") (pintype "passive"))
      (node (ref "IC27") (pin "13") (pinfunction "ILIM_13") (pintype "bidirectional"))
      (node (ref "L3") (pin "1") (pinfunction "1_1") (pintype "passive"))
      (node (ref "R67") (pin "2") (pinfunction "2_2") (pintype "passive"))
    )
    (net (code "271") (name "Net-(IC30B-O)") (class "Default")
      (node (ref "IC30") (pin "10") (pinfunction "I1_10") (pintype "input"))
      (node (ref "IC30") (pin "6") (pinfunction "O_6") (pintype "open_collector"))
      (node (ref "IC30") (pin "9") (pinfunction "I0_9") (pintype "input"))
      (node (ref "R79") (pin "1") (pinfunction "1_1") (pintype "passive"))
    )
    (net (code "272") (name "Net-(IC33A-I)") (class "Default")
      (node (ref "C70") (pin "1") (pinfunction "1_1") (pintype "passive"))
      (node (ref "IC33") (pin "2") (pinfunction "I_2") (pintype "input"))
      (node (ref "Q2") (pin "1") (pinfunction "1_1") (pintype "passive"))
      (node (ref "R85") (pin "2") (pinfunction "2_2") (pintype "passive"))
    )
    (net (code "273") (name "Net-(J4-Pad1)") (class "Default")
      (node (ref "J4") (pin "1") (pinfunction "1_1") (pintype "input"))
      (node (ref "R28") (pin "1") (pinfunction "1_1") (pintype "passive"))
    )
    (net (code "274") (name "Net-(J4-Pad3)") (class "Default")
      (node (ref "J4") (pin "3") (pinfunction "3_3") (pintype "input"))
      (node (ref "R26") (pin "1") (pinfunction "1_1") (pintype "passive"))
    )
    (net (code "275") (name "Net-(J4-Pad4)") (class "Default")
      (node (ref "J4") (pin "4") (pinfunction "4_4") (pintype "input"))
      (node (ref "R29") (pin "1") (pinfunction "1_1") (pintype "passive"))
    )
    (net (code "276") (name "Net-(J4-Pad5)") (class "Default")
      (node (ref "J4") (pin "5") (pinfunction "5_5") (pintype "input"))
      (node (ref "R25") (pin "1") (pinfunction "1_1") (pintype "passive"))
    )
    (net (code "277") (name "Net-(J5-Pad4)") (class "Default")
      (node (ref "J5") (pin "4") (pinfunction "4_4") (pintype "input"))
      (node (ref "R27") (pin "1") (pinfunction "1_1") (pintype "passive"))
    )
    (net (code "278") (name "Net-(JP4-Pad20)") (class "Default")
      (node (ref "JP4") (pin "20") (pinfunction "20_20") (pintype "passive"))
      (node (ref "PWR") (pin "1") (pinfunction "1_1") (pintype "passive"))
    )
    (net (code "279") (name "Net-(JP4-Pad29)") (class "Default")
      (node (ref "JP4") (pin "29") (pinfunction "29_29") (pintype "passive"))
      (node (ref "R83") (pin "1") (pinfunction "1_1") (pintype "passive"))
    )
    (net (code "280") (name "Net-(JP4-Pad39)") (class "Default")
      (node (ref "JP4") (pin "39") (pinfunction "39_39") (pintype "passive"))
      (node (ref "R84") (pin "1") (pinfunction "1_1") (pintype "passive"))
    )
    (net (code "281") (name "Net-(JP10-Pad2)") (class "Default")
      (node (ref "JP10") (pin "2") (pinfunction "2_2") (pintype "passive"))
      (node (ref "R84") (pin "2") (pinfunction "2_2") (pintype "passive"))
    )
    (net (code "282") (name "Net-(OK1-A)") (class "Default")
      (node (ref "D1") (pin "C") (pinfunction "C_C") (pintype "passive"))
      (node (ref "OK1") (pin "1") (pinfunction "A_1") (pintype "passive"))
      (node (ref "R27") (pin "2") (pinfunction "2_2") (pintype "passive"))
    )
    (net (code "283") (name "Net-(OK1-C)") (class "Default")
      (node (ref "D1") (pin "A") (pinfunction "A_A") (pintype "passive"))
      (node (ref "J5") (pin "5") (pinfunction "5_5") (pintype "input"))
      (node (ref "OK1") (pin "2") (pinfunction "C_2") (pintype "passive"))
    )
    (net (code "284") (name "Net-(Q3-E)") (class "Default")
      (node (ref "JP4") (pin "1") (pinfunction "1_1") (pintype "passive"))
      (node (ref "Q3") (pin "3") (pinfunction "E_3") (pintype "passive"))
    )
    (net (code "285") (name "Net-(R63-Pad1)") (class "Default")
      (node (ref "R63") (pin "1") (pinfunction "1_1") (pintype "passive"))
      (node (ref "U$6") (pin "PIN11") (pinfunction "PIN11_PIN11") (pintype "bidirectional"))
    )
    (net (code "286") (name "Net-(R70-Pad1)") (class "Default")
      (node (ref "R70") (pin "1") (pinfunction "1_1") (pintype "passive"))
      (node (ref "U$6") (pin "PIN8") (pinfunction "PIN8_PIN8") (pintype "bidirectional"))
    )
    (net (code "287") (name "Net-(T1-B)") (class "Default")
      (node (ref "C37") (pin "2") (pinfunction "2_2") (pintype "passive"))
      (node (ref "R40") (pin "2") (pinfunction "2_2") (pintype "passive"))
      (node (ref "R41") (pin "1") (pinfunction "1_1") (pintype "passive"))
      (node (ref "T1") (pin "2") (pinfunction "B_2") (pintype "passive"))
    )
    (net (code "288") (name "Net-(T1-C)") (class "Default")
      (node (ref "C38") (pin "+") (pinfunction "+_+") (pintype "passive"))
      (node (ref "R42") (pin "1") (pinfunction "1_1") (pintype "passive"))
      (node (ref "T1") (pin "1") (pinfunction "C_1") (pintype "passive"))
    )
    (net (code "289") (name "Net-(T1-E)") (class "Default")
      (node (ref "R43") (pin "2") (pinfunction "2_2") (pintype "passive"))
      (node (ref "T1") (pin "3") (pinfunction "E_3") (pintype "passive"))
    )
    (net (code "290") (name "Net-(T2-B)") (class "Default")
      (node (ref "D2") (pin "C") (pinfunction "C_C") (pintype "passive"))
      (node (ref "R3") (pin "2") (pinfunction "2_2") (pintype "passive"))
      (node (ref "R4") (pin "2") (pinfunction "2_2") (pintype "passive"))
      (node (ref "T2") (pin "2") (pinfunction "B_2") (pintype "passive"))
    )
    (net (code "291") (name "Net-(T2-C)") (class "Default")
      (node (ref "C59") (pin "1") (pinfunction "1_1") (pintype "passive"))
      (node (ref "L4") (pin "1") (pinfunction "1_1") (pintype "passive"))
      (node (ref "R3") (pin "1") (pinfunction "1_1") (pintype "passive"))
      (node (ref "R52") (pin "1") (pinfunction "1_1") (pintype "passive"))
      (node (ref "R56") (pin "1") (pinfunction "1_1") (pintype "passive"))
      (node (ref "T2") (pin "1") (pinfunction "C_1") (pintype "passive"))
      (node (ref "T3") (pin "1") (pinfunction "C_1") (pintype "passive"))
      (node (ref "T4") (pin "1") (pinfunction "C_1") (pintype "passive"))
      (node (ref "T5") (pin "1") (pinfunction "C_1") (pintype "passive"))
    )
    (net (code "292") (name "Net-(T2-E)") (class "Default")
      (node (ref "R47") (pin "2") (pinfunction "2_2") (pintype "passive"))
      (node (ref "R51") (pin "2") (pinfunction "2_2") (pintype "passive"))
      (node (ref "R71") (pin "2") (pinfunction "2_2") (pintype "passive"))
      (node (ref "T2") (pin "3") (pinfunction "E_3") (pintype "passive"))
    )
    (net (code "293") (name "Net-(T3-B)") (class "Default")
      (node (ref "D3") (pin "C") (pinfunction "C_C") (pintype "passive"))
      (node (ref "R52") (pin "2") (pinfunction "2_2") (pintype "passive"))
      (node (ref "R53") (pin "2") (pinfunction "2_2") (pintype "passive"))
      (node (ref "T3") (pin "2") (pinfunction "B_2") (pintype "passive"))
    )
    (net (code "294") (name "Net-(T3-E)") (class "Default")
      (node (ref "R54") (pin "2") (pinfunction "2_2") (pintype "passive"))
      (node (ref "R55") (pin "2") (pinfunction "2_2") (pintype "passive"))
      (node (ref "R72") (pin "2") (pinfunction "2_2") (pintype "passive"))
      (node (ref "T3") (pin "3") (pinfunction "E_3") (pintype "passive"))
    )
    (net (code "295") (name "Net-(T4-B)") (class "Default")
      (node (ref "D4") (pin "C") (pinfunction "C_C") (pintype "passive"))
      (node (ref "R56") (pin "2") (pinfunction "2_2") (pintype "passive"))
      (node (ref "R57") (pin "2") (pinfunction "2_2") (pintype "passive"))
      (node (ref "T4") (pin "2") (pinfunction "B_2") (pintype "passive"))
    )
    (net (code "296") (name "Net-(T4-E)") (class "Default")
      (node (ref "R58") (pin "2") (pinfunction "2_2") (pintype "passive"))
      (node (ref "R59") (pin "2") (pinfunction "2_2") (pintype "passive"))
      (node (ref "R73") (pin "2") (pinfunction "2_2") (pintype "passive"))
      (node (ref "T4") (pin "3") (pinfunction "E_3") (pintype "passive"))
    )
    (net (code "297") (name "Net-(T5-B)") (class "Default")
      (node (ref "R60") (pin "1") (pinfunction "1_1") (pintype "passive"))
      (node (ref "R61") (pin "2") (pinfunction "2_2") (pintype "passive"))
      (node (ref "T5") (pin "2") (pinfunction "B_2") (pintype "passive"))
    )
    (net (code "298") (name "Net-(T5-E)") (class "Default")
      (node (ref "R62") (pin "2") (pinfunction "2_2") (pintype "passive"))
      (node (ref "R63") (pin "2") (pinfunction "2_2") (pintype "passive"))
      (node (ref "T5") (pin "3") (pinfunction "E_3") (pintype "passive"))
    )
    (net (code "299") (name "Net-(T6-B)") (class "Default")
      (node (ref "D10") (pin "A") (pinfunction "A_A") (pintype "passive"))
      (node (ref "D11") (pin "A") (pinfunction "A_A") (pintype "passive"))
      (node (ref "R76") (pin "2") (pinfunction "2_2") (pintype "passive"))
      (node (ref "T6") (pin "2") (pinfunction "B_2") (pintype "passive"))
    )
    (net (code "300") (name "Net-(T6-E)") (class "Default")
      (node (ref "R74") (pin "2") (pinfunction "2_2") (pintype "passive"))
      (node (ref "R75") (pin "1") (pinfunction "1_1") (pintype "passive"))
      (node (ref "T6") (pin "3") (pinfunction "E_3") (pintype "passive"))
    )
    (net (code "301") (name "Net-(T7-B)") (class "Default")
      (node (ref "C7") (pin "2") (pinfunction "2_2") (pintype "passive"))
      (node (ref "R81") (pin "2") (pinfunction "2_2") (pintype "passive"))
      (node (ref "T7") (pin "2") (pinfunction "B_2") (pintype "passive"))
    )
    (net (code "302") (name "Net-(X4F-S)") (class "Default")
      (node (ref "JP13") (pin "2") (pinfunction "2_2") (pintype "passive"))
      (node (ref "X4") (pin "14") (pinfunction "S_14") (pintype "passive"))
    )
    (net (code "303") (name "Net-(X4T-S)") (class "Default")
      (node (ref "JP13") (pin "3") (pinfunction "3_3") (pintype "passive"))
      (node (ref "X4") (pin "9") (pinfunction "S_9") (pintype "passive"))
    )
    (net (code "304") (name "R") (class "Default")
      (node (ref "R51") (pin "1") (pinfunction "1_1") (pintype "passive"))
      (node (ref "U$6") (pin "PIN7") (pinfunction "PIN7_PIN7") (pintype "bidirectional"))
    )
    (net (code "305") (name "R2") (class "Default")
      (node (ref "R71") (pin "1") (pinfunction "1_1") (pintype "passive"))
      (node (ref "VGA") (pin "1") (pinfunction "1_1") (pintype "passive"))
    )
    (net (code "306") (name "RAM") (class "Default")
      (node (ref "IC5") (pin "23") (pinfunction "~{RAM}_23") (pintype "bidirectional"))
      (node (ref "IC6") (pin "33") (pinfunction "~{RAM}_33") (pintype "input"))
    )
    (net (code "307") (name "RAS0") (class "Default")
      (node (ref "IC6") (pin "8") (pinfunction "~{RAS0}_8") (pintype "output"))
      (node (ref "JP9") (pin "25") (pinfunction "25_25") (pintype "passive"))
    )
    (net (code "308") (name "RAS1") (class "Default")
      (node (ref "IC6") (pin "18") (pinfunction "~{RAS1}_18") (pintype "output"))
      (node (ref "JP9") (pin "26") (pinfunction "26_26") (pintype "passive"))
    )
    (net (code "309") (name "RDAT") (class "Default")
      (node (ref "IC22") (pin "1") (pinfunction "OC_1") (pintype "input"))
      (node (ref "IC23") (pin "1") (pinfunction "OC_1") (pintype "input"))
      (node (ref "IC6") (pin "30") (pinfunction "~{RDAT}_30") (pintype "input"))
    )
    (net (code "310") (name "RDY") (class "Default")
      (node (ref "IC5") (pin "28") (pinfunction "~{RDY}_28") (pintype "output"))
      (node (ref "IC9") (pin "38") (pinfunction "RDY_38") (pintype "input"))
      (node (ref "R10") (pin "1") (pinfunction "1_1") (pintype "passive"))
    )
    (net (code "311") (name "RDY2") (class "Default")
      (node (ref "IC12") (pin "14") (pinfunction "I11_14") (pintype "input"))
      (node (ref "ISA1") (pin "A10") (pinfunction "P_A10") (pintype "passive"))
      (node (ref "R82") (pin "1") (pinfunction "1_1") (pintype "passive"))
    )
    (net (code "312") (name "RESET") (class "Default")
      (node (ref "IC10") (pin "13") (pinfunction "/MR_13") (pintype "bidirectional"))
      (node (ref "IC12") (pin "10") (pinfunction "I8_10") (pintype "input"))
      (node (ref "IC15") (pin "2") (pinfunction "O_2") (pintype "open_collector"))
      (node (ref "IC15") (pin "4") (pinfunction "O_4") (pintype "open_collector"))
      (node (ref "IC3") (pin "21") (pinfunction "RESET_21") (pintype "input"))
      (node (ref "IC4") (pin "18") (pinfunction "RESET_18") (pintype "bidirectional"))
      (node (ref "IC5") (pin "22") (pinfunction "~{RESET}_22") (pintype "input"))
      (node (ref "IC7") (pin "23") (pinfunction "~{RESET}_23") (pintype "input"))
      (node (ref "JP6") (pin "12") (pinfunction "12_12") (pintype "passive"))
      (node (ref "Q3") (pin "2") (pinfunction "B_2") (pintype "passive"))
      (node (ref "RN9") (pin "2") (pinfunction "2_2") (pintype "passive"))
    )
    (net (code "313") (name "ROM0") (class "Default")
      (node (ref "IC21") (pin "10") (pinfunction "I1_10") (pintype "input"))
      (node (ref "IC5") (pin "21") (pinfunction "~{ROM0}_21") (pintype "output"))
    )
    (net (code "314") (name "ROM1") (class "Default")
      (node (ref "IC21") (pin "11") (pinfunction "I2_11") (pintype "input"))
      (node (ref "IC5") (pin "20") (pinfunction "~{ROM1}_20") (pintype "output"))
    )
    (net (code "315") (name "ROM2") (class "Default")
      (node (ref "IC11") (pin "23") (pinfunction "I12_23") (pintype "input"))
      (node (ref "IC21") (pin "9") (pinfunction "I0_9") (pintype "input"))
      (node (ref "IC5") (pin "19") (pinfunction "~{ROM2}_19") (pintype "output"))
    )
    (net (code "316") (name "ROM3") (class "Default")
      (node (ref "IC5") (pin "18") (pinfunction "~{ROM3}_18") (pintype "output"))
      (node (ref "JP14") (pin "1") (pinfunction "1_1") (pintype "passive"))
    )
    (net (code "317") (name "ROM4") (class "Default")
      (node (ref "IC5") (pin "17") (pinfunction "~{ROM4}_17") (pintype "output"))
      (node (ref "JP14") (pin "2") (pinfunction "2_2") (pintype "passive"))
    )
    (net (code "318") (name "ROM_CE") (class "Default")
      (node (ref "IC31") (pin "22") (pinfunction "~{CE}_22") (pintype "input"))
      (node (ref "IC32") (pin "22") (pinfunction "~{CE}_22") (pintype "input"))
      (node (ref "JP11") (pin "2") (pinfunction "2_2") (pintype "passive"))
    )
    (net (code "319") (name "RW") (class "Default")
      (node (ref "IC1") (pin "13") (pinfunction "R/~{W}_13") (pintype "input"))
      (node (ref "IC11") (pin "14") (pinfunction "I11_14") (pintype "input"))
      (node (ref "IC12") (pin "9") (pinfunction "I7_9") (pintype "input"))
      (node (ref "IC16") (pin "2") (pinfunction "I0_2") (pintype "input"))
      (node (ref "IC2") (pin "13") (pinfunction "R/~{W}_13") (pintype "input"))
      (node (ref "IC3") (pin "1") (pinfunction "R/~{W}_1") (pintype "input"))
      (node (ref "IC4") (pin "9") (pinfunction "R/W_9") (pintype "output"))
      (node (ref "IC5") (pin "55") (pinfunction "R/~{W}_55") (pintype "output"))
      (node (ref "IC6") (pin "34") (pinfunction "R/~{W}_34") (pintype "output"))
      (node (ref "IC8") (pin "31") (pinfunction "R/~{W}_31") (pintype "output"))
      (node (ref "IC9") (pin "1") (pinfunction "R/~{W}_1") (pintype "input"))
      (node (ref "RN5") (pin "6") (pinfunction "6_6") (pintype "passive"))
    )
    (net (code "320") (name "SELP") (class "Default")
      (node (ref "IC11") (pin "16") (pinfunction "O1_16") (pintype "bidirectional"))
      (node (ref "JP4") (pin "37") (pinfunction "37_37") (pintype "passive"))
    )
    (net (code "321") (name "SELS") (class "Default")
      (node (ref "IC11") (pin "17") (pinfunction "O2_17") (pintype "bidirectional"))
      (node (ref "JP4") (pin "38") (pinfunction "38_38") (pintype "passive"))
    )
    (net (code "322") (name "SHCS") (class "Default")
      (node (ref "IC6") (pin "28") (pinfunction "~{CMPCS}_28") (pintype "output"))
      (node (ref "IC8") (pin "38") (pinfunction "~{CS}_38") (pintype "input"))
    )
    (net (code "323") (name "SNDCS") (class "Default")
      (node (ref "IC16") (pin "12") (pinfunction "I1_12") (pintype "input"))
      (node (ref "IC16") (pin "3") (pinfunction "I1_3") (pintype "input"))
      (node (ref "IC5") (pin "53") (pinfunction "~{SNDCS}_53") (pintype "output"))
    )
    (net (code "324") (name "TOS1") (class "Default")
      (node (ref "IC21") (pin "8") (pinfunction "O_8") (pintype "output"))
      (node (ref "JP11") (pin "3") (pinfunction "3_3") (pintype "passive"))
    )
    (net (code "325") (name "TOS2") (class "Default")
      (node (ref "IC21") (pin "6") (pinfunction "O_6") (pintype "output"))
      (node (ref "JP11") (pin "1") (pinfunction "1_1") (pintype "passive"))
    )
    (net (code "326") (name "TOS_SW") (class "Default")
      (node (ref "IC31") (pin "30") (pinfunction "A17_30") (pintype "input"))
      (node (ref "IC32") (pin "30") (pinfunction "A17_30") (pintype "input"))
      (node (ref "JP12") (pin "2") (pinfunction "2_2") (pintype "passive"))
    )
    (net (code "327") (name "UDS") (class "Default")
      (node (ref "D13") (pin "C") (pinfunction "C_C") (pintype "passive"))
      (node (ref "IC4") (pin "7") (pinfunction "UDS_7") (pintype "output"))
      (node (ref "IC5") (pin "47") (pinfunction "~{UDS}_47") (pintype "output"))
      (node (ref "IC6") (pin "26") (pinfunction "~{UDS}_26") (pintype "output"))
      (node (ref "ISA1") (pin "A31") (pinfunction "P_A31") (pintype "passive"))
      (node (ref "RN5") (pin "8") (pinfunction "8_8") (pintype "passive"))
    )
    (net (code "328") (name "VCC") (class "Default")
      (node (ref "C1") (pin "1") (pinfunction "1_1") (pintype "passive"))
      (node (ref "C10") (pin "1") (pinfunction "1_1") (pintype "passive"))
      (node (ref "C11") (pin "1") (pinfunction "1_1") (pintype "passive"))
      (node (ref "C12") (pin "1") (pinfunction "1_1") (pintype "passive"))
      (node (ref "C13") (pin "1") (pinfunction "1_1") (pintype "passive"))
      (node (ref "C14") (pin "1") (pinfunction "1_1") (pintype "passive"))
      (node (ref "C15") (pin "1") (pinfunction "1_1") (pintype "passive"))
      (node (ref "C16") (pin "1") (pinfunction "1_1") (pintype "passive"))
      (node (ref "C2") (pin "1") (pinfunction "1_1") (pintype "passive"))
      (node (ref "C21") (pin "1") (pinfunction "1_1") (pintype "passive"))
      (node (ref "C22") (pin "1") (pinfunction "1_1") (pintype "passive"))
      (node (ref "C23") (pin "1") (pinfunction "1_1") (pintype "passive"))
      (node (ref "C24") (pin "1") (pinfunction "1_1") (pintype "passive"))
      (node (ref "C25") (pin "1") (pinfunction "1_1") (pintype "passive"))
      (node (ref "C26") (pin "1") (pinfunction "1_1") (pintype "passive"))
      (node (ref "C27") (pin "1") (pinfunction "1_1") (pintype "passive"))
      (node (ref "C28") (pin "1") (pinfunction "1_1") (pintype "passive"))
      (node (ref "C29") (pin "1") (pinfunction "1_1") (pintype "passive"))
      (node (ref "C30") (pin "1") (pinfunction "1_1") (pintype "passive"))
      (node (ref "C31") (pin "1") (pinfunction "1_1") (pintype "passive"))
      (node (ref "C32") (pin "1") (pinfunction "1_1") (pintype "passive"))
      (node (ref "C33") (pin "1") (pinfunction "1_1") (pintype "passive"))
      (node (ref "C34") (pin "+") (pinfunction "+_+") (pintype "passive"))
      (node (ref "C35") (pin "1") (pinfunction "1_1") (pintype "passive"))
      (node (ref "C44") (pin "1") (pinfunction "1_1") (pintype "passive"))
      (node (ref "C5") (pin "1") (pinfunction "1_1") (pintype "passive"))
      (node (ref "C57") (pin "1") (pinfunction "1_1") (pintype "passive"))
      (node (ref "C58") (pin "+") (pinfunction "+_+") (pintype "passive"))
      (node (ref "C6") (pin "1") (pinfunction "1_1") (pintype "passive"))
      (node (ref "C60") (pin "1") (pinfunction "1_1") (pintype "passive"))
      (node (ref "C61") (pin "+") (pinfunction "+_+") (pintype "passive"))
      (node (ref "C62") (pin "+") (pinfunction "+_+") (pintype "passive"))
      (node (ref "C63") (pin "+") (pinfunction "+_+") (pintype "passive"))
      (node (ref "C64") (pin "+") (pinfunction "+_+") (pintype "passive"))
      (node (ref "C65") (pin "1") (pinfunction "1_1") (pintype "passive"))
      (node (ref "C66") (pin "1") (pinfunction "1_1") (pintype "passive"))
      (node (ref "C67") (pin "+") (pinfunction "+_+") (pintype "passive"))
      (node (ref "C69") (pin "+") (pinfunction "+_+") (pintype "passive"))
      (node (ref "C8") (pin "1") (pinfunction "1_1") (pintype "passive"))
      (node (ref "C9") (pin "1") (pinfunction "1_1") (pintype "passive"))
      (node (ref "CN1") (pin "PWR") (pinfunction "PWR_PWR") (pintype "power_in"))
      (node (ref "IC1") (pin "10") (pinfunction "CS1_10") (pintype "input"))
      (node (ref "IC1") (pin "12") (pinfunction "VCC_12") (pintype "power_in"))
      (node (ref "IC10") (pin "15") (pinfunction "VCC_15") (pintype "power_in"))
      (node (ref "IC13") (pin "20") (pinfunction "VDD_20") (pintype "power_in"))
      (node (ref "IC2") (pin "12") (pinfunction "VCC_12") (pintype "power_in"))
      (node (ref "IC21") (pin "3") (pinfunction "I0_3") (pintype "input"))
      (node (ref "IC26") (pin "10") (pinfunction "RESET2_10") (pintype "input"))
      (node (ref "IC26") (pin "14") (pinfunction "VCC_14") (pintype "power_in"))
      (node (ref "IC26") (pin "4") (pinfunction "RESET1_4") (pintype "input"))
      (node (ref "IC27") (pin "14") (pinfunction "VCC_14") (pintype "passive"))
      (node (ref "IC31") (pin "31") (pinfunction "~{WE}_31") (pintype "passive"))
      (node (ref "IC31") (pin "32") (pinfunction "VCC_32") (pintype "power_in"))
      (node (ref "IC32") (pin "31") (pinfunction "~{WE}_31") (pintype "passive"))
      (node (ref "IC32") (pin "32") (pinfunction "VCC_32") (pintype "power_in"))
      (node (ref "IC5") (pin "1") (pinfunction "VCC_1") (pintype "output"))
      (node (ref "IC6") (pin "10") (pinfunction "VCCA_10") (pintype "output"))
      (node (ref "IC6") (pin "44") (pinfunction "VCCB_44") (pintype "output"))
      (node (ref "IC7") (pin "25") (pinfunction "A8_25") (pintype "input"))
      (node (ref "IC7") (pin "28") (pinfunction "BC2_28") (pintype "input"))
      (node (ref "IC7") (pin "40") (pinfunction "VCC_40") (pintype "output"))
      (node (ref "IC9") (pin "40") (pinfunction "VCC_40") (pintype "output"))
      (node (ref "ISA1") (pin "B29") (pinfunction "P_B29") (pintype "passive"))
      (node (ref "ISA1") (pin "B3") (pinfunction "P_B3") (pintype "passive"))
      (node (ref "ISA1") (pin "D16") (pinfunction "P_D16") (pintype "passive"))
      (node (ref "J3") (pin "7") (pinfunction "7_7") (pintype "passive"))
      (node (ref "J6") (pin "7") (pinfunction "7_7") (pintype "passive"))
      (node (ref "JP10") (pin "1") (pinfunction "1_1") (pintype "passive"))
      (node (ref "JP12") (pin "1") (pinfunction "1_1") (pintype "passive"))
      (node (ref "JP2") (pin "1") (pinfunction "1_1") (pintype "passive"))
      (node (ref "JP2") (pin "2") (pinfunction "2_2") (pintype "passive"))
      (node (ref "JP3") (pin "2") (pinfunction "2_2") (pintype "passive"))
      (node (ref "JP9") (pin "17") (pinfunction "17_17") (pintype "passive"))
      (node (ref "JP9") (pin "19") (pinfunction "19_19") (pintype "passive"))
      (node (ref "L1") (pin "2") (pinfunction "2_2") (pintype "passive"))
      (node (ref "L2") (pin "2") (pinfunction "2_2") (pintype "passive"))
      (node (ref "L4") (pin "2") (pinfunction "2_2") (pintype "passive"))
      (node (ref "OK1") (pin "6") (pinfunction "VCC_6") (pintype "power_in"))
      (node (ref "PWR") (pin "2") (pinfunction "2_2") (pintype "passive"))
      (node (ref "R10") (pin "2") (pinfunction "2_2") (pintype "passive"))
      (node (ref "R11") (pin "2") (pinfunction "2_2") (pintype "passive"))
      (node (ref "R12") (pin "2") (pinfunction "2_2") (pintype "passive"))
      (node (ref "R23") (pin "2") (pinfunction "2_2") (pintype "passive"))
      (node (ref "R24") (pin "2") (pinfunction "2_2") (pintype "passive"))
      (node (ref "R28") (pin "2") (pinfunction "2_2") (pintype "passive"))
      (node (ref "R29") (pin "2") (pinfunction "2_2") (pintype "passive"))
      (node (ref "R30") (pin "2") (pinfunction "2_2") (pintype "passive"))
      (node (ref "R31") (pin "2") (pinfunction "2_2") (pintype "passive"))
      (node (ref "R34") (pin "1") (pinfunction "1_1") (pintype "passive"))
      (node (ref "R35") (pin "1") (pinfunction "1_1") (pintype "passive"))
      (node (ref "R36") (pin "1") (pinfunction "1_1") (pintype "passive"))
      (node (ref "R37") (pin "1") (pinfunction "1_1") (pintype "passive"))
      (node (ref "R38") (pin "2") (pinfunction "2_2") (pintype "passive"))
      (node (ref "R44") (pin "2") (pinfunction "2_2") (pintype "passive"))
      (node (ref "R45") (pin "2") (pinfunction "2_2") (pintype "passive"))
      (node (ref "R46") (pin "2") (pinfunction "2_2") (pintype "passive"))
      (node (ref "R64") (pin "2") (pinfunction "2_2") (pintype "passive"))
      (node (ref "R65") (pin "2") (pinfunction "2_2") (pintype "passive"))
      (node (ref "R66") (pin "2") (pinfunction "2_2") (pintype "passive"))
      (node (ref "R67") (pin "1") (pinfunction "1_1") (pintype "passive"))
      (node (ref "R7") (pin "2") (pinfunction "2_2") (pintype "passive"))
      (node (ref "R76") (pin "1") (pinfunction "1_1") (pintype "passive"))
      (node (ref "R78") (pin "2") (pinfunction "2_2") (pintype "passive"))
      (node (ref "R79") (pin "2") (pinfunction "2_2") (pintype "passive"))
      (node (ref "R8") (pin "2") (pinfunction "2_2") (pintype "passive"))
      (node (ref "R80") (pin "2") (pinfunction "2_2") (pintype "passive"))
      (node (ref "R82") (pin "2") (pinfunction "2_2") (pintype "passive"))
      (node (ref "R83") (pin "2") (pinfunction "2_2") (pintype "passive"))
      (node (ref "R9") (pin "2") (pinfunction "2_2") (pintype "passive"))
      (node (ref "RN1") (pin "1") (pinfunction "1_1") (pintype "passive"))
      (node (ref "RN10") (pin "1") (pinfunction "1_1") (pintype "passive"))
      (node (ref "RN2") (pin "1") (pinfunction "1_1") (pintype "passive"))
      (node (ref "RN3") (pin "1") (pinfunction "1_1") (pintype "passive"))
      (node (ref "RN4") (pin "1") (pinfunction "1_1") (pintype "passive"))
      (node (ref "RN5") (pin "1") (pinfunction "1_1") (pintype "passive"))
      (node (ref "RN6") (pin "1") (pinfunction "1_1") (pintype "passive"))
      (node (ref "RN7") (pin "1") (pinfunction "1_1") (pintype "passive"))
      (node (ref "RN8") (pin "1") (pinfunction "1_1") (pintype "passive"))
      (node (ref "RN9") (pin "1") (pinfunction "1_1") (pintype "passive"))
      (node (ref "T6") (pin "1") (pinfunction "C_1") (pintype "passive"))
      (node (ref "VGA") (pin "16") (pinfunction "16_16") (pintype "passive"))
      (node (ref "X1") (pin "14") (pinfunction "VCC_14") (pintype "power_in"))
      (node (ref "X3") (pin "1-4") (pinfunction "4_1-4") (pintype "passive"))
      (node (ref "X3") (pin "2-4") (pinfunction "4_2-4") (pintype "passive"))
      (node (ref "X4") (pin "19") (pinfunction "S_19") (pintype "passive"))
      (node (ref "X4") (pin "20") (pinfunction "S_20") (pintype "passive"))
      (node (ref "X4") (pin "4") (pinfunction "S_4") (pintype "passive"))
      (node (ref "X4") (pin "6") (pinfunction "S_6") (pintype "passive"))
    )
    (net (code "329") (name "VMA") (class "Default")
      (node (ref "IC4") (pin "19") (pinfunction "VMA_19") (pintype "output"))
      (node (ref "IC5") (pin "16") (pinfunction "~{VMA}_16") (pintype "input"))
      (node (ref "RN9") (pin "4") (pinfunction "4_4") (pintype "passive"))
    )
    (net (code "330") (name "VPA") (class "Default")
      (node (ref "IC4") (pin "21") (pinfunction "VPA_21") (pintype "input"))
      (node (ref "IC5") (pin "29") (pinfunction "~{VPA}_29") (pintype "output"))
      (node (ref "RN9") (pin "5") (pinfunction "5_5") (pintype "passive"))
    )
    (net (code "331") (name "VRES") (class "Default")
      (node (ref "IC12") (pin "20") (pinfunction "O5_20") (pintype "bidirectional"))
      (node (ref "ISA1") (pin "B2") (pinfunction "P_B2") (pintype "passive"))
    )
    (net (code "332") (name "VSYNC") (class "Default")
      (node (ref "D10") (pin "C") (pinfunction "C_C") (pintype "passive"))
      (node (ref "IC5") (pin "38") (pinfunction "VSYNC_38") (pintype "output"))
      (node (ref "IC6") (pin "51") (pinfunction "VSYNC_51") (pintype "output"))
      (node (ref "U$6") (pin "PIN12") (pinfunction "PIN12_PIN12") (pintype "bidirectional"))
      (node (ref "VGA") (pin "14") (pinfunction "14_14") (pintype "passive"))
    )
    (net (code "333") (name "WDAT") (class "Default")
      (node (ref "IC24") (pin "1") (pinfunction "G_1") (pintype "input"))
      (node (ref "IC24") (pin "19") (pinfunction "G_19") (pintype "input"))
      (node (ref "IC25") (pin "1") (pinfunction "G_1") (pintype "input"))
      (node (ref "IC25") (pin "19") (pinfunction "G_19") (pintype "input"))
      (node (ref "IC6") (pin "25") (pinfunction "~{WDAT}_25") (pintype "input"))
    )
    (net (code "334") (name "WE") (class "Default")
      (node (ref "IC6") (pin "23") (pinfunction "~{WE}_23") (pintype "output"))
      (node (ref "JP9") (pin "37") (pinfunction "37_37") (pintype "passive"))
    )
    (net (code "335") (name "unconnected-(IC1A-RTS-Pad5)") (class "Default")
      (node (ref "IC1") (pin "5") (pinfunction "RTS_5") (pintype "output"))
    )
    (net (code "336") (name "unconnected-(IC2A-RTS-Pad5)") (class "Default")
      (node (ref "IC2") (pin "5") (pinfunction "RTS_5") (pintype "output"))
    )
    (net (code "337") (name "unconnected-(IC3A-IEO-Pad33)") (class "Default")
      (node (ref "IC3") (pin "33") (pinfunction "IEO_33") (pintype "output"))
    )
    (net (code "338") (name "unconnected-(IC3A-RR-Pad31)") (class "Default")
      (node (ref "IC3") (pin "31") (pinfunction "RR_31") (pintype "output"))
    )
    (net (code "339") (name "unconnected-(IC3A-TAO-Pad13)") (class "Default")
      (node (ref "IC3") (pin "13") (pinfunction "TAO_13") (pintype "output"))
    )
    (net (code "340") (name "unconnected-(IC3A-TBO-Pad14)") (class "Default")
      (node (ref "IC3") (pin "14") (pinfunction "TBO_14") (pintype "output"))
    )
    (net (code "341") (name "unconnected-(IC3A-TCO-Pad15)") (class "Default")
      (node (ref "IC3") (pin "15") (pinfunction "TCO_15") (pintype "output"))
    )
    (net (code "342") (name "unconnected-(IC3A-TR-Pad30)") (class "Default")
      (node (ref "IC3") (pin "30") (pinfunction "TR_30") (pintype "output"))
    )
    (net (code "343") (name "unconnected-(IC5-~{BGO}-Pad45)") (class "Default")
      (node (ref "IC5") (pin "45") (pinfunction "~{BGO}_45") (pintype "output"))
    )
    (net (code "344") (name "unconnected-(IC7-IOA7-Pad14)") (class "Default")
      (node (ref "IC7") (pin "14") (pinfunction "IOA7_14") (pintype "output"))
    )
    (net (code "345") (name "unconnected-(IC12A-O4-Pad19)") (class "Default")
      (node (ref "IC12") (pin "19") (pinfunction "O4_19") (pintype "bidirectional"))
    )
    (net (code "346") (name "unconnected-(IC13-RA0{slash}AN0-Pad2)") (class "Default")
      (node (ref "IC13") (pin "2") (pinfunction "RA0/AN0_2") (pintype "bidirectional"))
    )
    (net (code "347") (name "unconnected-(IC13-RB4-Pad25)") (class "Default")
      (node (ref "IC13") (pin "25") (pinfunction "RB4_25") (pintype "bidirectional"))
    )
    (net (code "348") (name "unconnected-(IC13-RB5-Pad26)") (class "Default")
      (node (ref "IC13") (pin "26") (pinfunction "RB5_26") (pintype "bidirectional"))
    )
    (net (code "349") (name "unconnected-(IC13-SDO{slash}RC5-Pad16)") (class "Default")
      (node (ref "IC13") (pin "16") (pinfunction "SDO/RC5_16") (pintype "bidirectional"))
    )
    (net (code "350") (name "unconnected-(IC20B-O-Pad4)") (class "Default")
      (node (ref "IC20") (pin "4") (pinfunction "O_4") (pintype "open_collector"))
    )
    (net (code "351") (name "unconnected-(IC20C-O-Pad6)") (class "Default")
      (node (ref "IC20") (pin "6") (pinfunction "O_6") (pintype "open_collector"))
    )
    (net (code "352") (name "unconnected-(IC20D-O-Pad8)") (class "Default")
      (node (ref "IC20") (pin "8") (pinfunction "O_8") (pintype "open_collector"))
    )
    (net (code "353") (name "unconnected-(IC20E-O-Pad10)") (class "Default")
      (node (ref "IC20") (pin "10") (pinfunction "O_10") (pintype "open_collector"))
    )
    (net (code "354") (name "unconnected-(IC21A-I0-Pad1)") (class "Default")
      (node (ref "IC21") (pin "1") (pinfunction "I0_1") (pintype "input"))
    )
    (net (code "355") (name "unconnected-(IC21A-I1-Pad2)") (class "Default")
      (node (ref "IC21") (pin "2") (pinfunction "I1_2") (pintype "input"))
    )
    (net (code "356") (name "unconnected-(IC21A-I2-Pad13)") (class "Default")
      (node (ref "IC21") (pin "13") (pinfunction "I2_13") (pintype "input"))
    )
    (net (code "357") (name "unconnected-(IC21A-O-Pad12)") (class "Default")
      (node (ref "IC21") (pin "12") (pinfunction "O_12") (pintype "output"))
    )
    (net (code "358") (name "unconnected-(IC26-DIS2-Pad13)") (class "Default")
      (node (ref "IC26") (pin "13") (pinfunction "DIS2_13") (pintype "input"))
    )
    (net (code "359") (name "unconnected-(IC31-NC-Pad1)") (class "Default")
      (node (ref "IC31") (pin "1") (pinfunction "NC_1") (pintype "input"))
    )
    (net (code "360") (name "unconnected-(IC32-NC-Pad1)") (class "Default")
      (node (ref "IC32") (pin "1") (pinfunction "NC_1") (pintype "input"))
    )
    (net (code "361") (name "unconnected-(ISA1A-P-PadA1)") (class "Default")
      (node (ref "ISA1") (pin "A1") (pinfunction "P_A1") (pintype "passive"))
    )
    (net (code "362") (name "unconnected-(ISA1AL-P-PadB15)") (class "Default")
      (node (ref "ISA1") (pin "B15") (pinfunction "P_B15") (pintype "passive"))
    )
    (net (code "363") (name "unconnected-(ISA1AM-P-PadB16)") (class "Default")
      (node (ref "ISA1") (pin "B16") (pinfunction "P_B16") (pintype "passive"))
    )
    (net (code "364") (name "unconnected-(ISA1AN-P-PadB17)") (class "Default")
      (node (ref "ISA1") (pin "B17") (pinfunction "P_B17") (pintype "passive"))
    )
    (net (code "365") (name "unconnected-(ISA1AO-P-PadB18)") (class "Default")
      (node (ref "ISA1") (pin "B18") (pinfunction "P_B18") (pintype "passive"))
    )
    (net (code "366") (name "unconnected-(ISA1AP-P-PadB19)") (class "Default")
      (node (ref "ISA1") (pin "B19") (pinfunction "P_B19") (pintype "passive"))
    )
    (net (code "367") (name "unconnected-(ISA1AR-P-PadB20)") (class "Default")
      (node (ref "ISA1") (pin "B20") (pinfunction "P_B20") (pintype "passive"))
    )
    (net (code "368") (name "unconnected-(ISA1AS-P-PadB21)") (class "Default")
      (node (ref "ISA1") (pin "B21") (pinfunction "P_B21") (pintype "passive"))
    )
    (net (code "369") (name "unconnected-(ISA1AT-P-PadB22)") (class "Default")
      (node (ref "ISA1") (pin "B22") (pinfunction "P_B22") (pintype "passive"))
    )
    (net (code "370") (name "unconnected-(ISA1AU-P-PadB23)") (class "Default")
      (node (ref "ISA1") (pin "B23") (pinfunction "P_B23") (pintype "passive"))
    )
    (net (code "371") (name "unconnected-(ISA1AV-P-PadB24)") (class "Default")
      (node (ref "ISA1") (pin "B24") (pinfunction "P_B24") (pintype "passive"))
    )
    (net (code "372") (name "unconnected-(ISA1AW-P-PadB25)") (class "Default")
      (node (ref "ISA1") (pin "B25") (pinfunction "P_B25") (pintype "passive"))
    )
    (net (code "373") (name "unconnected-(ISA1AX-P-PadB26)") (class "Default")
      (node (ref "ISA1") (pin "B26") (pinfunction "P_B26") (pintype "passive"))
    )
    (net (code "374") (name "unconnected-(ISA1AY-P-PadB27)") (class "Default")
      (node (ref "ISA1") (pin "B27") (pinfunction "P_B27") (pintype "passive"))
    )
    (net (code "375") (name "unconnected-(ISA1AZ-P-PadB28)") (class "Default")
      (node (ref "ISA1") (pin "B28") (pinfunction "P_B28") (pintype "passive"))
    )
    (net (code "376") (name "unconnected-(ISA1BC-P-PadB30)") (class "Default")
      (node (ref "ISA1") (pin "B30") (pinfunction "P_B30") (pintype "passive"))
    )
    (net (code "377") (name "unconnected-(ISA1BE-P-PadB4)") (class "Default")
      (node (ref "ISA1") (pin "B4") (pinfunction "P_B4") (pintype "passive"))
    )
    (net (code "378") (name "unconnected-(ISA1BF-P-PadB5)") (class "Default")
      (node (ref "ISA1") (pin "B5") (pinfunction "P_B5") (pintype "passive"))
    )
    (net (code "379") (name "unconnected-(ISA1BG-P-PadB6)") (class "Default")
      (node (ref "ISA1") (pin "B6") (pinfunction "P_B6") (pintype "passive"))
    )
    (net (code "380") (name "unconnected-(ISA1BI-P-PadB8)") (class "Default")
      (node (ref "ISA1") (pin "B8") (pinfunction "P_B8") (pintype "passive"))
    )
    (net (code "381") (name "unconnected-(ISA1BL-P-PadC10)") (class "Default")
      (node (ref "ISA1") (pin "C10") (pinfunction "P_C10") (pintype "passive"))
    )
    (net (code "382") (name "unconnected-(ISA1CB-P-PadC9)") (class "Default")
      (node (ref "ISA1") (pin "C9") (pinfunction "P_C9") (pintype "passive"))
    )
    (net (code "383") (name "unconnected-(ISA1CC-P-PadD1)") (class "Default")
      (node (ref "ISA1") (pin "D1") (pinfunction "P_D1") (pintype "passive"))
    )
    (net (code "384") (name "unconnected-(ISA1CD-P-PadD10)") (class "Default")
      (node (ref "ISA1") (pin "D10") (pinfunction "P_D10") (pintype "passive"))
    )
    (net (code "385") (name "unconnected-(ISA1CE-P-PadD11)") (class "Default")
      (node (ref "ISA1") (pin "D11") (pinfunction "P_D11") (pintype "passive"))
    )
    (net (code "386") (name "unconnected-(ISA1CF-P-PadD12)") (class "Default")
      (node (ref "ISA1") (pin "D12") (pinfunction "P_D12") (pintype "passive"))
    )
    (net (code "387") (name "unconnected-(ISA1CG-P-PadD13)") (class "Default")
      (node (ref "ISA1") (pin "D13") (pinfunction "P_D13") (pintype "passive"))
    )
    (net (code "388") (name "unconnected-(ISA1CH-P-PadD14)") (class "Default")
      (node (ref "ISA1") (pin "D14") (pinfunction "P_D14") (pintype "passive"))
    )
    (net (code "389") (name "unconnected-(ISA1CI-P-PadD15)") (class "Default")
      (node (ref "ISA1") (pin "D15") (pinfunction "P_D15") (pintype "passive"))
    )
    (net (code "390") (name "unconnected-(ISA1CK-P-PadD17)") (class "Default")
      (node (ref "ISA1") (pin "D17") (pinfunction "P_D17") (pintype "passive"))
    )
    (net (code "391") (name "unconnected-(ISA1CM-P-PadD2)") (class "Default")
      (node (ref "ISA1") (pin "D2") (pinfunction "P_D2") (pintype "passive"))
    )
    (net (code "392") (name "unconnected-(ISA1CN-P-PadD3)") (class "Default")
      (node (ref "ISA1") (pin "D3") (pinfunction "P_D3") (pintype "passive"))
    )
    (net (code "393") (name "unconnected-(ISA1CO-P-PadD4)") (class "Default")
      (node (ref "ISA1") (pin "D4") (pinfunction "P_D4") (pintype "passive"))
    )
    (net (code "394") (name "unconnected-(ISA1CP-P-PadD5)") (class "Default")
      (node (ref "ISA1") (pin "D5") (pinfunction "P_D5") (pintype "passive"))
    )
    (net (code "395") (name "unconnected-(ISA1CQ-P-PadD6)") (class "Default")
      (node (ref "ISA1") (pin "D6") (pinfunction "P_D6") (pintype "passive"))
    )
    (net (code "396") (name "unconnected-(ISA1CR-P-PadD7)") (class "Default")
      (node (ref "ISA1") (pin "D7") (pinfunction "P_D7") (pintype "passive"))
    )
    (net (code "397") (name "unconnected-(ISA1CS-P-PadD8)") (class "Default")
      (node (ref "ISA1") (pin "D8") (pinfunction "P_D8") (pintype "passive"))
    )
    (net (code "398") (name "unconnected-(ISA1CT-P-PadD9)") (class "Default")
      (node (ref "ISA1") (pin "D9") (pinfunction "P_D9") (pintype "passive"))
    )
    (net (code "399") (name "unconnected-(J1-PadRSH)") (class "Default")
      (node (ref "J1") (pin "RSH") (pinfunction "RSH_RSH") (pintype "bidirectional"))
    )
    (net (code "400") (name "unconnected-(J1-PadTSH)") (class "Default")
      (node (ref "J1") (pin "TSH") (pinfunction "TSH_TSH") (pintype "bidirectional"))
    )
    (net (code "401") (name "unconnected-(J3-Pad5)") (class "Default")
      (node (ref "J3") (pin "5") (pinfunction "5_5") (pintype "passive"))
    )
    (net (code "402") (name "unconnected-(J3-Pad9)") (class "Default")
      (node (ref "J3") (pin "9") (pinfunction "9_9") (pintype "passive"))
    )
    (net (code "403") (name "unconnected-(J5-Pad1)") (class "Default")
      (node (ref "J5") (pin "1") (pinfunction "1_1") (pintype "input"))
    )
    (net (code "404") (name "unconnected-(J5-Pad3)") (class "Default")
      (node (ref "J5") (pin "3") (pinfunction "3_3") (pintype "input"))
    )
    (net (code "405") (name "unconnected-(J6-Pad5)") (class "Default")
      (node (ref "J6") (pin "5") (pinfunction "5_5") (pintype "passive"))
    )
    (net (code "406") (name "unconnected-(J6-Pad9)") (class "Default")
      (node (ref "J6") (pin "9") (pinfunction "9_9") (pintype "passive"))
    )
    (net (code "407") (name "unconnected-(JP4-Pad21)") (class "Default")
      (node (ref "JP4") (pin "21") (pinfunction "21_21") (pintype "passive"))
    )
    (net (code "408") (name "unconnected-(JP4-Pad32)") (class "Default")
      (node (ref "JP4") (pin "32") (pinfunction "32_32") (pintype "passive"))
    )
    (net (code "409") (name "unconnected-(JP4-Pad34)") (class "Default")
      (node (ref "JP4") (pin "34") (pinfunction "34_34") (pintype "passive"))
    )
    (net (code "410") (name "unconnected-(JP5-Pad2)") (class "Default")
      (node (ref "JP5") (pin "2") (pinfunction "2_2") (pintype "passive"))
    )
    (net (code "411") (name "unconnected-(JP5-Pad4)") (class "Default")
      (node (ref "JP5") (pin "4") (pinfunction "4_4") (pintype "passive"))
    )
    (net (code "412") (name "unconnected-(JP5-Pad6)") (class "Default")
      (node (ref "JP5") (pin "6") (pinfunction "6_6") (pintype "passive"))
    )
    (net (code "413") (name "unconnected-(JP5-Pad34)") (class "Default")
      (node (ref "JP5") (pin "34") (pinfunction "34_34") (pintype "passive"))
    )
    (net (code "414") (name "unconnected-(JP6-Pad20)") (class "Default")
      (node (ref "JP6") (pin "20") (pinfunction "20_20") (pintype "passive"))
    )
    (net (code "415") (name "unconnected-(JP7-Pad6)") (class "Default")
      (node (ref "JP7") (pin "6") (pinfunction "6_6") (pintype "passive"))
    )
    (net (code "416") (name "unconnected-(JP7-Pad9)") (class "Default")
      (node (ref "JP7") (pin "9") (pinfunction "9_9") (pintype "passive"))
    )
    (net (code "417") (name "unconnected-(JP7-Pad10)") (class "Default")
      (node (ref "JP7") (pin "10") (pinfunction "10_10") (pintype "passive"))
    )
    (net (code "418") (name "unconnected-(JP7-Pad11)") (class "Default")
      (node (ref "JP7") (pin "11") (pinfunction "11_11") (pintype "passive"))
    )
    (net (code "419") (name "unconnected-(JP7-Pad12)") (class "Default")
      (node (ref "JP7") (pin "12") (pinfunction "12_12") (pintype "passive"))
    )
    (net (code "420") (name "unconnected-(JP7-Pad13)") (class "Default")
      (node (ref "JP7") (pin "13") (pinfunction "13_13") (pintype "passive"))
    )
    (net (code "421") (name "unconnected-(JP7-Pad14)") (class "Default")
      (node (ref "JP7") (pin "14") (pinfunction "14_14") (pintype "passive"))
    )
    (net (code "422") (name "unconnected-(JP7-Pad15)") (class "Default")
      (node (ref "JP7") (pin "15") (pinfunction "15_15") (pintype "passive"))
    )
    (net (code "423") (name "unconnected-(JP7-Pad16)") (class "Default")
      (node (ref "JP7") (pin "16") (pinfunction "16_16") (pintype "passive"))
    )
    (net (code "424") (name "unconnected-(JP7-Pad17)") (class "Default")
      (node (ref "JP7") (pin "17") (pinfunction "17_17") (pintype "passive"))
    )
    (net (code "425") (name "unconnected-(JP7-Pad18)") (class "Default")
      (node (ref "JP7") (pin "18") (pinfunction "18_18") (pintype "passive"))
    )
    (net (code "426") (name "unconnected-(JP7-Pad19)") (class "Default")
      (node (ref "JP7") (pin "19") (pinfunction "19_19") (pintype "passive"))
    )
    (net (code "427") (name "unconnected-(JP7-Pad21)") (class "Default")
      (node (ref "JP7") (pin "21") (pinfunction "21_21") (pintype "passive"))
    )
    (net (code "428") (name "unconnected-(JP7-Pad23)") (class "Default")
      (node (ref "JP7") (pin "23") (pinfunction "23_23") (pintype "passive"))
    )
    (net (code "429") (name "unconnected-(JP7-Pad24)") (class "Default")
      (node (ref "JP7") (pin "24") (pinfunction "24_24") (pintype "passive"))
    )
    (net (code "430") (name "unconnected-(JP7-Pad25)") (class "Default")
      (node (ref "JP7") (pin "25") (pinfunction "25_25") (pintype "passive"))
    )
    (net (code "431") (name "unconnected-(JP7-Pad26)") (class "Default")
      (node (ref "JP7") (pin "26") (pinfunction "26_26") (pintype "passive"))
    )
    (net (code "432") (name "unconnected-(JP8-Pad10)") (class "Default")
      (node (ref "JP8") (pin "10") (pinfunction "10_10") (pintype "passive"))
    )
    (net (code "433") (name "unconnected-(JP8-Pad12)") (class "Default")
      (node (ref "JP8") (pin "12") (pinfunction "12_12") (pintype "passive"))
    )
    (net (code "434") (name "unconnected-(JP8-Pad13)") (class "Default")
      (node (ref "JP8") (pin "13") (pinfunction "13_13") (pintype "passive"))
    )
    (net (code "435") (name "unconnected-(JP8-Pad14)") (class "Default")
      (node (ref "JP8") (pin "14") (pinfunction "14_14") (pintype "passive"))
    )
    (net (code "436") (name "unconnected-(JP8-Pad15)") (class "Default")
      (node (ref "JP8") (pin "15") (pinfunction "15_15") (pintype "passive"))
    )
    (net (code "437") (name "unconnected-(JP8-Pad16)") (class "Default")
      (node (ref "JP8") (pin "16") (pinfunction "16_16") (pintype "passive"))
    )
    (net (code "438") (name "unconnected-(JP8-Pad17)") (class "Default")
      (node (ref "JP8") (pin "17") (pinfunction "17_17") (pintype "passive"))
    )
    (net (code "439") (name "unconnected-(JP8-Pad26)") (class "Default")
      (node (ref "JP8") (pin "26") (pinfunction "26_26") (pintype "passive"))
    )
    (net (code "440") (name "unconnected-(JP9-Pad38)") (class "Default")
      (node (ref "JP9") (pin "38") (pinfunction "38_38") (pintype "passive"))
    )
    (net (code "441") (name "unconnected-(JP9-Pad39)") (class "Default")
      (node (ref "JP9") (pin "39") (pinfunction "39_39") (pintype "passive"))
    )
    (net (code "442") (name "unconnected-(JP9-Pad40)") (class "Default")
      (node (ref "JP9") (pin "40") (pinfunction "40_40") (pintype "passive"))
    )
    (net (code "443") (name "unconnected-(RN1-Pad10)") (class "Default")
      (node (ref "RN1") (pin "10") (pinfunction "10_10") (pintype "passive"))
    )
    (net (code "444") (name "unconnected-(RN2-Pad6)") (class "Default")
      (node (ref "RN2") (pin "6") (pinfunction "6_6") (pintype "passive"))
    )
    (net (code "445") (name "unconnected-(RN2-Pad10)") (class "Default")
      (node (ref "RN2") (pin "10") (pinfunction "10_10") (pintype "passive"))
    )
    (net (code "446") (name "unconnected-(RN8-Pad2)") (class "Default")
      (node (ref "RN8") (pin "2") (pinfunction "2_2") (pintype "passive"))
    )
    (net (code "447") (name "unconnected-(RN10-Pad10)") (class "Default")
      (node (ref "RN10") (pin "10") (pinfunction "10_10") (pintype "passive"))
    )
    (net (code "448") (name "unconnected-(VGA-Pad9)") (class "Default")
      (node (ref "VGA") (pin "9") (pinfunction "9_9") (pintype "passive"))
    )
    (net (code "449") (name "unconnected-(VGA-Pad12)") (class "Default")
      (node (ref "VGA") (pin "12") (pinfunction "12_12") (pintype "passive"))
    )
    (net (code "450") (name "unconnected-(VGA-Pad15)") (class "Default")
      (node (ref "VGA") (pin "15") (pinfunction "15_15") (pintype "passive"))
    )
    (net (code "451") (name "unconnected-(X1-S1-PadS@1)") (class "Default")
      (node (ref "X1") (pin "S@1") (pinfunction "S1_S@1") (pintype "passive"))
    )
    (net (code "452") (name "unconnected-(X1-S2-PadS@2)") (class "Default")
      (node (ref "X1") (pin "S@2") (pinfunction "S2_S@2") (pintype "passive"))
    )
    (net (code "453") (name "unconnected-(X3A-2-Pad1-2)") (class "Default")
      (node (ref "X3") (pin "1-2") (pinfunction "2_1-2") (pintype "passive"))
    )
    (net (code "454") (name "unconnected-(X3A-6-Pad1-6)") (class "Default")
      (node (ref "X3") (pin "1-6") (pinfunction "6_1-6") (pintype "passive"))
    )
    (net (code "455") (name "unconnected-(X3B-2-Pad2-2)") (class "Default")
      (node (ref "X3") (pin "2-2") (pinfunction "2_2-2") (pintype "passive"))
    )
    (net (code "456") (name "unconnected-(X3B-6-Pad2-6)") (class "Default")
      (node (ref "X3") (pin "2-6") (pinfunction "6_2-6") (pintype "passive"))
    )
    (net (code "457") (name "unconnected-(X4A-S-Pad1)") (class "Default")
      (node (ref "X4") (pin "1") (pinfunction "S_1") (pintype "passive"))
    )
    (net (code "458") (name "unconnected-(X4C-S-Pad11)") (class "Default")
      (node (ref "X4") (pin "11") (pinfunction "S_11") (pintype "passive"))
    )
    (net (code "459") (name "unconnected-(X4J-S-Pad18)") (class "Default")
      (node (ref "X4") (pin "18") (pinfunction "S_18") (pintype "passive"))
    )
    (net (code "460") (name "unconnected-(X4L-S-Pad2)") (class "Default")
      (node (ref "X4") (pin "2") (pinfunction "S_2") (pintype "passive"))
    )
    (net (code "461") (name "unconnected-(X4S-S-Pad8)") (class "Default")
      (node (ref "X4") (pin "8") (pinfunction "S_8") (pintype "passive"))
    )
    (net (code "462") (name "~{BGACK}") (class "Default")
      (node (ref "IC4") (pin "12") (pinfunction "BGACK_12") (pintype "input"))
      (node (ref "IC5") (pin "41") (pinfunction "~{BGACK}_41") (pintype "output"))
      (node (ref "RN5") (pin "3") (pinfunction "3_3") (pintype "passive"))
    )
    (net (code "463") (name "~{BG}") (class "Default")
      (node (ref "IC4") (pin "11") (pinfunction "BG_11") (pintype "output"))
      (node (ref "IC5") (pin "27") (pinfunction "~{BGI}_27") (pintype "input"))
      (node (ref "RN5") (pin "4") (pinfunction "4_4") (pintype "passive"))
    )
    (net (code "464") (name "~{BLANK}") (class "Default")
      (node (ref "D5") (pin "C") (pinfunction "C_C") (pintype "passive"))
      (node (ref "D6") (pin "C") (pinfunction "C_C") (pintype "passive"))
      (node (ref "D7") (pin "C") (pinfunction "C_C") (pintype "passive"))
      (node (ref "IC5") (pin "36") (pinfunction "~{BLANK}_36") (pintype "output"))
    )
    (net (code "465") (name "~{BR}") (class "Default")
      (node (ref "IC4") (pin "13") (pinfunction "BR_13") (pintype "input"))
      (node (ref "IC5") (pin "40") (pinfunction "~{BR}_40") (pintype "bidirectional"))
      (node (ref "RN5") (pin "2") (pinfunction "2_2") (pintype "passive"))
    )
    (net (code "466") (name "~{DIR}") (class "Default")
      (node (ref "IC19") (pin "6") (pinfunction "O_6") (pintype "open_collector"))
      (node (ref "JP5") (pin "18") (pinfunction "18_18") (pintype "passive"))
    )
    (net (code "467") (name "~{DRV0}") (class "Default")
      (node (ref "IC7") (pin "19") (pinfunction "IOA2_19") (pintype "output"))
      (node (ref "JP5") (pin "14") (pinfunction "14_14") (pintype "passive"))
    )
    (net (code "468") (name "~{DRV1}") (class "Default")
      (node (ref "IC7") (pin "20") (pinfunction "IOA1_20") (pintype "output"))
      (node (ref "JP5") (pin "12") (pinfunction "12_12") (pintype "passive"))
    )
    (net (code "469") (name "~{INDEX}") (class "Default")
      (node (ref "IC10") (pin "24") (pinfunction "/IP_24") (pintype "bidirectional"))
      (node (ref "JP5") (pin "8") (pinfunction "8_8") (pintype "passive"))
      (node (ref "R36") (pin "2") (pinfunction "2_2") (pintype "passive"))
    )
    (net (code "470") (name "~{MOTEB}") (class "Default")
      (node (ref "IC20") (pin "12") (pinfunction "O_12") (pintype "open_collector"))
      (node (ref "JP5") (pin "10") (pinfunction "10_10") (pintype "passive"))
      (node (ref "JP5") (pin "16") (pinfunction "16_16") (pintype "passive"))
    )
    (net (code "471") (name "~{RDATA}") (class "Default")
      (node (ref "IC10") (pin "19") (pinfunction "/RD_19") (pintype "bidirectional"))
      (node (ref "JP5") (pin "30") (pinfunction "30_30") (pintype "passive"))
      (node (ref "R37") (pin "2") (pinfunction "2_2") (pintype "passive"))
    )
    (net (code "472") (name "~{SIDE0}") (class "Default")
      (node (ref "IC19") (pin "12") (pinfunction "O_12") (pintype "open_collector"))
      (node (ref "JP5") (pin "32") (pinfunction "32_32") (pintype "passive"))
    )
    (net (code "473") (name "~{STEP}") (class "Default")
      (node (ref "JP5") (pin "20") (pinfunction "20_20") (pintype "passive"))
      (node (ref "R32") (pin "1") (pinfunction "1_1") (pintype "passive"))
    )
    (net (code "474") (name "~{TRACK0}") (class "Default")
      (node (ref "IC10") (pin "23") (pinfunction "TR00_23") (pintype "bidirectional"))
      (node (ref "JP5") (pin "26") (pinfunction "26_26") (pintype "passive"))
      (node (ref "R35") (pin "2") (pinfunction "2_2") (pintype "passive"))
    )
    (net (code "475") (name "~{WDATA}") (class "Default")
      (node (ref "JP5") (pin "22") (pinfunction "22_22") (pintype "passive"))
      (node (ref "R33") (pin "1") (pinfunction "1_1") (pintype "passive"))
    )
    (net (code "476") (name "~{WGATE}") (class "Default")
      (node (ref "IC19") (pin "8") (pinfunction "O_8") (pintype "open_collector"))
      (node (ref "JP5") (pin "24") (pinfunction "24_24") (pintype "passive"))
    )
    (net (code "477") (name "~{WP}") (class "Default")
      (node (ref "IC10") (pin "25") (pinfunction "/WP_25") (pintype "bidirectional"))
      (node (ref "JP5") (pin "28") (pinfunction "28_28") (pintype "passive"))
      (node (ref "R34") (pin "2") (pinfunction "2_2") (pintype "passive"))
    )
  )
)
